# BeagleBone_Blue.net
KiCad netlist of a schematic drawn in EAGLE
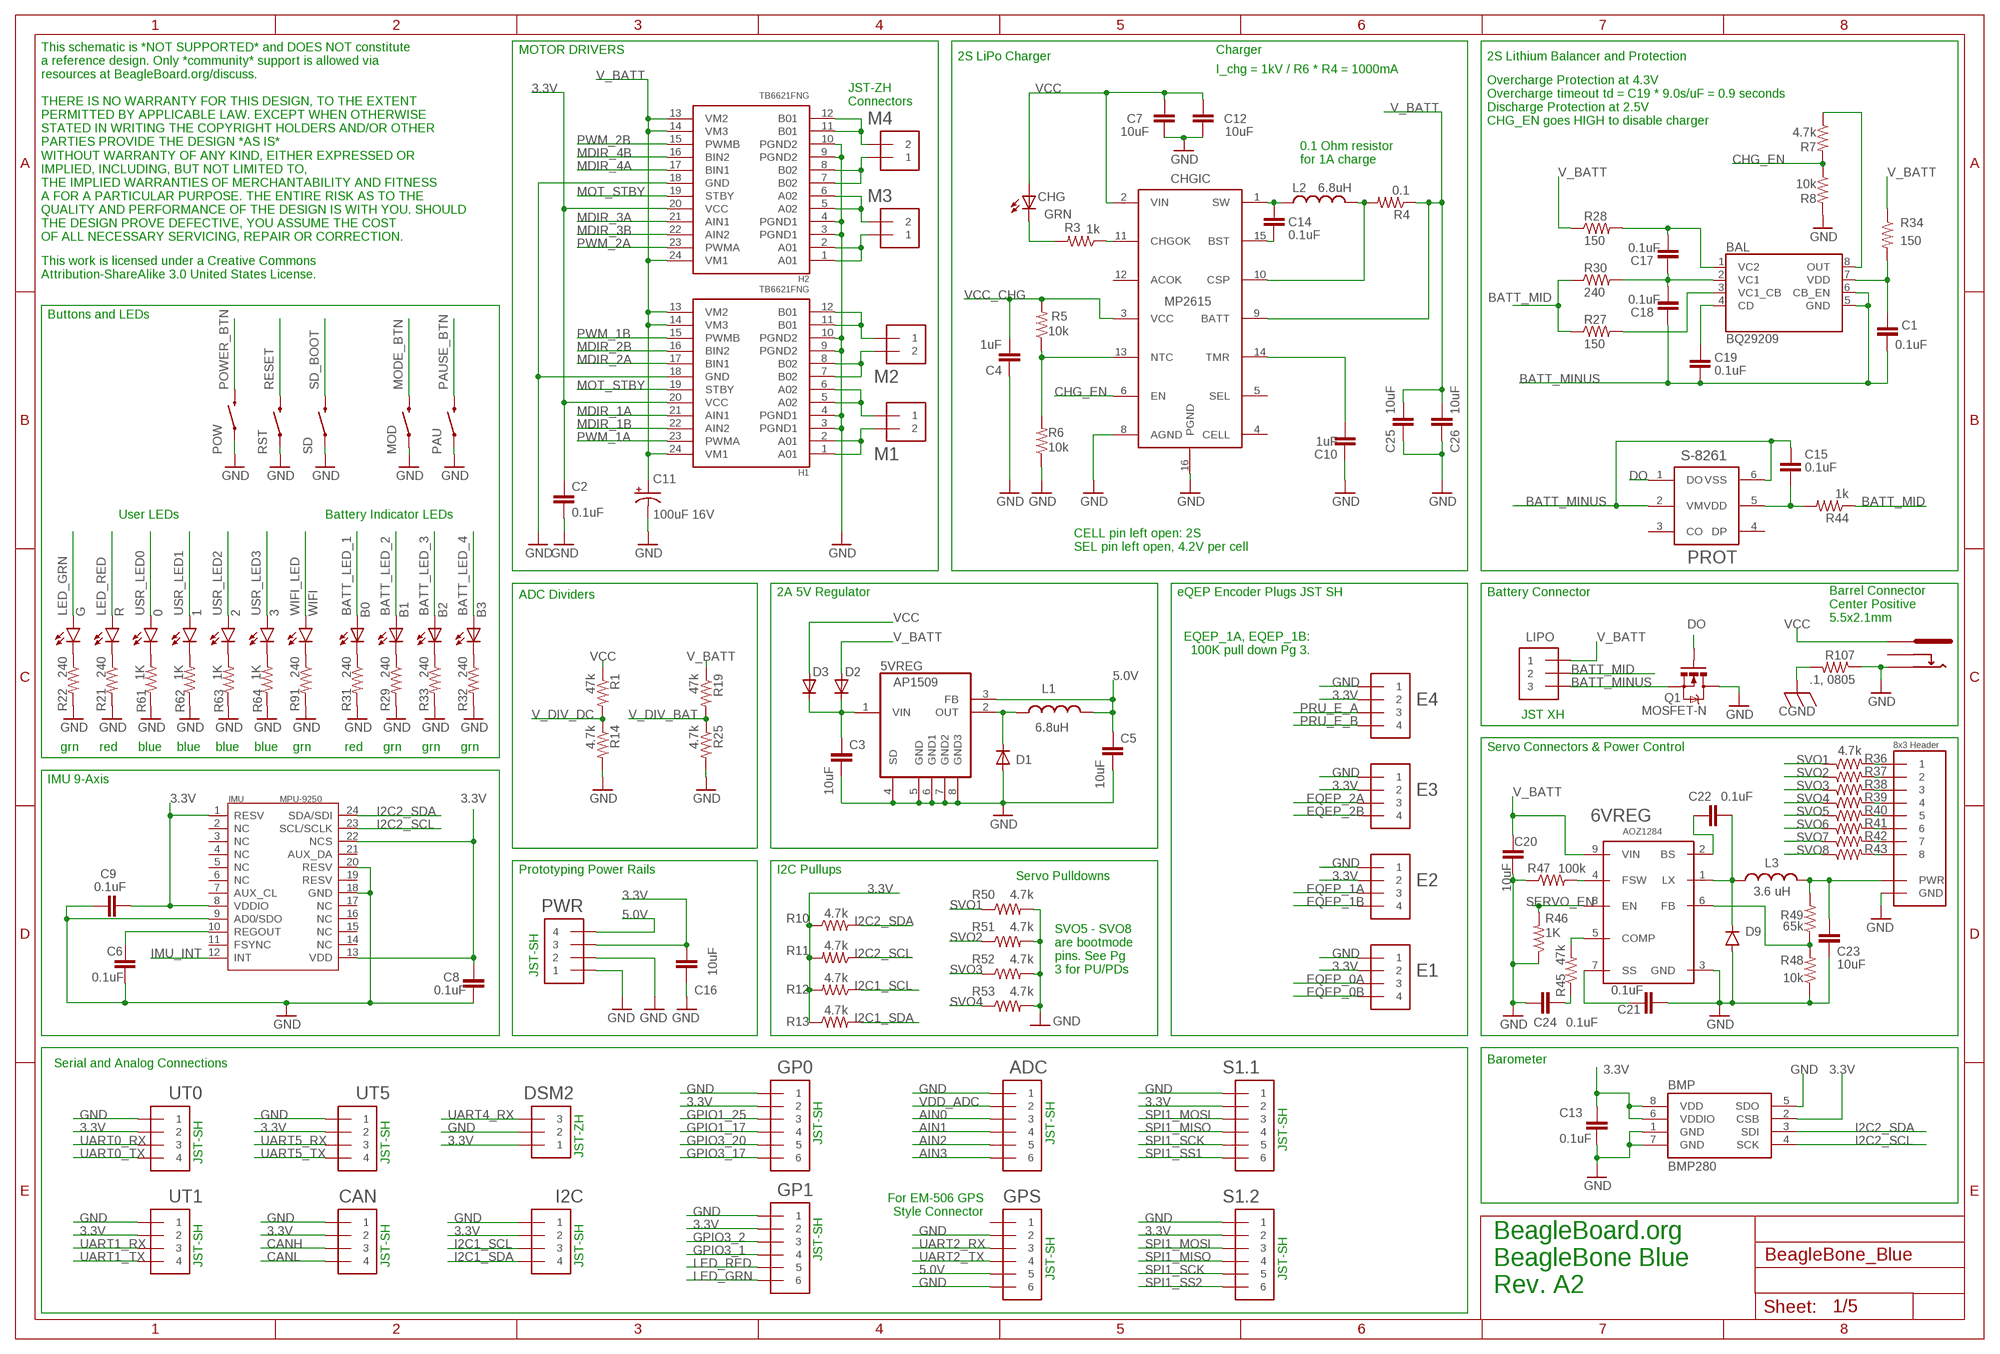
[diagram p0: schematic, sheet 1]
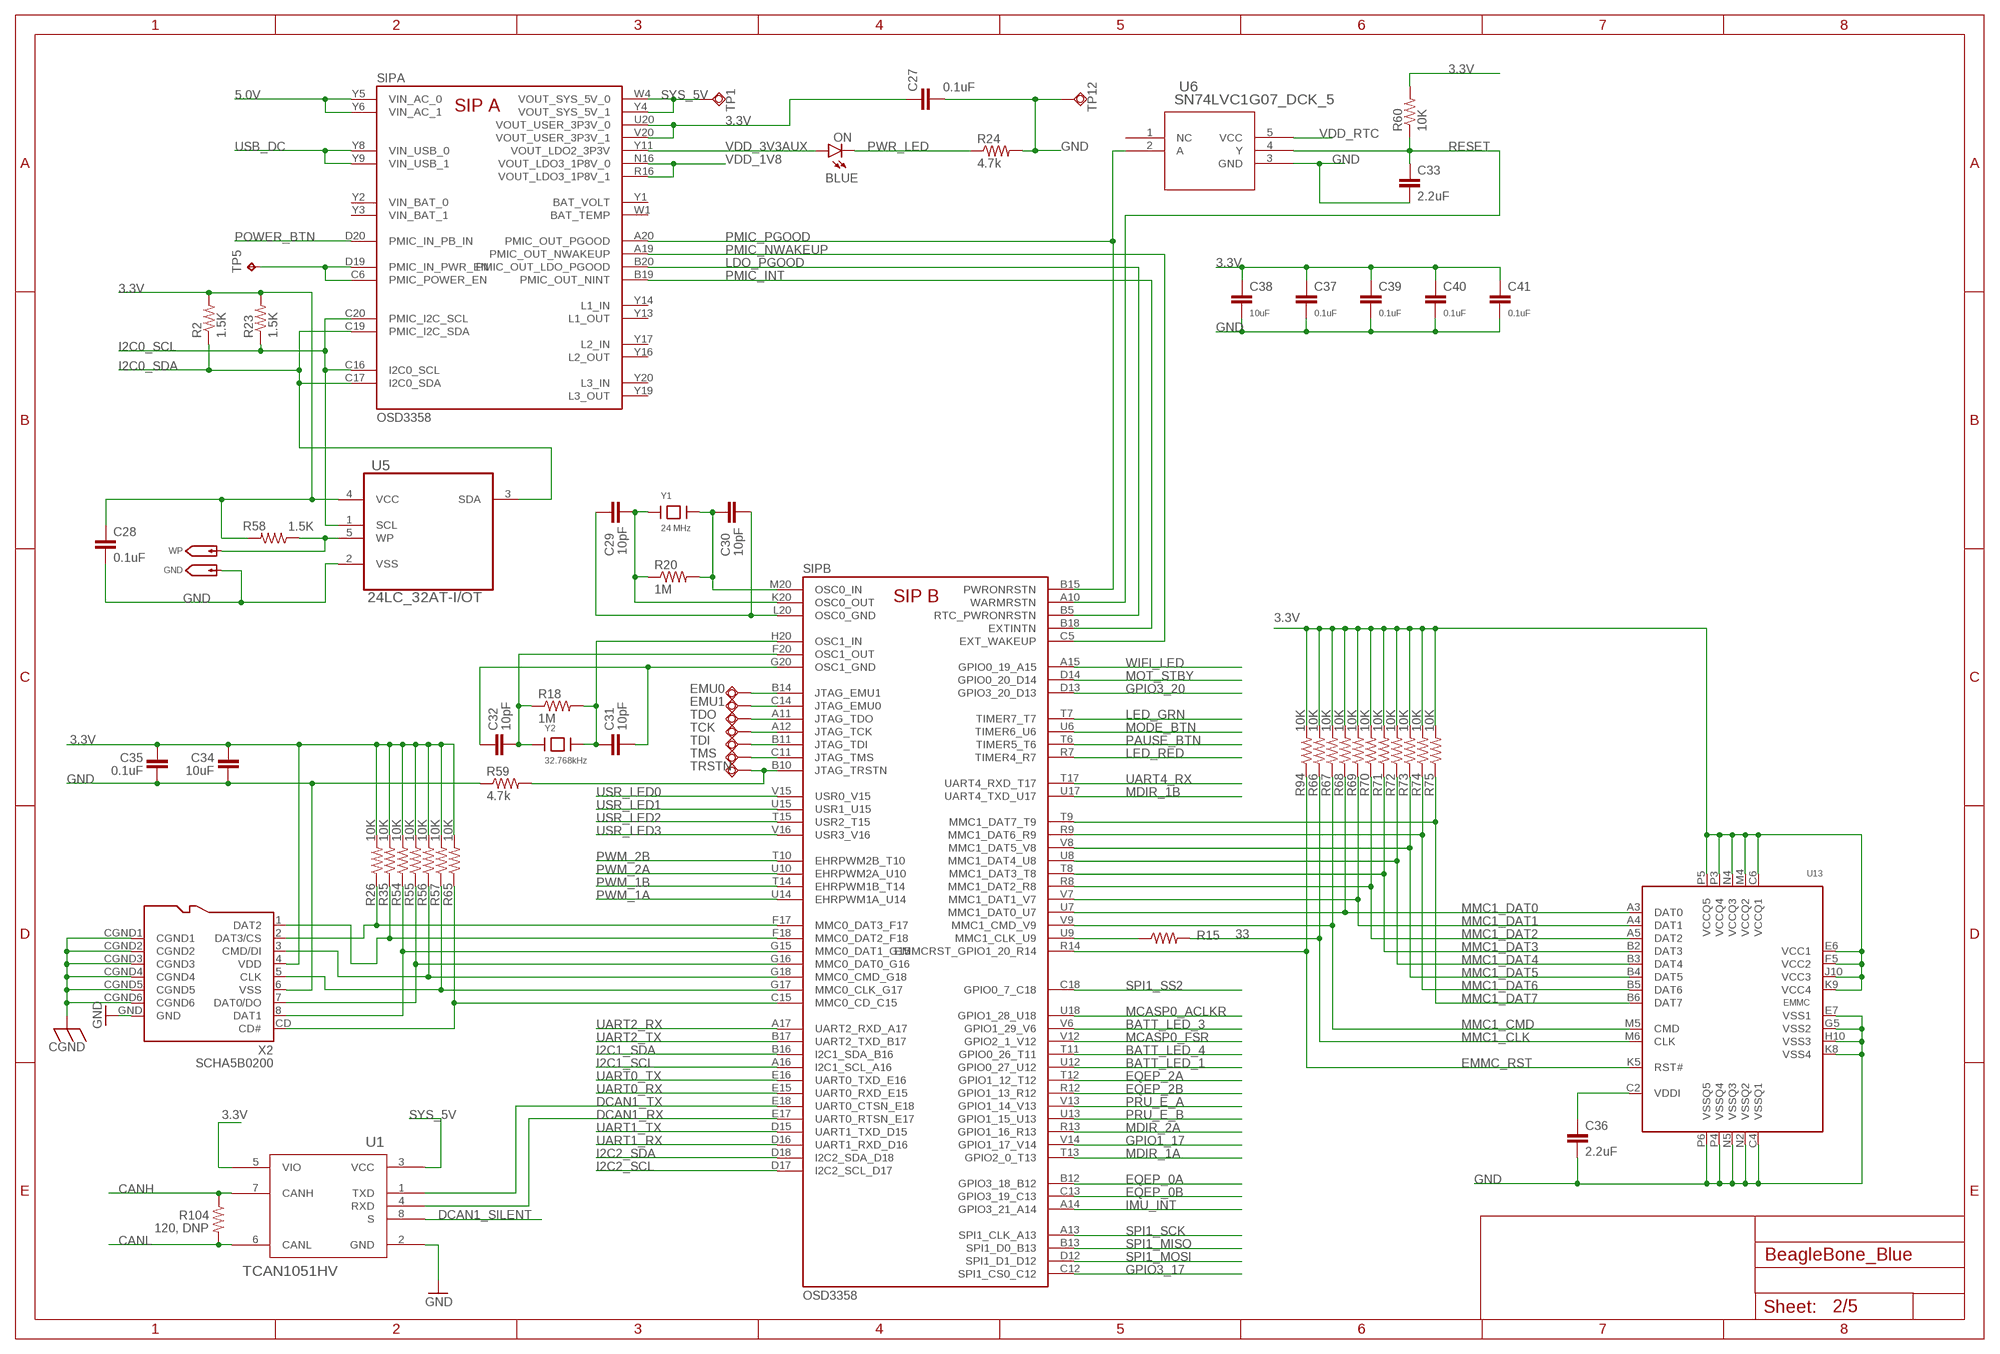
[diagram p1: schematic, sheet 2]
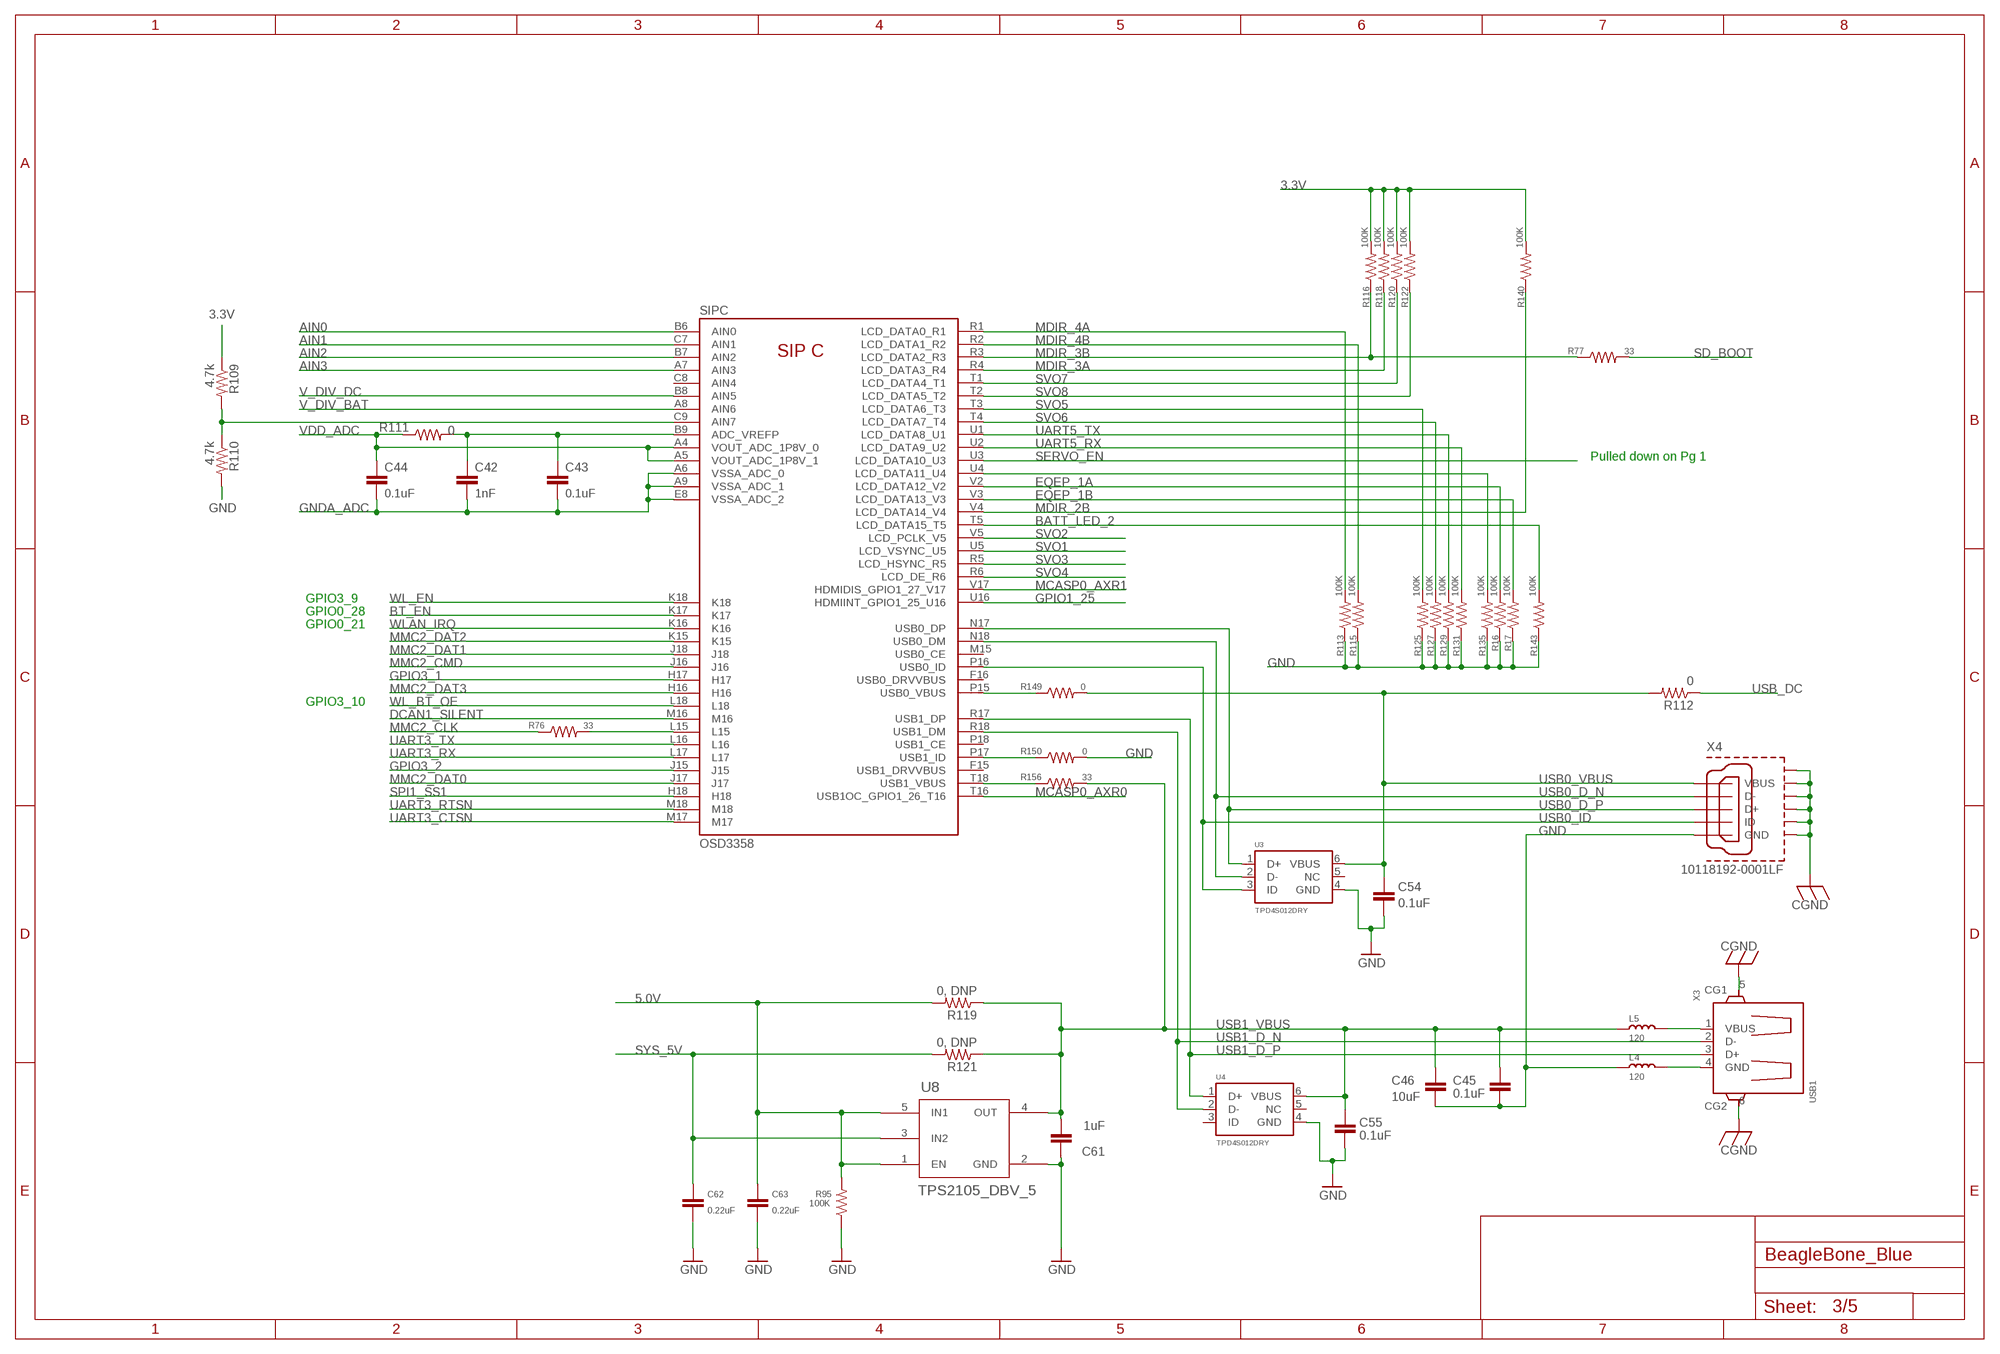
[diagram p2: schematic, sheet 3]
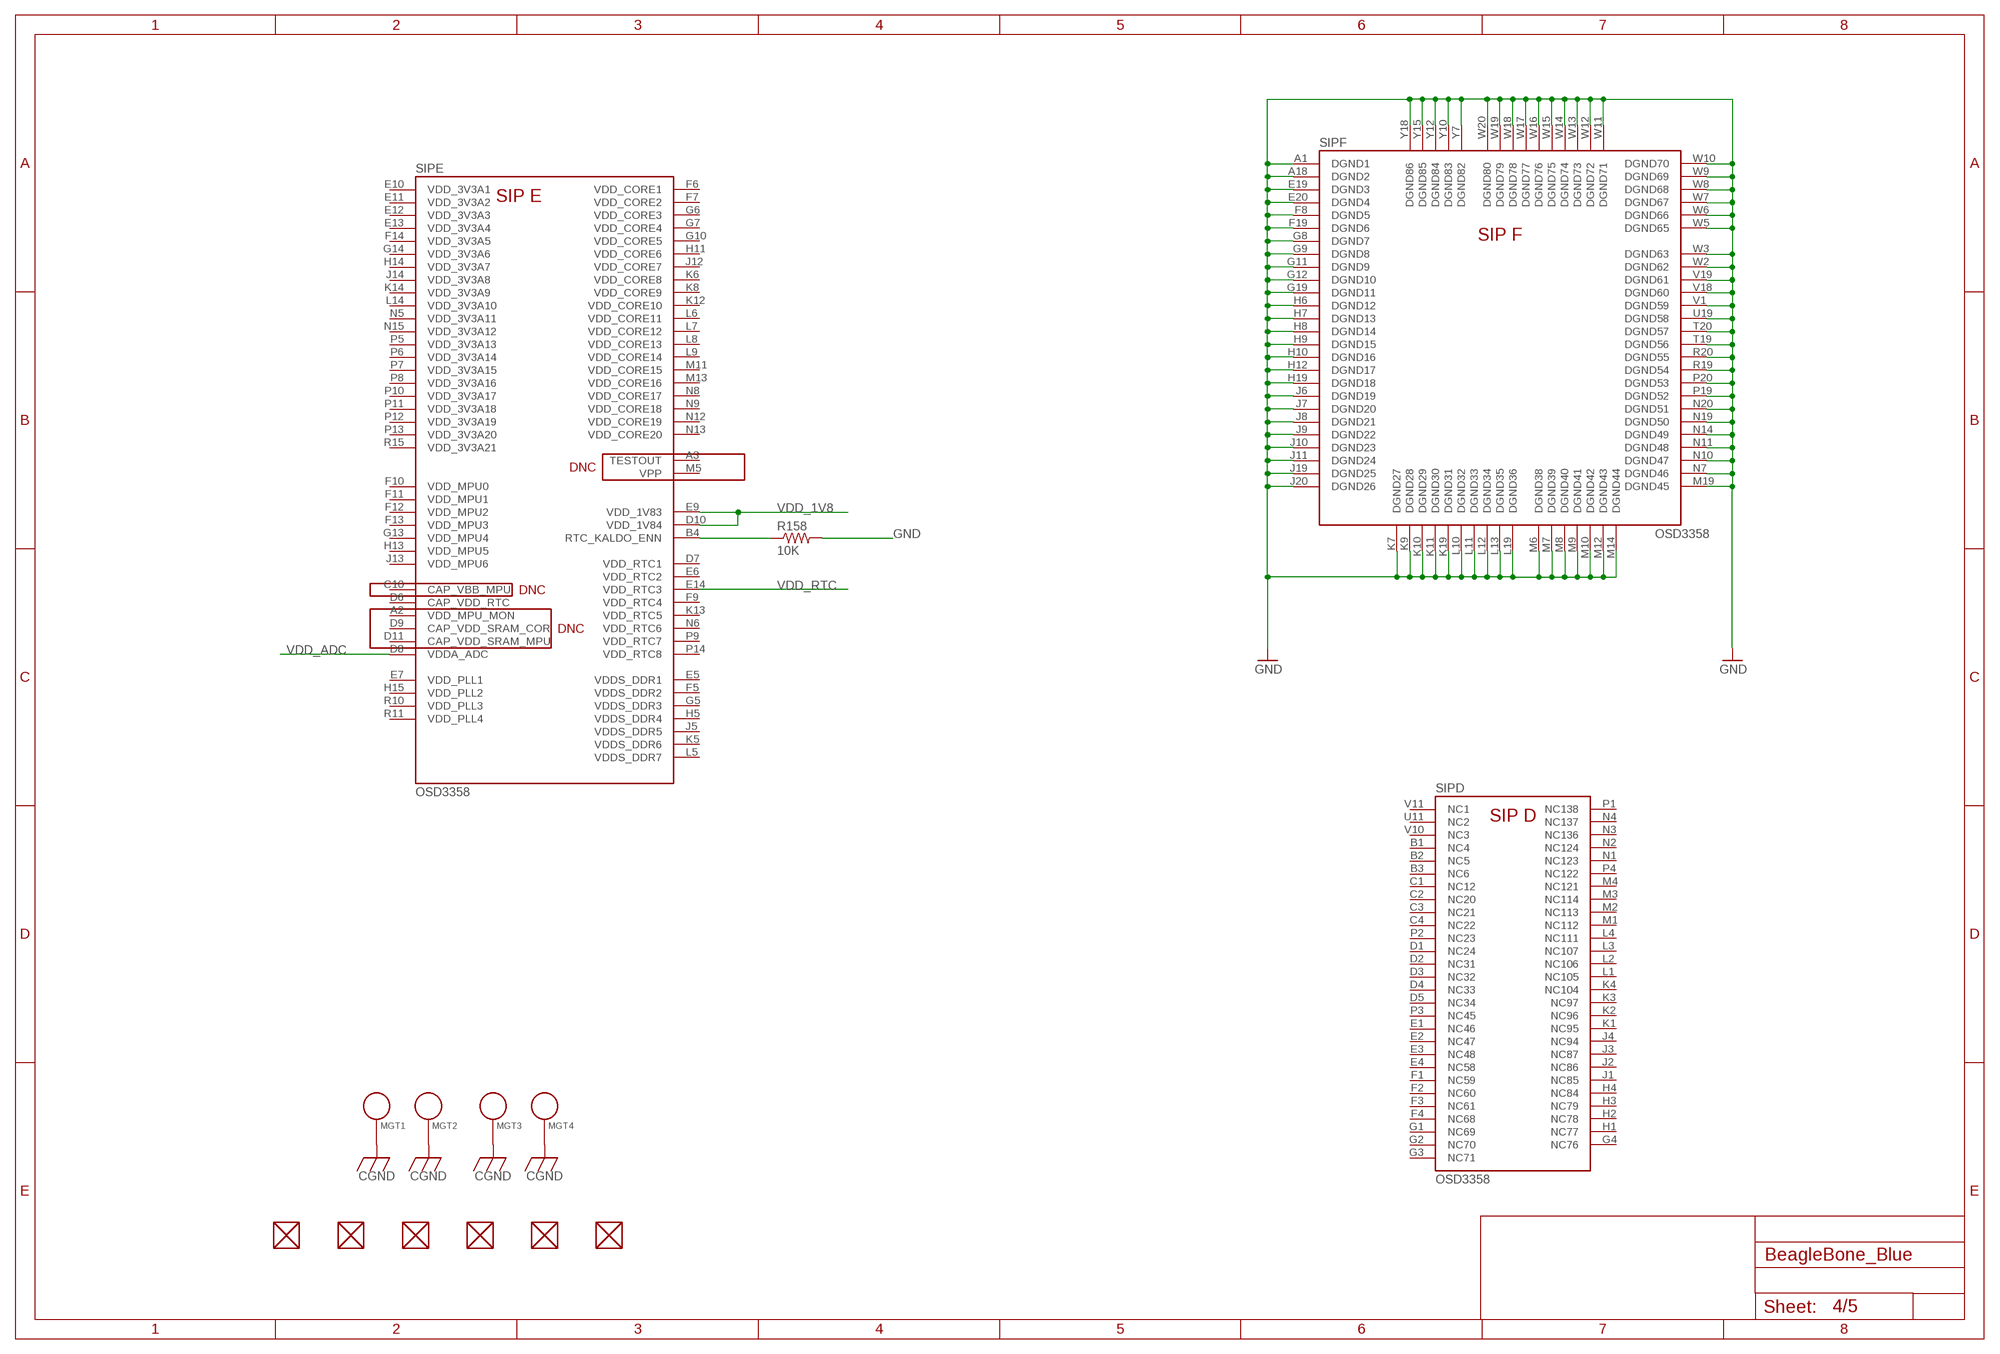
[diagram p3: schematic, sheet 4]
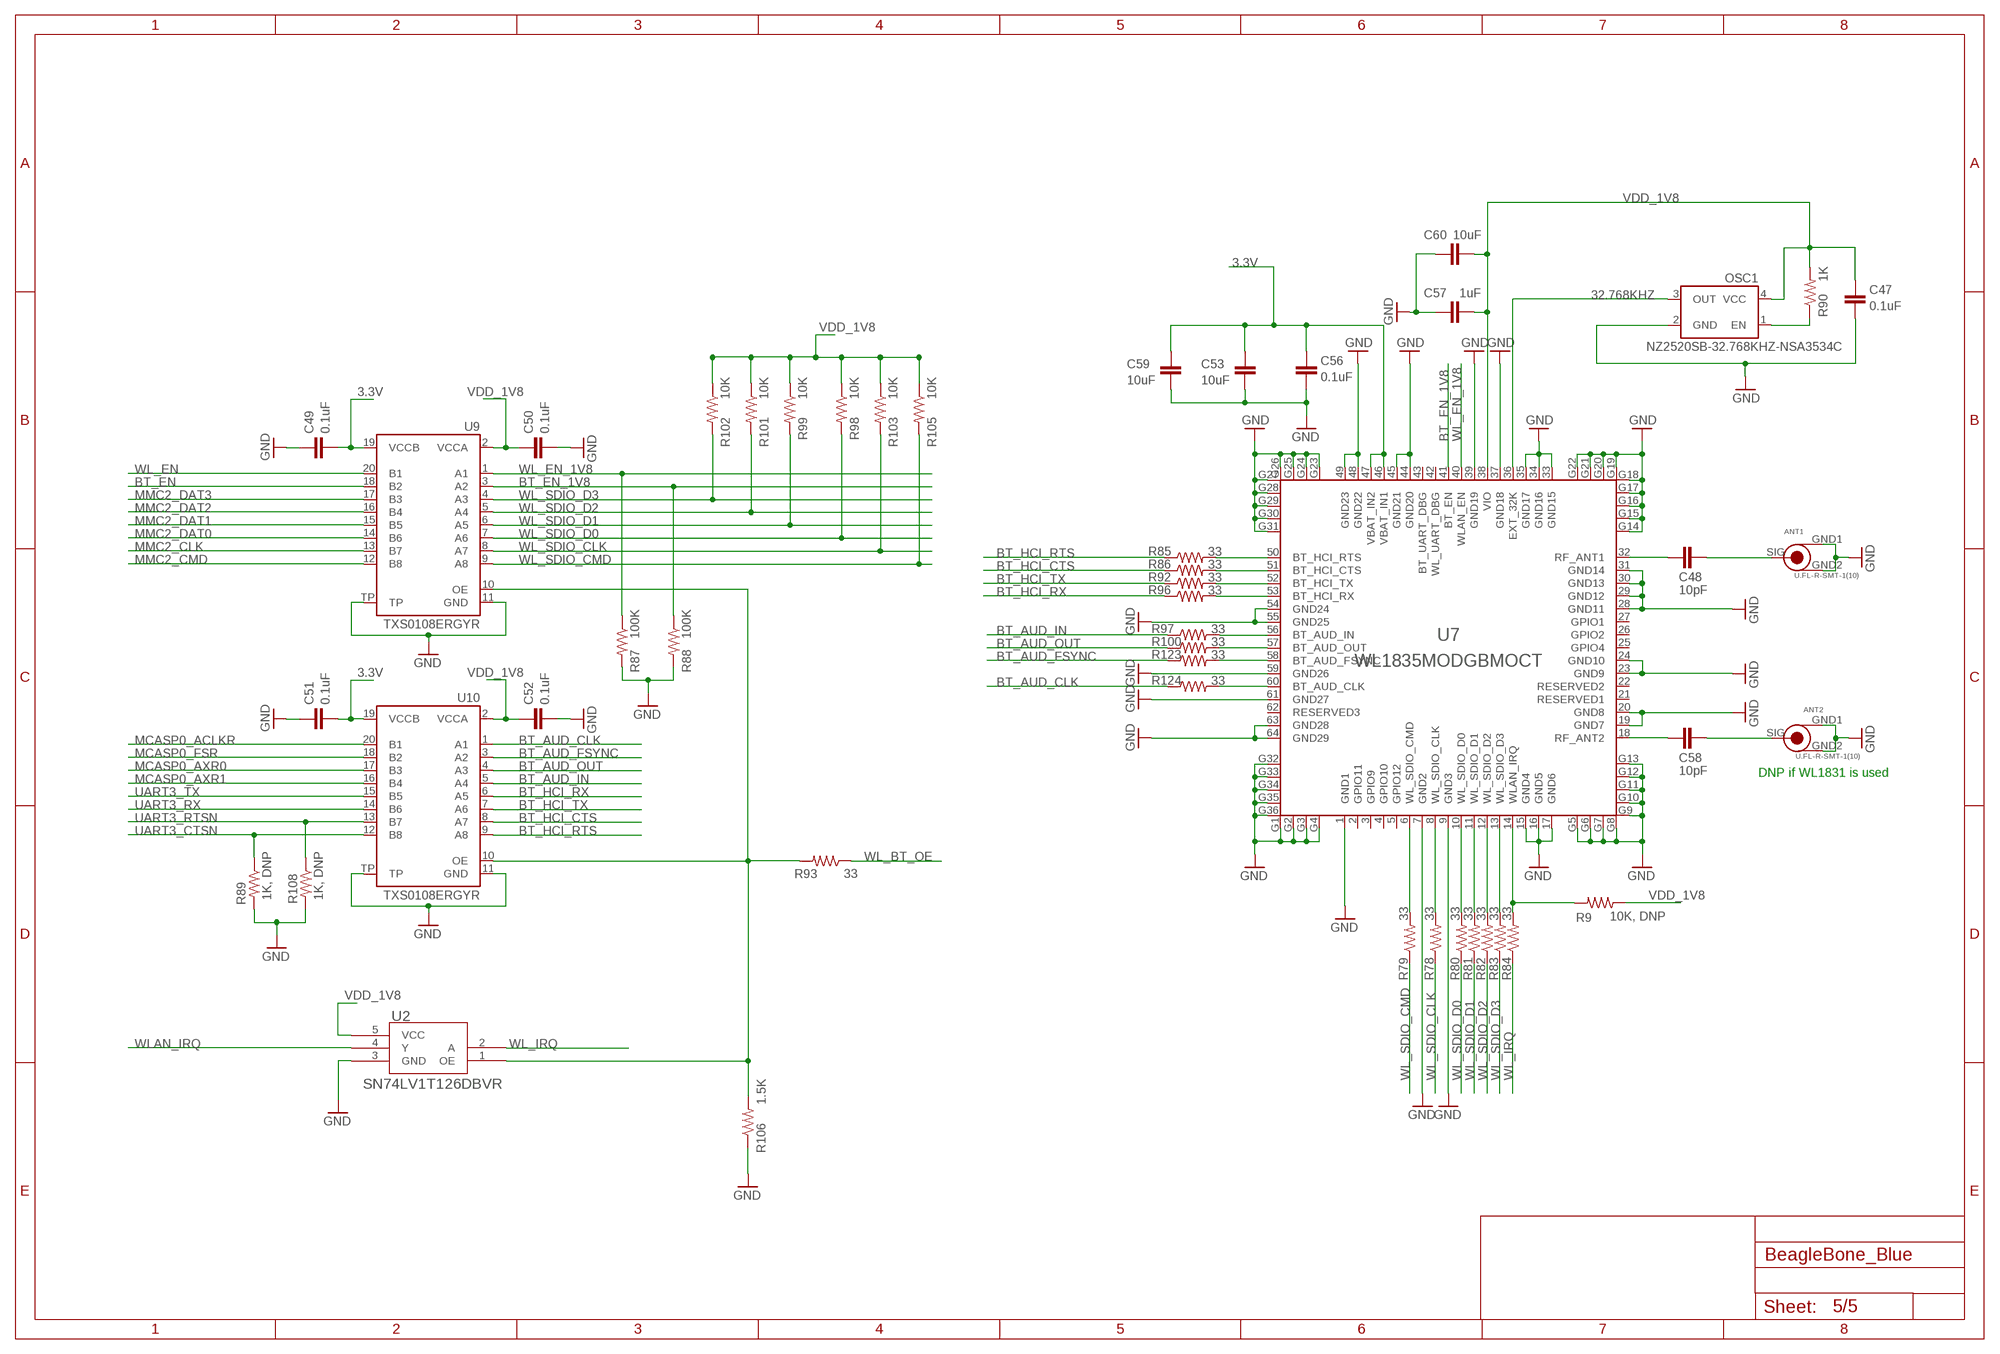
[diagram p4: schematic, sheet 5]

(export (version "E")
  (design (tool "Eeschema 10.0.6"))
  (components
    (comp (ref "0")
      (value "BLUE")
      (footprint "eagle-import:BEAGLEBONE_BLUE_LED-0603")
      (libsource (lib "eagle-import") (part "LED0603"))
    )
    (comp (ref "1")
      (value "BLUE")
      (footprint "eagle-import:BEAGLEBONE_BLUE_LED-0603")
      (libsource (lib "eagle-import") (part "LED0603"))
    )
    (comp (ref "2")
      (value "BLUE")
      (footprint "eagle-import:BEAGLEBONE_BLUE_LED-0603")
      (libsource (lib "eagle-import") (part "LED0603"))
    )
    (comp (ref "3")
      (value "BLUE")
      (footprint "eagle-import:BEAGLEBONE_BLUE_LED-0603")
      (libsource (lib "eagle-import") (part "LED0603"))
    )
    (comp (ref "5VREG")
      (value "AP1509SOIC-8-TIGHT")
      (footprint "eagle-import:BEAGLEBONE_BLUE_SO08-TIGHT")
      (libsource (lib "eagle-import") (part "AP1509SOIC-8-TIGHT"))
    )
    (comp (ref "6VREG")
      (value "AOZ1284")
      (footprint "eagle-import:SO08-EXPOSED")
      (libsource (lib "eagle-import") (part "AOZ1284"))
    )
    (comp (ref "12V")
      (value "PJ-102B_POWER_CON")
      (footprint "eagle-import:PJ-102B_POWER_CON")
      (libsource (lib "eagle-import") (part "PJ-102B_POWER_CON"))
    )
    (comp (ref "ADC")
      (value "JST_SH_6")
      (footprint "eagle-import:JST_SH_6")
      (libsource (lib "eagle-import") (part "JST_SH_6"))
    )
    (comp (ref "B0")
      (value "RED")
      (footprint "eagle-import:LED-0603")
      (libsource (lib "eagle-import") (part "SparkFun-LED_LED0603"))
    )
    (comp (ref "B1")
      (value "GREEN")
      (footprint "eagle-import:LED-0603")
      (libsource (lib "eagle-import") (part "SparkFun-LED_LED0603"))
    )
    (comp (ref "B2")
      (value "GREEN")
      (footprint "eagle-import:LED-0603")
      (libsource (lib "eagle-import") (part "SparkFun-LED_LED0603"))
    )
    (comp (ref "B3")
      (value "GREEN")
      (footprint "eagle-import:LED-0603")
      (libsource (lib "eagle-import") (part "SparkFun-LED_LED0603"))
    )
    (comp (ref "BAL")
      (value "BQ29209")
      (footprint "eagle-import:8-SON_3X3MM")
      (libsource (lib "eagle-import") (part "BQ29209"))
    )
    (comp (ref "BMP")
      (value "BMP280")
      (footprint "eagle-import:BMP280")
      (libsource (lib "eagle-import") (part "BMP280"))
    )
    (comp (ref "C1")
      (value "0.1uF")
      (footprint "eagle-import:0402-CAP")
      (libsource (lib "eagle-import") (part "Strawson_Eagle_Lib_CAP0402-CAP"))
    )
    (comp (ref "C2")
      (value "0.1uF")
      (footprint "eagle-import:0402-CAP")
      (libsource (lib "eagle-import") (part "Strawson_Eagle_Lib_CAP0402-CAP"))
    )
    (comp (ref "C3")
      (value "10uF")
      (footprint "eagle-import:0805")
      (libsource (lib "eagle-import") (part "CAP0805"))
    )
    (comp (ref "C4")
      (value "1uF")
      (footprint "eagle-import:0402-CAP")
      (libsource (lib "eagle-import") (part "Strawson_Eagle_Lib_CAP0402-CAP"))
    )
    (comp (ref "C5")
      (value "10uF")
      (footprint "eagle-import:0805")
      (libsource (lib "eagle-import") (part "CAP0805"))
    )
    (comp (ref "C6")
      (value "0.1uF")
      (footprint "eagle-import:0402-CAP")
      (libsource (lib "eagle-import") (part "Strawson_Eagle_Lib_CAP0402-CAP"))
    )
    (comp (ref "C7")
      (value "10uF")
      (footprint "eagle-import:0805")
      (libsource (lib "eagle-import") (part "CAP0805"))
    )
    (comp (ref "C8")
      (value "0.1uF")
      (footprint "eagle-import:0402-CAP")
      (libsource (lib "eagle-import") (part "Strawson_Eagle_Lib_CAP0402-CAP"))
    )
    (comp (ref "C9")
      (value "0.1uF")
      (footprint "eagle-import:0402-CAP")
      (libsource (lib "eagle-import") (part "Strawson_Eagle_Lib_CAP0402-CAP"))
    )
    (comp (ref "C10")
      (value "1uF")
      (footprint "eagle-import:0402-CAP")
      (libsource (lib "eagle-import") (part "Strawson_Eagle_Lib_CAP0402-CAP"))
    )
    (comp (ref "C11")
      (value "100uF 16V")
      (footprint "eagle-import:PANASONIC_D")
      (libsource (lib "eagle-import") (part "CPOL-USD"))
    )
    (comp (ref "C12")
      (value "10uF")
      (footprint "eagle-import:0805")
      (libsource (lib "eagle-import") (part "CAP0805"))
    )
    (comp (ref "C13")
      (value "0.1uF")
      (footprint "eagle-import:0402-CAP")
      (libsource (lib "eagle-import") (part "Strawson_Eagle_Lib_CAP0402-CAP"))
    )
    (comp (ref "C14")
      (value "0.1uF")
      (footprint "eagle-import:0402-CAP")
      (libsource (lib "eagle-import") (part "Strawson_Eagle_Lib_CAP0402-CAP"))
    )
    (comp (ref "C15")
      (value "0.1uF")
      (footprint "eagle-import:0402-CAP")
      (libsource (lib "eagle-import") (part "Strawson_Eagle_Lib_CAP0402-CAP"))
    )
    (comp (ref "C16")
      (value "10uF")
      (footprint "eagle-import:0805")
      (libsource (lib "eagle-import") (part "CAP0805"))
    )
    (comp (ref "C17")
      (value "0.1uF")
      (footprint "eagle-import:0402-CAP")
      (libsource (lib "eagle-import") (part "Strawson_Eagle_Lib_CAP0402-CAP"))
    )
    (comp (ref "C18")
      (value "0.1uF")
      (footprint "eagle-import:0402-CAP")
      (libsource (lib "eagle-import") (part "Strawson_Eagle_Lib_CAP0402-CAP"))
    )
    (comp (ref "C19")
      (value "0.1uF")
      (footprint "eagle-import:0402-CAP")
      (libsource (lib "eagle-import") (part "Strawson_Eagle_Lib_CAP0402-CAP"))
    )
    (comp (ref "C20")
      (value "10uF")
      (footprint "eagle-import:0805")
      (libsource (lib "eagle-import") (part "CAP0805"))
    )
    (comp (ref "C21")
      (value "0.1uF")
      (footprint "eagle-import:0402-CAP")
      (libsource (lib "eagle-import") (part "Strawson_Eagle_Lib_CAP0402-CAP"))
    )
    (comp (ref "C22")
      (value "0.1uF")
      (footprint "eagle-import:0402-CAP")
      (libsource (lib "eagle-import") (part "Strawson_Eagle_Lib_CAP0402-CAP"))
    )
    (comp (ref "C23")
      (value "10uF")
      (footprint "eagle-import:0805")
      (libsource (lib "eagle-import") (part "CAP0805"))
    )
    (comp (ref "C24")
      (value "0.1uF")
      (footprint "eagle-import:0402-CAP")
      (libsource (lib "eagle-import") (part "Strawson_Eagle_Lib_CAP0402-CAP"))
    )
    (comp (ref "C25")
      (value "10uF")
      (footprint "eagle-import:0805")
      (libsource (lib "eagle-import") (part "CAP0805"))
    )
    (comp (ref "C26")
      (value "10uF")
      (footprint "eagle-import:0805")
      (libsource (lib "eagle-import") (part "CAP0805"))
    )
    (comp (ref "CAN")
      (value "JST_SH_4")
      (footprint "eagle-import:JST_SH_4_SMD")
      (libsource (lib "eagle-import") (part "JST_SH_4"))
    )
    (comp (ref "CHG")
      (value "GRN")
      (footprint "eagle-import:LED-0603")
      (libsource (lib "eagle-import") (part "SparkFun-LED_LED0603"))
    )
    (comp (ref "CHGIC")
      (value "MP2615")
      (footprint "eagle-import:MP2615")
      (libsource (lib "eagle-import") (part "MP2615"))
    )
    (comp (ref "D1")
      (value "DIODE_SOD-123FL")
      (footprint "eagle-import:ADAFRUIT_SOD-123FL")
      (libsource (lib "eagle-import") (part "DIODE_SOD-123FL"))
    )
    (comp (ref "D2")
      (value "DIODE_SOD-123FL")
      (footprint "eagle-import:ADAFRUIT_SOD-123FL")
      (libsource (lib "eagle-import") (part "DIODE_SOD-123FL"))
    )
    (comp (ref "D3")
      (value "DIODE_SOD-123FL")
      (footprint "eagle-import:ADAFRUIT_SOD-123FL")
      (libsource (lib "eagle-import") (part "DIODE_SOD-123FL"))
    )
    (comp (ref "D9")
      (value "DIODEDO214AA")
      (footprint "eagle-import:DO-214AA")
      (libsource (lib "eagle-import") (part "DIODEDO214AA"))
    )
    (comp (ref "DSM2")
      (value "JST_ZH_3")
      (footprint "eagle-import:JST_ZH_3")
      (libsource (lib "eagle-import") (part "JST_ZH_3"))
    )
    (comp (ref "E1")
      (value "JST_SH_4")
      (footprint "eagle-import:JST_SH_4_SMD")
      (libsource (lib "eagle-import") (part "JST_SH_4"))
    )
    (comp (ref "E2")
      (value "JST_SH_4")
      (footprint "eagle-import:JST_SH_4_SMD")
      (libsource (lib "eagle-import") (part "JST_SH_4"))
    )
    (comp (ref "E3")
      (value "JST_SH_4")
      (footprint "eagle-import:JST_SH_4_SMD")
      (libsource (lib "eagle-import") (part "JST_SH_4"))
    )
    (comp (ref "E4")
      (value "JST_SH_4")
      (footprint "eagle-import:JST_SH_4_SMD")
      (libsource (lib "eagle-import") (part "JST_SH_4"))
    )
    (comp (ref "G")
      (value "GREEN")
      (footprint "eagle-import:BEAGLEBONE_BLUE_LED-0603")
      (libsource (lib "eagle-import") (part "LED0603"))
    )
    (comp (ref "GP0")
      (value "JST_SH_6")
      (footprint "eagle-import:JST_SH_6")
      (libsource (lib "eagle-import") (part "JST_SH_6"))
    )
    (comp (ref "GP1")
      (value "JST_SH_6")
      (footprint "eagle-import:JST_SH_6")
      (libsource (lib "eagle-import") (part "JST_SH_6"))
    )
    (comp (ref "GPS")
      (value "JST_SH_6")
      (footprint "eagle-import:JST_SH_6")
      (libsource (lib "eagle-import") (part "JST_SH_6"))
    )
    (comp (ref "H1")
      (value "TB6621FNG")
      (footprint "eagle-import:SSOP24")
      (libsource (lib "eagle-import") (part "TB6621FNG"))
    )
    (comp (ref "H2")
      (value "TB6621FNG")
      (footprint "eagle-import:SSOP24")
      (libsource (lib "eagle-import") (part "TB6621FNG"))
    )
    (comp (ref "I2C")
      (value "JST_SH_4")
      (footprint "eagle-import:JST_SH_4_SMD")
      (libsource (lib "eagle-import") (part "JST_SH_4"))
    )
    (comp (ref "IMU")
      (value "MPU-9250")
      (footprint "eagle-import:QFN24G-0.4-3X3MM")
      (libsource (lib "eagle-import") (part "MPU-9250"))
    )
    (comp (ref "J2")
      (value "STRAWSON_EAGLE_LIB_SERVO_HEADERS_8X")
      (footprint "eagle-import:STRAWSON_EAGLE_LIB_3X8_0.1__HEADER")
      (libsource (lib "eagle-import") (part "STRAWSON_EAGLE_LIB_SERVO_HEADERS_8X"))
    )
    (comp (ref "L1")
      (value "6.8uH")
      (footprint "eagle-import:SRN6045")
      (libsource (lib "eagle-import") (part "INDUCTORBOURNS_SRN6045"))
    )
    (comp (ref "L2")
      (value "6.8uH")
      (footprint "eagle-import:SRN6045")
      (libsource (lib "eagle-import") (part "INDUCTORBOURNS_SRN6045"))
    )
    (comp (ref "L3")
      (value "3.6 uH")
      (footprint "eagle-import:8X8MM_INDUCTOR")
      (libsource (lib "eagle-import") (part "INDUCTOR"))
    )
    (comp (ref "LIPO")
      (value "BATTERY")
      (footprint "eagle-import:JST_XH_3-PIN")
      (libsource (lib "eagle-import") (part "JST_XH_3-PIN"))
    )
    (comp (ref "M1")
      (value "JST_ZH_2")
      (footprint "eagle-import:JST_ZH_2")
      (libsource (lib "eagle-import") (part "JST_ZH_2"))
    )
    (comp (ref "M2")
      (value "JST_ZH_2")
      (footprint "eagle-import:JST_ZH_2")
      (libsource (lib "eagle-import") (part "JST_ZH_2"))
    )
    (comp (ref "M3")
      (value "JST_ZH_2")
      (footprint "eagle-import:JST_ZH_2")
      (libsource (lib "eagle-import") (part "JST_ZH_2"))
    )
    (comp (ref "M4")
      (value "JST_ZH_2")
      (footprint "eagle-import:JST_ZH_2")
      (libsource (lib "eagle-import") (part "JST_ZH_2"))
    )
    (comp (ref "MOD")
      (value "SWITCH-MOMENTARY-2SMD-1101NE")
      (footprint "eagle-import:TACTILE-SWITCH-1101NE")
      (libsource (lib "eagle-import") (part "SWITCH-MOMENTARY-2SMD-1101NE"))
    )
    (comp (ref "PAU")
      (value "SWITCH-MOMENTARY-2SMD-1101NE")
      (footprint "eagle-import:TACTILE-SWITCH-1101NE")
      (libsource (lib "eagle-import") (part "SWITCH-MOMENTARY-2SMD-1101NE"))
    )
    (comp (ref "POW")
      (value "SWITCH-MOMENTARY-2SMD-1101NE")
      (footprint "eagle-import:TACTILE-SWITCH-1101NE")
      (libsource (lib "eagle-import") (part "SWITCH-MOMENTARY-2SMD-1101NE"))
    )
    (comp (ref "PROT")
      (value "S-8261")
      (footprint "eagle-import:SOT-236")
      (libsource (lib "eagle-import") (part "S-8261"))
    )
    (comp (ref "PWR")
      (value "JST_SH_4")
      (footprint "eagle-import:JST_SH_4_SMD")
      (libsource (lib "eagle-import") (part "JST_SH_4"))
    )
    (comp (ref "Q1")
      (value "MOSFET-N")
      (footprint "eagle-import:SO08-TIGHT")
      (libsource (lib "eagle-import") (part "MOSFET-NCHANNEL"))
    )
    (comp (ref "R")
      (value "RED")
      (footprint "eagle-import:BEAGLEBONE_BLUE_LED-0603")
      (libsource (lib "eagle-import") (part "LED0603"))
    )
    (comp (ref "R1")
      (value "47k")
      (footprint "eagle-import:0402-RES")
      (libsource (lib "eagle-import") (part "RESISTOR0402-RES"))
    )
    (comp (ref "R3")
      (value "1k")
      (footprint "eagle-import:0402-RES")
      (libsource (lib "eagle-import") (part "RESISTOR0402-RES"))
    )
    (comp (ref "R4")
      (value "0.1")
      (footprint "eagle-import:0603-RES")
      (libsource (lib "eagle-import") (part "RESISTOR0603"))
    )
    (comp (ref "R5")
      (value "10k")
      (footprint "eagle-import:0402-RES")
      (libsource (lib "eagle-import") (part "RESISTOR0402-RES"))
    )
    (comp (ref "R6")
      (value "10k")
      (footprint "eagle-import:0402-RES")
      (libsource (lib "eagle-import") (part "RESISTOR0402-RES"))
    )
    (comp (ref "R7")
      (value "4.7k")
      (footprint "eagle-import:0402-RES")
      (libsource (lib "eagle-import") (part "RESISTOR0402-RES"))
    )
    (comp (ref "R8")
      (value "10k")
      (footprint "eagle-import:0402-RES")
      (libsource (lib "eagle-import") (part "RESISTOR0402-RES"))
    )
    (comp (ref "R10")
      (value "4.7k")
      (footprint "eagle-import:0402-RES")
      (libsource (lib "eagle-import") (part "RESISTOR0402-RES"))
    )
    (comp (ref "R11")
      (value "4.7k")
      (footprint "eagle-import:0402-RES")
      (libsource (lib "eagle-import") (part "RESISTOR0402-RES"))
    )
    (comp (ref "R12")
      (value "4.7k")
      (footprint "eagle-import:0402-RES")
      (libsource (lib "eagle-import") (part "RESISTOR0402-RES"))
    )
    (comp (ref "R13")
      (value "4.7k")
      (footprint "eagle-import:0402-RES")
      (libsource (lib "eagle-import") (part "RESISTOR0402-RES"))
    )
    (comp (ref "R14")
      (value "4.7k")
      (footprint "eagle-import:0402-RES")
      (libsource (lib "eagle-import") (part "RESISTOR0402-RES"))
    )
    (comp (ref "R19")
      (value "47k")
      (footprint "eagle-import:0402-RES")
      (libsource (lib "eagle-import") (part "RESISTOR0402-RES"))
    )
    (comp (ref "R21")
      (value "240")
      (footprint "eagle-import:0402-RES")
      (libsource (lib "eagle-import") (part "RESISTOR0402-RES"))
    )
    (comp (ref "R22")
      (value "240")
      (footprint "eagle-import:0402-RES")
      (libsource (lib "eagle-import") (part "RESISTOR0402-RES"))
    )
    (comp (ref "R25")
      (value "4.7k")
      (footprint "eagle-import:0402-RES")
      (libsource (lib "eagle-import") (part "RESISTOR0402-RES"))
    )
    (comp (ref "R27")
      (value "150")
      (footprint "eagle-import:0402-RES")
      (libsource (lib "eagle-import") (part "RESISTOR0402-RES"))
    )
    (comp (ref "R28")
      (value "150")
      (footprint "eagle-import:0402-RES")
      (libsource (lib "eagle-import") (part "RESISTOR0402-RES"))
    )
    (comp (ref "R29")
      (value "240")
      (footprint "eagle-import:0402-RES")
      (libsource (lib "eagle-import") (part "RESISTOR0402-RES"))
    )
    (comp (ref "R30")
      (value "240")
      (footprint "eagle-import:0402-RES")
      (libsource (lib "eagle-import") (part "RESISTOR0402-RES"))
    )
    (comp (ref "R31")
      (value "240")
      (footprint "eagle-import:0402-RES")
      (libsource (lib "eagle-import") (part "RESISTOR0402-RES"))
    )
    (comp (ref "R32")
      (value "240")
      (footprint "eagle-import:0402-RES")
      (libsource (lib "eagle-import") (part "RESISTOR0402-RES"))
    )
    (comp (ref "R33")
      (value "240")
      (footprint "eagle-import:0402-RES")
      (libsource (lib "eagle-import") (part "RESISTOR0402-RES"))
    )
    (comp (ref "R34")
      (value "150")
      (footprint "eagle-import:0402-RES")
      (libsource (lib "eagle-import") (part "RESISTOR0402-RES"))
    )
    (comp (ref "R36")
      (value "4.7k")
      (footprint "eagle-import:0402-RES")
      (libsource (lib "eagle-import") (part "RESISTOR0402-RES"))
    )
    (comp (ref "R37")
      (value "4.7k")
      (footprint "eagle-import:0402-RES")
      (libsource (lib "eagle-import") (part "RESISTOR0402-RES"))
    )
    (comp (ref "R38")
      (value "4.7k")
      (footprint "eagle-import:0402-RES")
      (libsource (lib "eagle-import") (part "RESISTOR0402-RES"))
    )
    (comp (ref "R39")
      (value "4.7k")
      (footprint "eagle-import:0402-RES")
      (libsource (lib "eagle-import") (part "RESISTOR0402-RES"))
    )
    (comp (ref "R40")
      (value "4.7k")
      (footprint "eagle-import:0402-RES")
      (libsource (lib "eagle-import") (part "RESISTOR0402-RES"))
    )
    (comp (ref "R41")
      (value "4.7k")
      (footprint "eagle-import:0402-RES")
      (libsource (lib "eagle-import") (part "RESISTOR0402-RES"))
    )
    (comp (ref "R42")
      (value "4.7k")
      (footprint "eagle-import:0402-RES")
      (libsource (lib "eagle-import") (part "RESISTOR0402-RES"))
    )
    (comp (ref "R43")
      (value "4.7k")
      (footprint "eagle-import:0402-RES")
      (libsource (lib "eagle-import") (part "RESISTOR0402-RES"))
    )
    (comp (ref "R44")
      (value "1k")
      (footprint "eagle-import:0402-RES")
      (libsource (lib "eagle-import") (part "RESISTOR0402-RES"))
    )
    (comp (ref "R45")
      (value "47k")
      (footprint "eagle-import:0402-RES")
      (libsource (lib "eagle-import") (part "RESISTOR0402-RES"))
    )
    (comp (ref "R46")
      (value "1K")
      (footprint "eagle-import:0402-RES")
      (libsource (lib "eagle-import") (part "RESISTOR0402-RES"))
    )
    (comp (ref "R47")
      (value "100k")
      (footprint "eagle-import:0402-RES")
      (libsource (lib "eagle-import") (part "RESISTOR0402-RES"))
    )
    (comp (ref "R48")
      (value "10k")
      (footprint "eagle-import:0402-RES")
      (libsource (lib "eagle-import") (part "RESISTOR0402-RES"))
    )
    (comp (ref "R49")
      (value "65k")
      (footprint "eagle-import:0402-RES")
      (libsource (lib "eagle-import") (part "RESISTOR0402-RES"))
    )
    (comp (ref "R50")
      (value "4.7k")
      (footprint "eagle-import:0402-RES")
      (libsource (lib "eagle-import") (part "RESISTOR0402-RES"))
    )
    (comp (ref "R51")
      (value "4.7k")
      (footprint "eagle-import:0402-RES")
      (libsource (lib "eagle-import") (part "RESISTOR0402-RES"))
    )
    (comp (ref "R52")
      (value "4.7k")
      (footprint "eagle-import:0402-RES")
      (libsource (lib "eagle-import") (part "RESISTOR0402-RES"))
    )
    (comp (ref "R53")
      (value "4.7k")
      (footprint "eagle-import:0402-RES")
      (libsource (lib "eagle-import") (part "RESISTOR0402-RES"))
    )
    (comp (ref "R61")
      (value "1K")
      (footprint "eagle-import:0402-RES")
      (libsource (lib "eagle-import") (part "RESISTOR0402-RES"))
    )
    (comp (ref "R62")
      (value "1K")
      (footprint "eagle-import:0402-RES")
      (libsource (lib "eagle-import") (part "RESISTOR0402-RES"))
    )
    (comp (ref "R63")
      (value "1K")
      (footprint "eagle-import:0402-RES")
      (libsource (lib "eagle-import") (part "RESISTOR0402-RES"))
    )
    (comp (ref "R64")
      (value "1K")
      (footprint "eagle-import:0402-RES")
      (libsource (lib "eagle-import") (part "RESISTOR0402-RES"))
    )
    (comp (ref "R91")
      (value "240")
      (footprint "eagle-import:0402-RES")
      (libsource (lib "eagle-import") (part "RESISTOR0402-RES"))
    )
    (comp (ref "R107")
      (value ".1, 0805")
      (footprint "eagle-import:R0805")
      (libsource (lib "eagle-import") (part "R-US_R0805"))
    )
    (comp (ref "RST")
      (value "SWITCH-MOMENTARY-2SMD-1101NE")
      (footprint "eagle-import:TACTILE-SWITCH-1101NE")
      (libsource (lib "eagle-import") (part "SWITCH-MOMENTARY-2SMD-1101NE"))
    )
    (comp (ref "S1.1")
      (value "JST_SH_6")
      (footprint "eagle-import:JST_SH_6")
      (libsource (lib "eagle-import") (part "JST_SH_6"))
    )
    (comp (ref "S1.2")
      (value "JST_SH_6")
      (footprint "eagle-import:JST_SH_6")
      (libsource (lib "eagle-import") (part "JST_SH_6"))
    )
    (comp (ref "SD")
      (value "SWITCH-MOMENTARY-2SMD-1101NE")
      (footprint "eagle-import:TACTILE-SWITCH-1101NE")
      (libsource (lib "eagle-import") (part "SWITCH-MOMENTARY-2SMD-1101NE"))
    )
    (comp (ref "UT0")
      (value "JST_SH_4")
      (footprint "eagle-import:JST_SH_4_SMD")
      (libsource (lib "eagle-import") (part "JST_SH_4"))
    )
    (comp (ref "UT1")
      (value "JST_SH_4")
      (footprint "eagle-import:JST_SH_4_SMD")
      (libsource (lib "eagle-import") (part "JST_SH_4"))
    )
    (comp (ref "UT5")
      (value "JST_SH_4")
      (footprint "eagle-import:JST_SH_4_SMD")
      (libsource (lib "eagle-import") (part "JST_SH_4"))
    )
    (comp (ref "WIFI")
      (value "GREEN")
      (footprint "eagle-import:BEAGLEBONE_BLUE_LED-0603")
      (libsource (lib "eagle-import") (part "LED0603"))
    )
    (comp (ref "C27")
      (value "0.1uF")
      (footprint "eagle-import:0402-CAP")
      (libsource (lib "eagle-import") (part "Strawson_Eagle_Lib_CAP0402-CAP"))
    )
    (comp (ref "C28")
      (value "0.1uF")
      (footprint "eagle-import:0402-CAP")
      (libsource (lib "eagle-import") (part "Strawson_Eagle_Lib_CAP0402-CAP"))
    )
    (comp (ref "C29")
      (value "10pF")
      (footprint "eagle-import:0402-CAP")
      (libsource (lib "eagle-import") (part "Strawson_Eagle_Lib_CAP0402-CAP"))
    )
    (comp (ref "C30")
      (value "10pF")
      (footprint "eagle-import:0402-CAP")
      (libsource (lib "eagle-import") (part "Strawson_Eagle_Lib_CAP0402-CAP"))
    )
    (comp (ref "C31")
      (value "10pF")
      (footprint "eagle-import:0402-CAP")
      (libsource (lib "eagle-import") (part "Strawson_Eagle_Lib_CAP0402-CAP"))
    )
    (comp (ref "C32")
      (value "10pF")
      (footprint "eagle-import:0402-CAP")
      (libsource (lib "eagle-import") (part "Strawson_Eagle_Lib_CAP0402-CAP"))
    )
    (comp (ref "C33")
      (value "2.2uF")
      (footprint "eagle-import:0402-CAP")
      (libsource (lib "eagle-import") (part "Strawson_Eagle_Lib_CAP0402-CAP"))
    )
    (comp (ref "C34")
      (value "10uF")
      (footprint "eagle-import:0805")
      (libsource (lib "eagle-import") (part "Strawson_Eagle_Lib_CAP0805"))
    )
    (comp (ref "C35")
      (value "0.1uF")
      (footprint "eagle-import:0402-CAP")
      (libsource (lib "eagle-import") (part "Strawson_Eagle_Lib_CAP0402-CAP"))
    )
    (comp (ref "C36")
      (value "2.2uF")
      (footprint "eagle-import:0402-CAP")
      (libsource (lib "eagle-import") (part "Strawson_Eagle_Lib_CAP0402-CAP"))
    )
    (comp (ref "C37")
      (value "0.1uF")
      (footprint "eagle-import:0402-CAP")
      (libsource (lib "eagle-import") (part "Strawson_Eagle_Lib_CAP0402-CAP"))
    )
    (comp (ref "C38")
      (value "10uF")
      (footprint "eagle-import:0805")
      (libsource (lib "eagle-import") (part "Strawson_Eagle_Lib_CAP0805"))
    )
    (comp (ref "C39")
      (value "0.1uF")
      (footprint "eagle-import:0402-CAP")
      (libsource (lib "eagle-import") (part "Strawson_Eagle_Lib_CAP0402-CAP"))
    )
    (comp (ref "C40")
      (value "0.1uF")
      (footprint "eagle-import:0402-CAP")
      (libsource (lib "eagle-import") (part "Strawson_Eagle_Lib_CAP0402-CAP"))
    )
    (comp (ref "C41")
      (value "0.1uF")
      (footprint "eagle-import:0402-CAP")
      (libsource (lib "eagle-import") (part "Strawson_Eagle_Lib_CAP0402-CAP"))
    )
    (comp (ref "EMU0")
      (value "TPSQB1,27")
      (footprint "eagle-import:B1,27")
      (libsource (lib "eagle-import") (part "TPSQB1,27"))
    )
    (comp (ref "EMU1")
      (value "TPSQB1,27")
      (footprint "eagle-import:B1,27")
      (libsource (lib "eagle-import") (part "TPSQB1,27"))
    )
    (comp (ref "GND")
      (value "GHI2_TESTPAD/W_HOLE_1X1")
      (footprint "eagle-import:GHI2_TESTPAD_W_HOLE_1X1")
      (libsource (lib "eagle-import") (part "GHI2_TESTPAD/W_HOLE_1X1"))
    )
    (comp (ref "ON")
      (value "BLUE")
      (footprint "eagle-import:BEAGLEBONE_BLUE_LED-0603")
      (libsource (lib "eagle-import") (part "LED0603"))
    )
    (comp (ref "R2")
      (value "1.5K")
      (footprint "eagle-import:0402-RES")
      (libsource (lib "eagle-import") (part "RESISTOR0402-RES"))
    )
    (comp (ref "R15")
      (value "33")
      (footprint "eagle-import:0402-RES")
      (libsource (lib "eagle-import") (part "RESISTOR0402-RES"))
    )
    (comp (ref "R18")
      (value "1M")
      (footprint "eagle-import:0402-RES")
      (libsource (lib "eagle-import") (part "RESISTOR0402-RES"))
    )
    (comp (ref "R20")
      (value "1M")
      (footprint "eagle-import:0402-RES")
      (libsource (lib "eagle-import") (part "RESISTOR0402-RES"))
    )
    (comp (ref "R23")
      (value "1.5K")
      (footprint "eagle-import:0402-RES")
      (libsource (lib "eagle-import") (part "RESISTOR0402-RES"))
    )
    (comp (ref "R24")
      (value "4.7k")
      (footprint "eagle-import:0402-RES")
      (libsource (lib "eagle-import") (part "RESISTOR0402-RES"))
    )
    (comp (ref "R26")
      (value "10K")
      (footprint "eagle-import:0402-RES")
      (libsource (lib "eagle-import") (part "RESISTOR0402-RES"))
    )
    (comp (ref "R35")
      (value "10K")
      (footprint "eagle-import:0402-RES")
      (libsource (lib "eagle-import") (part "RESISTOR0402-RES"))
    )
    (comp (ref "R54")
      (value "10K")
      (footprint "eagle-import:0402-RES")
      (libsource (lib "eagle-import") (part "RESISTOR0402-RES"))
    )
    (comp (ref "R55")
      (value "10K")
      (footprint "eagle-import:0402-RES")
      (libsource (lib "eagle-import") (part "RESISTOR0402-RES"))
    )
    (comp (ref "R56")
      (value "10K")
      (footprint "eagle-import:0402-RES")
      (libsource (lib "eagle-import") (part "RESISTOR0402-RES"))
    )
    (comp (ref "R57")
      (value "10K")
      (footprint "eagle-import:0402-RES")
      (libsource (lib "eagle-import") (part "RESISTOR0402-RES"))
    )
    (comp (ref "R58")
      (value "1.5K")
      (footprint "eagle-import:0402-RES")
      (libsource (lib "eagle-import") (part "RESISTOR0402-RES"))
    )
    (comp (ref "R59")
      (value "4.7k")
      (footprint "eagle-import:0402-RES")
      (libsource (lib "eagle-import") (part "RESISTOR0402-RES"))
    )
    (comp (ref "R60")
      (value "10K")
      (footprint "eagle-import:0402-RES")
      (libsource (lib "eagle-import") (part "RESISTOR0402-RES"))
    )
    (comp (ref "R65")
      (value "10K")
      (footprint "eagle-import:0402-RES")
      (libsource (lib "eagle-import") (part "RESISTOR0402-RES"))
    )
    (comp (ref "R66")
      (value "10K")
      (footprint "eagle-import:0402-RES")
      (libsource (lib "eagle-import") (part "RESISTOR0402-RES"))
    )
    (comp (ref "R67")
      (value "10K")
      (footprint "eagle-import:0402-RES")
      (libsource (lib "eagle-import") (part "RESISTOR0402-RES"))
    )
    (comp (ref "R68")
      (value "10K")
      (footprint "eagle-import:0402-RES")
      (libsource (lib "eagle-import") (part "RESISTOR0402-RES"))
    )
    (comp (ref "R69")
      (value "10K")
      (footprint "eagle-import:0402-RES")
      (libsource (lib "eagle-import") (part "RESISTOR0402-RES"))
    )
    (comp (ref "R70")
      (value "10K")
      (footprint "eagle-import:0402-RES")
      (libsource (lib "eagle-import") (part "RESISTOR0402-RES"))
    )
    (comp (ref "R71")
      (value "10K")
      (footprint "eagle-import:0402-RES")
      (libsource (lib "eagle-import") (part "RESISTOR0402-RES"))
    )
    (comp (ref "R72")
      (value "10K")
      (footprint "eagle-import:0402-RES")
      (libsource (lib "eagle-import") (part "RESISTOR0402-RES"))
    )
    (comp (ref "R73")
      (value "10K")
      (footprint "eagle-import:0402-RES")
      (libsource (lib "eagle-import") (part "RESISTOR0402-RES"))
    )
    (comp (ref "R74")
      (value "10K")
      (footprint "eagle-import:0402-RES")
      (libsource (lib "eagle-import") (part "RESISTOR0402-RES"))
    )
    (comp (ref "R75")
      (value "10K")
      (footprint "eagle-import:0402-RES")
      (libsource (lib "eagle-import") (part "RESISTOR0402-RES"))
    )
    (comp (ref "R94")
      (value "10K")
      (footprint "eagle-import:0402-RES")
      (libsource (lib "eagle-import") (part "RESISTOR0402-RES"))
    )
    (comp (ref "R104")
      (value "120, DNP")
      (footprint "eagle-import:0603-RES")
      (libsource (lib "eagle-import") (part "RESISTOR0603"))
    )
    (comp (ref "SIP")
      (value "OSD3358")
      (footprint "eagle-import:BEAGLEBONE_BLUE_OSD3358")
      (libsource (lib "eagle-import") (part "OSD3358"))
    )
    (comp (ref "TCK")
      (value "TPSQB1,27")
      (footprint "eagle-import:B1,27")
      (libsource (lib "eagle-import") (part "TPSQB1,27"))
    )
    (comp (ref "TDI")
      (value "TPSQB1,27")
      (footprint "eagle-import:B1,27")
      (libsource (lib "eagle-import") (part "TPSQB1,27"))
    )
    (comp (ref "TDO")
      (value "TPSQB1,27")
      (footprint "eagle-import:B1,27")
      (libsource (lib "eagle-import") (part "TPSQB1,27"))
    )
    (comp (ref "TMS")
      (value "TPSQB1,27")
      (footprint "eagle-import:B1,27")
      (libsource (lib "eagle-import") (part "TPSQB1,27"))
    )
    (comp (ref "TP1")
      (value "TPSQB1,27")
      (footprint "eagle-import:B1,27")
      (libsource (lib "eagle-import") (part "TPSQB1,27"))
    )
    (comp (ref "TP5")
      (value "TPB0,65")
      (footprint "eagle-import:BEAGLEBONE_BLUE_B0,65")
      (libsource (lib "eagle-import") (part "TPB0,65"))
    )
    (comp (ref "TP12")
      (value "TPSQB1,27")
      (footprint "eagle-import:B1,27")
      (libsource (lib "eagle-import") (part "TPSQB1,27"))
    )
    (comp (ref "TRSTN")
      (value "TPSQB1,27")
      (footprint "eagle-import:B1,27")
      (libsource (lib "eagle-import") (part "TPSQB1,27"))
    )
    (comp (ref "U1")
      (value "TCAN1051HV")
      (footprint "eagle-import:BEAGLEBONE_BLUE_D8")
      (fields
        (field (name "MANUFACTURER") "Texas Instruments")
        (field (name "MANUFACTURER_PART_NUMBER") "TCAN1051HVD")
      )
      (libsource (lib "eagle-import") (part "TCAN1051HV"))
    )
    (comp (ref "U5")
      (value "24LC_32AT-I/OT")
      (footprint "eagle-import:SOT95P290X145-5N")
      (fields (field (name "MPN") "24LC32AT-I/OT"))
      (libsource (lib "eagle-import") (part "24LC_32AT-I/OT"))
    )
    (comp (ref "U6")
      (value "SN74LVC1G07_DCK_5")
      (footprint "eagle-import:BEAGLEBONE_BLUE_DCK5")
      (fields
        (field (name "GENERIC_PART_NUMBER") "SN74LVC1G07")
        (field (name "MANUFACTURER") "Texas Instruments")
        (field (name "MANUFACTURER_PART_NUMBER") "sn74lvc1g07_dck_5")
      )
      (libsource (lib "eagle-import") (part "SN74LVC1G07_DCK_5"))
    )
    (comp (ref "U13")
      (value "EMMC")
      (footprint "eagle-import:MICRON_EMMC_153")
      (libsource (lib "eagle-import") (part "EMMC04G-S100-B08U"))
    )
    (comp (ref "WP")
      (value "GHI2_TESTPAD/W_HOLE_1X1")
      (footprint "eagle-import:GHI2_TESTPAD_W_HOLE_1X1")
      (libsource (lib "eagle-import") (part "GHI2_TESTPAD/W_HOLE_1X1"))
    )
    (comp (ref "X2")
      (value "SCHA5B0200")
      (footprint "eagle-import:SCHA5B0200")
      (libsource (lib "eagle-import") (part "SCHA5B0200(ALPS_USD)"))
    )
    (comp (ref "Y1")
      (value "24 MHz")
      (footprint "eagle-import:CRYSTAL_5X3.2MM")
      (libsource (lib "eagle-import") (part "CRYSTAL_5X3.2MM"))
    )
    (comp (ref "Y2")
      (value "32.768kHz")
      (footprint "eagle-import:CRYSTAL_3.2X1.5")
      (libsource (lib "eagle-import") (part "CRYSTAL_3.2X1.5"))
    )
    (comp (ref "FUD1")
      (value "FIDUCIAL")
      (footprint "eagle-import:FIDUCIAL_40MIL")
      (libsource (lib "eagle-import") (part "FIDUCIAL"))
    )
    (comp (ref "FUD2")
      (value "FIDUCIAL")
      (footprint "eagle-import:FIDUCIAL_40MIL")
      (libsource (lib "eagle-import") (part "FIDUCIAL"))
    )
    (comp (ref "FUD3")
      (value "FIDUCIAL")
      (footprint "eagle-import:FIDUCIAL_40MIL")
      (libsource (lib "eagle-import") (part "FIDUCIAL"))
    )
    (comp (ref "FUD4")
      (value "FIDUCIAL")
      (footprint "eagle-import:FIDUCIAL_40MIL")
      (libsource (lib "eagle-import") (part "FIDUCIAL"))
    )
    (comp (ref "FUD5")
      (value "FIDUCIAL")
      (footprint "eagle-import:FIDUCIAL_40MIL")
      (libsource (lib "eagle-import") (part "FIDUCIAL"))
    )
    (comp (ref "FUD6")
      (value "FIDUCIAL")
      (footprint "eagle-import:FIDUCIAL_40MIL")
      (libsource (lib "eagle-import") (part "FIDUCIAL"))
    )
    (comp (ref "MGT1")
      (value "MOUNTING_HOLE")
      (footprint "eagle-import:MOUNTING_HOLE")
      (libsource (lib "eagle-import") (part "MOUNTING_HOLE"))
    )
    (comp (ref "MGT2")
      (value "MOUNTING_HOLE")
      (footprint "eagle-import:MOUNTING_HOLE")
      (libsource (lib "eagle-import") (part "MOUNTING_HOLE"))
    )
    (comp (ref "MGT3")
      (value "MOUNTING_HOLE")
      (footprint "eagle-import:MOUNTING_HOLE")
      (libsource (lib "eagle-import") (part "MOUNTING_HOLE"))
    )
    (comp (ref "MGT4")
      (value "MOUNTING_HOLE")
      (footprint "eagle-import:MOUNTING_HOLE")
      (libsource (lib "eagle-import") (part "MOUNTING_HOLE"))
    )
    (comp (ref "R158")
      (value "10K")
      (footprint "eagle-import:0402-RES")
      (libsource (lib "eagle-import") (part "RESISTOR0402-RES"))
    )
    (comp (ref "C42")
      (value "1nF")
      (footprint "eagle-import:0402-CAP")
      (libsource (lib "eagle-import") (part "Strawson_Eagle_Lib_CAP0402-CAP"))
    )
    (comp (ref "C43")
      (value "0.1uF")
      (footprint "eagle-import:0402-CAP")
      (libsource (lib "eagle-import") (part "Strawson_Eagle_Lib_CAP0402-CAP"))
    )
    (comp (ref "C44")
      (value "0.1uF")
      (footprint "eagle-import:0402-CAP")
      (libsource (lib "eagle-import") (part "Strawson_Eagle_Lib_CAP0402-CAP"))
    )
    (comp (ref "C45")
      (value "0.1uF")
      (footprint "eagle-import:0402-CAP")
      (libsource (lib "eagle-import") (part "Strawson_Eagle_Lib_CAP0402-CAP"))
    )
    (comp (ref "C46")
      (value "10uF")
      (footprint "eagle-import:0805")
      (libsource (lib "eagle-import") (part "Strawson_Eagle_Lib_CAP0805"))
    )
    (comp (ref "C54")
      (value "0.1uF")
      (footprint "eagle-import:0402-CAP")
      (libsource (lib "eagle-import") (part "Strawson_Eagle_Lib_CAP0402-CAP"))
    )
    (comp (ref "C55")
      (value "0.1uF")
      (footprint "eagle-import:0402-CAP")
      (libsource (lib "eagle-import") (part "Strawson_Eagle_Lib_CAP0402-CAP"))
    )
    (comp (ref "C61")
      (value "1uF")
      (footprint "eagle-import:0402-CAP")
      (libsource (lib "eagle-import") (part "Strawson_Eagle_Lib_CAP0402-CAP"))
    )
    (comp (ref "C62")
      (value "0.22uF")
      (footprint "eagle-import:0402-CAP")
      (libsource (lib "eagle-import") (part "Strawson_Eagle_Lib_CAP0402-CAP"))
    )
    (comp (ref "C63")
      (value "0.22uF")
      (footprint "eagle-import:0402-CAP")
      (libsource (lib "eagle-import") (part "Strawson_Eagle_Lib_CAP0402-CAP"))
    )
    (comp (ref "L4")
      (value "120")
      (footprint "eagle-import:L0603")
      (libsource (lib "eagle-import") (part "INDUCTOR/FERRITE-BEAD'0603'"))
    )
    (comp (ref "L5")
      (value "120")
      (footprint "eagle-import:L0603")
      (libsource (lib "eagle-import") (part "INDUCTOR/FERRITE-BEAD'0603'"))
    )
    (comp (ref "R16")
      (value "100K")
      (footprint "eagle-import:0402-RES")
      (libsource (lib "eagle-import") (part "RESISTOR0402-RES"))
    )
    (comp (ref "R17")
      (value "100K")
      (footprint "eagle-import:0402-RES")
      (libsource (lib "eagle-import") (part "RESISTOR0402-RES"))
    )
    (comp (ref "R76")
      (value "33")
      (footprint "eagle-import:0402-RES")
      (libsource (lib "eagle-import") (part "RESISTOR0402-RES"))
    )
    (comp (ref "R77")
      (value "33")
      (footprint "eagle-import:0402-RES")
      (libsource (lib "eagle-import") (part "RESISTOR0402-RES"))
    )
    (comp (ref "R95")
      (value "100K")
      (footprint "eagle-import:0402-RES")
      (libsource (lib "eagle-import") (part "RESISTOR0402-RES"))
    )
    (comp (ref "R109")
      (value "4.7k")
      (footprint "eagle-import:0402-RES")
      (libsource (lib "eagle-import") (part "RESISTOR0402-RES"))
    )
    (comp (ref "R110")
      (value "4.7k")
      (footprint "eagle-import:0402-RES")
      (libsource (lib "eagle-import") (part "RESISTOR0402-RES"))
    )
    (comp (ref "R111")
      (value "0")
      (footprint "eagle-import:0402-RES")
      (libsource (lib "eagle-import") (part "RESISTOR0402-RES"))
    )
    (comp (ref "R112")
      (value "0")
      (footprint "eagle-import:0603-RES")
      (libsource (lib "eagle-import") (part "RESISTOR0603"))
    )
    (comp (ref "R113")
      (value "100K")
      (footprint "eagle-import:0402-RES")
      (libsource (lib "eagle-import") (part "RESISTOR0402-RES"))
    )
    (comp (ref "R115")
      (value "100K")
      (footprint "eagle-import:0402-RES")
      (libsource (lib "eagle-import") (part "RESISTOR0402-RES"))
    )
    (comp (ref "R116")
      (value "100K")
      (footprint "eagle-import:0402-RES")
      (libsource (lib "eagle-import") (part "RESISTOR0402-RES"))
    )
    (comp (ref "R118")
      (value "100K")
      (footprint "eagle-import:0402-RES")
      (libsource (lib "eagle-import") (part "RESISTOR0402-RES"))
    )
    (comp (ref "R119")
      (value "0, DNP")
      (footprint "eagle-import:0603-RES")
      (libsource (lib "eagle-import") (part "RESISTOR0603"))
    )
    (comp (ref "R120")
      (value "100K")
      (footprint "eagle-import:0402-RES")
      (libsource (lib "eagle-import") (part "RESISTOR0402-RES"))
    )
    (comp (ref "R121")
      (value "0, DNP")
      (footprint "eagle-import:0603-RES")
      (libsource (lib "eagle-import") (part "RESISTOR0603"))
    )
    (comp (ref "R122")
      (value "100K")
      (footprint "eagle-import:0402-RES")
      (libsource (lib "eagle-import") (part "RESISTOR0402-RES"))
    )
    (comp (ref "R125")
      (value "100K")
      (footprint "eagle-import:0402-RES")
      (libsource (lib "eagle-import") (part "RESISTOR0402-RES"))
    )
    (comp (ref "R127")
      (value "100K")
      (footprint "eagle-import:0402-RES")
      (libsource (lib "eagle-import") (part "RESISTOR0402-RES"))
    )
    (comp (ref "R129")
      (value "100K")
      (footprint "eagle-import:0402-RES")
      (libsource (lib "eagle-import") (part "RESISTOR0402-RES"))
    )
    (comp (ref "R131")
      (value "100K")
      (footprint "eagle-import:0402-RES")
      (libsource (lib "eagle-import") (part "RESISTOR0402-RES"))
    )
    (comp (ref "R135")
      (value "100K")
      (footprint "eagle-import:0402-RES")
      (libsource (lib "eagle-import") (part "RESISTOR0402-RES"))
    )
    (comp (ref "R140")
      (value "100K")
      (footprint "eagle-import:0402-RES")
      (libsource (lib "eagle-import") (part "RESISTOR0402-RES"))
    )
    (comp (ref "R143")
      (value "100K")
      (footprint "eagle-import:0402-RES")
      (libsource (lib "eagle-import") (part "RESISTOR0402-RES"))
    )
    (comp (ref "R149")
      (value "0")
      (footprint "eagle-import:0402-RES")
      (libsource (lib "eagle-import") (part "RESISTOR0402-RES"))
    )
    (comp (ref "R150")
      (value "0")
      (footprint "eagle-import:0402-RES")
      (libsource (lib "eagle-import") (part "RESISTOR0402-RES"))
    )
    (comp (ref "R156")
      (value "33")
      (footprint "eagle-import:0402-RES")
      (libsource (lib "eagle-import") (part "RESISTOR0402-RES"))
    )
    (comp (ref "U3")
      (value "TPD4S012DRY")
      (footprint "eagle-import:SON-6(TI)-DRY")
      (libsource (lib "eagle-import") (part "TPD4S012DRYR"))
    )
    (comp (ref "U4")
      (value "TPD4S012DRY")
      (footprint "eagle-import:SON-6(TI)-DRY")
      (libsource (lib "eagle-import") (part "TPD4S012DRYR"))
    )
    (comp (ref "U8")
      (value "TPS2105_DBV_5")
      (footprint "eagle-import:DBV5")
      (fields
        (field (name "GENERIC_PART_NUMBER") "TPS2105")
        (field (name "MANUFACTURER") "Texas Instruments")
        (field (name "MANUFACTURER_PART_NUMBER") "tps2105_dbv_5")
      )
      (libsource (lib "eagle-import") (part "TPS2105_DBV_5"))
    )
    (comp (ref "X3")
      (value "USB1")
      (footprint "eagle-import:USB_HOST_HORIZONTAL_W_CHASSIS_GND")
      (libsource (lib "eagle-import") (part "USB_HOST_W/CHASSIS_GND"))
    )
    (comp (ref "X4")
      (value "10118192-0001LF")
      (footprint "eagle-import:10118192-0001LF(MICRO-USB-B-AMPHENOL-FCI)")
      (libsource (lib "eagle-import") (part "10118192-0001LF"))
    )
    (comp (ref "ANT1")
      (value "U.FL-R-SMT-1(10)")
      (footprint "eagle-import:U.FL-R-SMT-1")
      (libsource (lib "eagle-import") (part "U.FL-R-SMT-1"))
    )
    (comp (ref "ANT2")
      (value "U.FL-R-SMT-1(10)")
      (footprint "eagle-import:U.FL-R-SMT-1")
      (libsource (lib "eagle-import") (part "U.FL-R-SMT-1"))
    )
    (comp (ref "C47")
      (value "0.1uF")
      (footprint "eagle-import:0402-CAP")
      (libsource (lib "eagle-import") (part "Strawson_Eagle_Lib_CAP0402-CAP"))
    )
    (comp (ref "C48")
      (value "10pF")
      (footprint "eagle-import:0402-CAP")
      (libsource (lib "eagle-import") (part "Strawson_Eagle_Lib_CAP0402-CAP"))
    )
    (comp (ref "C49")
      (value "0.1uF")
      (footprint "eagle-import:0402-CAP")
      (libsource (lib "eagle-import") (part "Strawson_Eagle_Lib_CAP0402-CAP"))
    )
    (comp (ref "C50")
      (value "0.1uF")
      (footprint "eagle-import:0402-CAP")
      (libsource (lib "eagle-import") (part "Strawson_Eagle_Lib_CAP0402-CAP"))
    )
    (comp (ref "C51")
      (value "0.1uF")
      (footprint "eagle-import:0402-CAP")
      (libsource (lib "eagle-import") (part "Strawson_Eagle_Lib_CAP0402-CAP"))
    )
    (comp (ref "C52")
      (value "0.1uF")
      (footprint "eagle-import:0402-CAP")
      (libsource (lib "eagle-import") (part "Strawson_Eagle_Lib_CAP0402-CAP"))
    )
    (comp (ref "C53")
      (value "10uF")
      (footprint "eagle-import:0805")
      (libsource (lib "eagle-import") (part "CAP0805"))
    )
    (comp (ref "C56")
      (value "0.1uF")
      (footprint "eagle-import:0402-CAP")
      (libsource (lib "eagle-import") (part "Strawson_Eagle_Lib_CAP0402-CAP"))
    )
    (comp (ref "C57")
      (value "1uF")
      (footprint "eagle-import:0402-CAP")
      (libsource (lib "eagle-import") (part "Strawson_Eagle_Lib_CAP0402-CAP"))
    )
    (comp (ref "C58")
      (value "10pF")
      (footprint "eagle-import:0402-CAP")
      (libsource (lib "eagle-import") (part "Strawson_Eagle_Lib_CAP0402-CAP"))
    )
    (comp (ref "C59")
      (value "10uF")
      (footprint "eagle-import:0805")
      (libsource (lib "eagle-import") (part "CAP0805"))
    )
    (comp (ref "C60")
      (value "10uF")
      (footprint "eagle-import:0805")
      (libsource (lib "eagle-import") (part "CAP0805"))
    )
    (comp (ref "OSC1")
      (value "NZ2520SB-32.768KHZ-NSA3534C")
      (footprint "eagle-import:NZ2520S")
      (libsource (lib "eagle-import") (part "OSCILLATOR"))
    )
    (comp (ref "R9")
      (value "10K, DNP")
      (footprint "eagle-import:0402-RES")
      (libsource (lib "eagle-import") (part "RESISTOR0402-RES"))
    )
    (comp (ref "R78")
      (value "33")
      (footprint "eagle-import:0402-RES")
      (libsource (lib "eagle-import") (part "RESISTOR0402-RES"))
    )
    (comp (ref "R79")
      (value "33")
      (footprint "eagle-import:0402-RES")
      (libsource (lib "eagle-import") (part "RESISTOR0402-RES"))
    )
    (comp (ref "R80")
      (value "33")
      (footprint "eagle-import:0402-RES")
      (libsource (lib "eagle-import") (part "RESISTOR0402-RES"))
    )
    (comp (ref "R81")
      (value "33")
      (footprint "eagle-import:0402-RES")
      (libsource (lib "eagle-import") (part "RESISTOR0402-RES"))
    )
    (comp (ref "R82")
      (value "33")
      (footprint "eagle-import:0402-RES")
      (libsource (lib "eagle-import") (part "RESISTOR0402-RES"))
    )
    (comp (ref "R83")
      (value "33")
      (footprint "eagle-import:0402-RES")
      (libsource (lib "eagle-import") (part "RESISTOR0402-RES"))
    )
    (comp (ref "R84")
      (value "33")
      (footprint "eagle-import:0402-RES")
      (libsource (lib "eagle-import") (part "RESISTOR0402-RES"))
    )
    (comp (ref "R85")
      (value "33")
      (footprint "eagle-import:0402-RES")
      (libsource (lib "eagle-import") (part "RESISTOR0402-RES"))
    )
    (comp (ref "R86")
      (value "33")
      (footprint "eagle-import:0402-RES")
      (libsource (lib "eagle-import") (part "RESISTOR0402-RES"))
    )
    (comp (ref "R87")
      (value "100K")
      (footprint "eagle-import:0402-RES")
      (libsource (lib "eagle-import") (part "RESISTOR0402-RES"))
    )
    (comp (ref "R88")
      (value "100K")
      (footprint "eagle-import:0402-RES")
      (libsource (lib "eagle-import") (part "RESISTOR0402-RES"))
    )
    (comp (ref "R89")
      (value "1K, DNP")
      (footprint "eagle-import:0402-RES")
      (libsource (lib "eagle-import") (part "RESISTOR0402-RES"))
    )
    (comp (ref "R90")
      (value "1K")
      (footprint "eagle-import:0402-RES")
      (libsource (lib "eagle-import") (part "RESISTOR0402-RES"))
    )
    (comp (ref "R92")
      (value "33")
      (footprint "eagle-import:0402-RES")
      (libsource (lib "eagle-import") (part "RESISTOR0402-RES"))
    )
    (comp (ref "R93")
      (value "33")
      (footprint "eagle-import:0402-RES")
      (libsource (lib "eagle-import") (part "RESISTOR0402-RES"))
    )
    (comp (ref "R96")
      (value "33")
      (footprint "eagle-import:0402-RES")
      (libsource (lib "eagle-import") (part "RESISTOR0402-RES"))
    )
    (comp (ref "R97")
      (value "33")
      (footprint "eagle-import:0402-RES")
      (libsource (lib "eagle-import") (part "RESISTOR0402-RES"))
    )
    (comp (ref "R98")
      (value "10K")
      (footprint "eagle-import:0402-RES")
      (libsource (lib "eagle-import") (part "RESISTOR0402-RES"))
    )
    (comp (ref "R99")
      (value "10K")
      (footprint "eagle-import:0402-RES")
      (libsource (lib "eagle-import") (part "RESISTOR0402-RES"))
    )
    (comp (ref "R100")
      (value "33")
      (footprint "eagle-import:0402-RES")
      (libsource (lib "eagle-import") (part "RESISTOR0402-RES"))
    )
    (comp (ref "R101")
      (value "10K")
      (footprint "eagle-import:0402-RES")
      (libsource (lib "eagle-import") (part "RESISTOR0402-RES"))
    )
    (comp (ref "R102")
      (value "10K")
      (footprint "eagle-import:0402-RES")
      (libsource (lib "eagle-import") (part "RESISTOR0402-RES"))
    )
    (comp (ref "R103")
      (value "10K")
      (footprint "eagle-import:0402-RES")
      (libsource (lib "eagle-import") (part "RESISTOR0402-RES"))
    )
    (comp (ref "R105")
      (value "10K")
      (footprint "eagle-import:0402-RES")
      (libsource (lib "eagle-import") (part "RESISTOR0402-RES"))
    )
    (comp (ref "R106")
      (value "1.5K")
      (footprint "eagle-import:0402-RES")
      (libsource (lib "eagle-import") (part "RESISTOR0402-RES"))
    )
    (comp (ref "R108")
      (value "1K, DNP")
      (footprint "eagle-import:0402-RES")
      (libsource (lib "eagle-import") (part "RESISTOR0402-RES"))
    )
    (comp (ref "R123")
      (value "33")
      (footprint "eagle-import:0402-RES")
      (libsource (lib "eagle-import") (part "RESISTOR0402-RES"))
    )
    (comp (ref "R124")
      (value "33")
      (footprint "eagle-import:0402-RES")
      (libsource (lib "eagle-import") (part "RESISTOR0402-RES"))
    )
    (comp (ref "U2")
      (value "SN74LV1T126DBVR")
      (footprint "eagle-import:BEAGLEBONE_BLUE_SOT23-5")
      (libsource (lib "eagle-import") (part "SN74LV1T126DBVR"))
    )
    (comp (ref "U7")
      (value "WL1835MODGBMOCT")
      (footprint "eagle-import:MOC-100(TI)")
      (libsource (lib "eagle-import") (part "WL1835MOD"))
    )
    (comp (ref "U9")
      (value "TXS0108ERGYR")
      (footprint "eagle-import:R-PVQFN-N20(TI)")
      (libsource (lib "eagle-import") (part "TXS0108ERGYR"))
    )
    (comp (ref "U10")
      (value "TXS0108ERGYR")
      (footprint "eagle-import:R-PVQFN-N20(TI)")
      (libsource (lib "eagle-import") (part "TXS0108ERGYR"))
    )
  )
  (nets
    (net (code "1") (name "3.3V") (class "Default")
      (node (ref "BMP") (pin "2") (pinfunction "CSB_2") (pintype "input"))
      (node (ref "BMP") (pin "6") (pinfunction "VDDIO_6") (pintype "input"))
      (node (ref "BMP") (pin "8") (pinfunction "VDD_8") (pintype "power_in"))
      (node (ref "C13") (pin "1") (pinfunction "1_1") (pintype "passive"))
      (node (ref "C16") (pin "1") (pinfunction "1_1") (pintype "passive"))
      (node (ref "C2") (pin "2") (pinfunction "2_2") (pintype "passive"))
      (node (ref "C27") (pin "1") (pinfunction "1_1") (pintype "passive"))
      (node (ref "C28") (pin "1") (pinfunction "1_1") (pintype "passive"))
      (node (ref "C34") (pin "2") (pinfunction "2_2") (pintype "passive"))
      (node (ref "C35") (pin "2") (pinfunction "2_2") (pintype "passive"))
      (node (ref "C37") (pin "1") (pinfunction "1_1") (pintype "passive"))
      (node (ref "C38") (pin "1") (pinfunction "1_1") (pintype "passive"))
      (node (ref "C39") (pin "1") (pinfunction "1_1") (pintype "passive"))
      (node (ref "C40") (pin "1") (pinfunction "1_1") (pintype "passive"))
      (node (ref "C41") (pin "1") (pinfunction "1_1") (pintype "passive"))
      (node (ref "C49") (pin "2") (pinfunction "2_2") (pintype "passive"))
      (node (ref "C51") (pin "2") (pinfunction "2_2") (pintype "passive"))
      (node (ref "C53") (pin "1") (pinfunction "1_1") (pintype "passive"))
      (node (ref "C56") (pin "1") (pinfunction "1_1") (pintype "passive"))
      (node (ref "C59") (pin "1") (pinfunction "1_1") (pintype "passive"))
      (node (ref "C8") (pin "1") (pinfunction "1_1") (pintype "passive"))
      (node (ref "C9") (pin "2") (pinfunction "2_2") (pintype "passive"))
      (node (ref "CAN") (pin "2") (pinfunction "2_2") (pintype "bidirectional"))
      (node (ref "DSM2") (pin "P$1") (pinfunction "1_P$1") (pintype "bidirectional"))
      (node (ref "E1") (pin "2") (pinfunction "2_2") (pintype "bidirectional"))
      (node (ref "E2") (pin "2") (pinfunction "2_2") (pintype "bidirectional"))
      (node (ref "E3") (pin "2") (pinfunction "2_2") (pintype "bidirectional"))
      (node (ref "E4") (pin "2") (pinfunction "2_2") (pintype "bidirectional"))
      (node (ref "GP0") (pin "2") (pinfunction "2_2") (pintype "bidirectional"))
      (node (ref "GP1") (pin "2") (pinfunction "2_2") (pintype "bidirectional"))
      (node (ref "H1") (pin "20") (pinfunction "VCC_20") (pintype "bidirectional"))
      (node (ref "H2") (pin "20") (pinfunction "VCC_20") (pintype "bidirectional"))
      (node (ref "I2C") (pin "2") (pinfunction "2_2") (pintype "bidirectional"))
      (node (ref "IMU") (pin "1") (pinfunction "RESV_1") (pintype "bidirectional"))
      (node (ref "IMU") (pin "13") (pinfunction "VDD_13") (pintype "bidirectional"))
      (node (ref "IMU") (pin "22") (pinfunction "NCS_22") (pintype "bidirectional"))
      (node (ref "IMU") (pin "8") (pinfunction "VDDIO_8") (pintype "bidirectional"))
      (node (ref "PWR") (pin "3") (pinfunction "3_3") (pintype "bidirectional"))
      (node (ref "R10") (pin "1") (pinfunction "1_1") (pintype "passive"))
      (node (ref "R109") (pin "1") (pinfunction "1_1") (pintype "passive"))
      (node (ref "R11") (pin "2") (pinfunction "2_2") (pintype "passive"))
      (node (ref "R116") (pin "2") (pinfunction "2_2") (pintype "passive"))
      (node (ref "R118") (pin "2") (pinfunction "2_2") (pintype "passive"))
      (node (ref "R12") (pin "2") (pinfunction "2_2") (pintype "passive"))
      (node (ref "R120") (pin "2") (pinfunction "2_2") (pintype "passive"))
      (node (ref "R122") (pin "2") (pinfunction "2_2") (pintype "passive"))
      (node (ref "R13") (pin "1") (pinfunction "1_1") (pintype "passive"))
      (node (ref "R140") (pin "2") (pinfunction "2_2") (pintype "passive"))
      (node (ref "R2") (pin "2") (pinfunction "2_2") (pintype "passive"))
      (node (ref "R23") (pin "2") (pinfunction "2_2") (pintype "passive"))
      (node (ref "R26") (pin "2") (pinfunction "2_2") (pintype "passive"))
      (node (ref "R35") (pin "2") (pinfunction "2_2") (pintype "passive"))
      (node (ref "R54") (pin "2") (pinfunction "2_2") (pintype "passive"))
      (node (ref "R55") (pin "2") (pinfunction "2_2") (pintype "passive"))
      (node (ref "R56") (pin "2") (pinfunction "2_2") (pintype "passive"))
      (node (ref "R57") (pin "2") (pinfunction "2_2") (pintype "passive"))
      (node (ref "R58") (pin "2") (pinfunction "2_2") (pintype "passive"))
      (node (ref "R60") (pin "2") (pinfunction "2_2") (pintype "passive"))
      (node (ref "R65") (pin "2") (pinfunction "2_2") (pintype "passive"))
      (node (ref "R66") (pin "2") (pinfunction "2_2") (pintype "passive"))
      (node (ref "R67") (pin "2") (pinfunction "2_2") (pintype "passive"))
      (node (ref "R68") (pin "2") (pinfunction "2_2") (pintype "passive"))
      (node (ref "R69") (pin "2") (pinfunction "2_2") (pintype "passive"))
      (node (ref "R70") (pin "2") (pinfunction "2_2") (pintype "passive"))
      (node (ref "R71") (pin "2") (pinfunction "2_2") (pintype "passive"))
      (node (ref "R72") (pin "2") (pinfunction "2_2") (pintype "passive"))
      (node (ref "R73") (pin "2") (pinfunction "2_2") (pintype "passive"))
      (node (ref "R74") (pin "2") (pinfunction "2_2") (pintype "passive"))
      (node (ref "R75") (pin "2") (pinfunction "2_2") (pintype "passive"))
      (node (ref "R94") (pin "2") (pinfunction "2_2") (pintype "passive"))
      (node (ref "S1.1") (pin "2") (pinfunction "2_2") (pintype "bidirectional"))
      (node (ref "S1.2") (pin "2") (pinfunction "2_2") (pintype "bidirectional"))
      (node (ref "SIP") (pin "U20") (pinfunction "VOUT_USER_3P3V_0_U20") (pintype "power_in"))
      (node (ref "SIP") (pin "V20") (pinfunction "VOUT_USER_3P3V_1_V20") (pintype "power_in"))
      (node (ref "U1") (pin "5") (pinfunction "VIO_5") (pintype "power_in"))
      (node (ref "U10") (pin "19") (pinfunction "VCCB_19") (pintype "bidirectional"))
      (node (ref "U13") (pin "C6") (pinfunction "VCCQ1_C6") (pintype "bidirectional"))
      (node (ref "U13") (pin "E6") (pinfunction "VCC1_E6") (pintype "bidirectional"))
      (node (ref "U13") (pin "F5") (pinfunction "VCC2_F5") (pintype "bidirectional"))
      (node (ref "U13") (pin "J10") (pinfunction "VCC3_J10") (pintype "bidirectional"))
      (node (ref "U13") (pin "K9") (pinfunction "VCC4_K9") (pintype "bidirectional"))
      (node (ref "U13") (pin "M4") (pinfunction "VCCQ2_M4") (pintype "bidirectional"))
      (node (ref "U13") (pin "N4") (pinfunction "VCCQ3_N4") (pintype "bidirectional"))
      (node (ref "U13") (pin "P3") (pinfunction "VCCQ4_P3") (pintype "bidirectional"))
      (node (ref "U13") (pin "P5") (pinfunction "VCCQ5_P5") (pintype "bidirectional"))
      (node (ref "U5") (pin "4") (pinfunction "VCC_4") (pintype "power_in"))
      (node (ref "U7") (pin "46") (pinfunction "VBAT_IN1_46") (pintype "bidirectional"))
      (node (ref "U7") (pin "47") (pinfunction "VBAT_IN2_47") (pintype "bidirectional"))
      (node (ref "U9") (pin "19") (pinfunction "VCCB_19") (pintype "bidirectional"))
      (node (ref "UT0") (pin "2") (pinfunction "2_2") (pintype "bidirectional"))
      (node (ref "UT1") (pin "2") (pinfunction "2_2") (pintype "bidirectional"))
      (node (ref "UT5") (pin "2") (pinfunction "2_2") (pintype "bidirectional"))
      (node (ref "X2") (pin "4") (pinfunction "VDD_4") (pintype "bidirectional"))
    )
    (net (code "2") (name "5.0V") (class "Default")
      (node (ref "5VREG") (pin "3") (pinfunction "FB_3") (pintype "power_in"))
      (node (ref "C5") (pin "1") (pinfunction "1_1") (pintype "passive"))
      (node (ref "C63") (pin "1") (pinfunction "1_1") (pintype "passive"))
      (node (ref "GPS") (pin "5") (pinfunction "5_5") (pintype "bidirectional"))
      (node (ref "L1") (pin "2") (pinfunction "2_2") (pintype "passive"))
      (node (ref "PWR") (pin "4") (pinfunction "4_4") (pintype "bidirectional"))
      (node (ref "R119") (pin "2") (pinfunction "2_2") (pintype "passive"))
      (node (ref "R95") (pin "2") (pinfunction "2_2") (pintype "passive"))
      (node (ref "SIP") (pin "Y5") (pinfunction "VIN_AC_0_Y5") (pintype "power_in"))
      (node (ref "SIP") (pin "Y6") (pinfunction "VIN_AC_1_Y6") (pintype "power_in"))
      (node (ref "U8") (pin "1") (pinfunction "EN_1") (pintype "input"))
      (node (ref "U8") (pin "5") (pinfunction "IN1_5") (pintype "input"))
    )
    (net (code "3") (name "32.768KHZ") (class "Default")
      (node (ref "OSC1") (pin "3") (pinfunction "OUT_3") (pintype "bidirectional"))
      (node (ref "U7") (pin "36") (pinfunction "EXT_32K_36") (pintype "bidirectional"))
    )
    (net (code "4") (name "AIN0") (class "Default")
      (node (ref "ADC") (pin "3") (pinfunction "3_3") (pintype "bidirectional"))
      (node (ref "SIP") (pin "B6") (pinfunction "AIN0_B6") (pintype "bidirectional"))
    )
    (net (code "5") (name "AIN1") (class "Default")
      (node (ref "ADC") (pin "4") (pinfunction "4_4") (pintype "bidirectional"))
      (node (ref "SIP") (pin "C7") (pinfunction "AIN1_C7") (pintype "bidirectional"))
    )
    (net (code "6") (name "AIN2") (class "Default")
      (node (ref "ADC") (pin "5") (pinfunction "5_5") (pintype "bidirectional"))
      (node (ref "SIP") (pin "B7") (pinfunction "AIN2_B7") (pintype "bidirectional"))
    )
    (net (code "7") (name "AIN3") (class "Default")
      (node (ref "ADC") (pin "6") (pinfunction "6_6") (pintype "bidirectional"))
      (node (ref "SIP") (pin "A7") (pinfunction "AIN3_A7") (pintype "bidirectional"))
    )
    (net (code "8") (name "BATT_LED_1") (class "Default")
      (node (ref "B0") (pin "A") (pinfunction "A_A") (pintype "passive"))
      (node (ref "SIP") (pin "U12") (pinfunction "GPIO0_27_U12_U12") (pintype "bidirectional"))
    )
    (net (code "9") (name "BATT_LED_2") (class "Default")
      (node (ref "B1") (pin "A") (pinfunction "A_A") (pintype "passive"))
      (node (ref "R143") (pin "2") (pinfunction "2_2") (pintype "passive"))
      (node (ref "SIP") (pin "T5") (pinfunction "LCD_DATA15_T5_T5") (pintype "bidirectional"))
    )
    (net (code "10") (name "BATT_LED_3") (class "Default")
      (node (ref "B2") (pin "A") (pinfunction "A_A") (pintype "passive"))
      (node (ref "SIP") (pin "V6") (pinfunction "GPIO1_29_V6_V6") (pintype "bidirectional"))
    )
    (net (code "11") (name "BATT_LED_4") (class "Default")
      (node (ref "B3") (pin "A") (pinfunction "A_A") (pintype "passive"))
      (node (ref "SIP") (pin "T11") (pinfunction "GPIO0_26_T11_T11") (pintype "bidirectional"))
    )
    (net (code "12") (name "BATT_MID") (class "Default")
      (node (ref "LIPO") (pin "P$2") (pinfunction "2_P$2") (pintype "passive"))
      (node (ref "R27") (pin "1") (pinfunction "1_1") (pintype "passive"))
      (node (ref "R30") (pin "1") (pinfunction "1_1") (pintype "passive"))
      (node (ref "R44") (pin "1") (pinfunction "1_1") (pintype "passive"))
    )
    (net (code "13") (name "BATT_MINUS") (class "Default")
      (node (ref "BAL") (pin "5") (pinfunction "GND_5") (pintype "bidirectional"))
      (node (ref "BAL") (pin "6") (pinfunction "CB_EN_6") (pintype "bidirectional"))
      (node (ref "C1") (pin "2") (pinfunction "2_2") (pintype "passive"))
      (node (ref "C15") (pin "1") (pinfunction "1_1") (pintype "passive"))
      (node (ref "C18") (pin "1") (pinfunction "1_1") (pintype "passive"))
      (node (ref "C19") (pin "2") (pinfunction "2_2") (pintype "passive"))
      (node (ref "LIPO") (pin "P$3") (pinfunction "3_P$3") (pintype "passive"))
      (node (ref "PROT") (pin "2") (pinfunction "VM_2") (pintype "bidirectional"))
      (node (ref "PROT") (pin "6") (pinfunction "VSS_6") (pintype "bidirectional"))
      (node (ref "Q1") (pin "1") (pinfunction "S_1") (pintype "passive"))
      (node (ref "Q1") (pin "2") (pinfunction "S_2") (pintype "passive"))
      (node (ref "Q1") (pin "3") (pinfunction "S_3") (pintype "passive"))
    )
    (net (code "14") (name "BT_AUD_CLK") (class "Default")
      (node (ref "R124") (pin "1") (pinfunction "1_1") (pintype "passive"))
      (node (ref "U10") (pin "1") (pinfunction "A1_1") (pintype "bidirectional"))
    )
    (net (code "15") (name "BT_AUD_FSYNC") (class "Default")
      (node (ref "R123") (pin "1") (pinfunction "1_1") (pintype "passive"))
      (node (ref "U10") (pin "3") (pinfunction "A2_3") (pintype "bidirectional"))
    )
    (net (code "16") (name "BT_AUD_IN") (class "Default")
      (node (ref "R97") (pin "1") (pinfunction "1_1") (pintype "passive"))
      (node (ref "U10") (pin "5") (pinfunction "A4_5") (pintype "bidirectional"))
    )
    (net (code "17") (name "BT_AUD_OUT") (class "Default")
      (node (ref "R100") (pin "1") (pinfunction "1_1") (pintype "passive"))
      (node (ref "U10") (pin "4") (pinfunction "A3_4") (pintype "bidirectional"))
    )
    (net (code "18") (name "BT_EN") (class "Default")
      (node (ref "SIP") (pin "K17") (pinfunction "K17_K17") (pintype "bidirectional"))
      (node (ref "U9") (pin "18") (pinfunction "B2_18") (pintype "bidirectional"))
    )
    (net (code "19") (name "BT_EN_1V8") (class "Default")
      (node (ref "R88") (pin "1") (pinfunction "1_1") (pintype "passive"))
      (node (ref "U7") (pin "41") (pinfunction "BT_EN_41") (pintype "bidirectional"))
      (node (ref "U9") (pin "3") (pinfunction "A2_3") (pintype "bidirectional"))
    )
    (net (code "20") (name "BT_HCI_CTS") (class "Default")
      (node (ref "R86") (pin "1") (pinfunction "1_1") (pintype "passive"))
      (node (ref "U10") (pin "8") (pinfunction "A7_8") (pintype "bidirectional"))
    )
    (net (code "21") (name "BT_HCI_RTS") (class "Default")
      (node (ref "R85") (pin "1") (pinfunction "1_1") (pintype "passive"))
      (node (ref "U10") (pin "9") (pinfunction "A8_9") (pintype "bidirectional"))
    )
    (net (code "22") (name "BT_HCI_RX") (class "Default")
      (node (ref "R96") (pin "1") (pinfunction "1_1") (pintype "passive"))
      (node (ref "U10") (pin "6") (pinfunction "A5_6") (pintype "bidirectional"))
    )
    (net (code "23") (name "BT_HCI_TX") (class "Default")
      (node (ref "R92") (pin "1") (pinfunction "1_1") (pintype "passive"))
      (node (ref "U10") (pin "7") (pinfunction "A6_7") (pintype "bidirectional"))
    )
    (net (code "24") (name "CANH") (class "Default")
      (node (ref "CAN") (pin "3") (pinfunction "3_3") (pintype "bidirectional"))
      (node (ref "R104") (pin "1") (pinfunction "1_1") (pintype "passive"))
      (node (ref "U1") (pin "7") (pinfunction "CANH_7") (pintype "bidirectional"))
    )
    (net (code "25") (name "CANL") (class "Default")
      (node (ref "CAN") (pin "4") (pinfunction "4_4") (pintype "bidirectional"))
      (node (ref "R104") (pin "2") (pinfunction "2_2") (pintype "passive"))
      (node (ref "U1") (pin "6") (pinfunction "CANL_6") (pintype "bidirectional"))
    )
    (net (code "26") (name "CGND") (class "Default")
      (node (ref "MGT1") (pin "P$1") (pinfunction "P$1_P$1") (pintype "bidirectional"))
      (node (ref "MGT2") (pin "P$1") (pinfunction "P$1_P$1") (pintype "bidirectional"))
      (node (ref "MGT3") (pin "P$1") (pinfunction "P$1_P$1") (pintype "bidirectional"))
      (node (ref "MGT4") (pin "P$1") (pinfunction "P$1_P$1") (pintype "bidirectional"))
      (node (ref "R107") (pin "2") (pinfunction "2_2") (pintype "passive"))
      (node (ref "X2") (pin "CGND1") (pinfunction "CGND1_CGND1") (pintype "bidirectional"))
      (node (ref "X2") (pin "CGND2") (pinfunction "CGND2_CGND2") (pintype "bidirectional"))
      (node (ref "X2") (pin "CGND3") (pinfunction "CGND3_CGND3") (pintype "bidirectional"))
      (node (ref "X2") (pin "CGND4") (pinfunction "CGND4_CGND4") (pintype "bidirectional"))
      (node (ref "X2") (pin "CGND5") (pinfunction "CGND5_CGND5") (pintype "bidirectional"))
      (node (ref "X2") (pin "CGND6") (pinfunction "CGND6_CGND6") (pintype "bidirectional"))
      (node (ref "X3") (pin "5") (pinfunction "CG1_5") (pintype "bidirectional"))
      (node (ref "X3") (pin "6") (pinfunction "CG2_6") (pintype "bidirectional"))
      (node (ref "X4") (pin "CGND1") (pinfunction "SGND1_CGND1") (pintype "bidirectional"))
      (node (ref "X4") (pin "CGND2") (pinfunction "SGND2_CGND2") (pintype "bidirectional"))
      (node (ref "X4") (pin "CGND3") (pinfunction "SGND3_CGND3") (pintype "bidirectional"))
      (node (ref "X4") (pin "CGND4") (pinfunction "SGND4_CGND4") (pintype "bidirectional"))
      (node (ref "X4") (pin "CGND5") (pinfunction "SGND5_CGND5") (pintype "bidirectional"))
      (node (ref "X4") (pin "CGND6") (pinfunction "SGND6_CGND6") (pintype "bidirectional"))
    )
    (net (code "27") (name "CHG_EN") (class "Default")
      (node (ref "CHGIC") (pin "6") (pinfunction "EN_6") (pintype "bidirectional"))
      (node (ref "R7") (pin "2") (pinfunction "2_2") (pintype "passive"))
      (node (ref "R8") (pin "1") (pinfunction "1_1") (pintype "passive"))
    )
    (net (code "28") (name "DCAN1_RX") (class "Default")
      (node (ref "SIP") (pin "E17") (pinfunction "UART0_RTSN_E17_E17") (pintype "bidirectional"))
      (node (ref "U1") (pin "4") (pinfunction "RXD_4") (pintype "output"))
    )
    (net (code "29") (name "DCAN1_SILENT") (class "Default")
      (node (ref "SIP") (pin "M16") (pinfunction "M16_M16") (pintype "bidirectional"))
      (node (ref "U1") (pin "8") (pinfunction "S_8") (pintype "input"))
    )
    (net (code "30") (name "DCAN1_TX") (class "Default")
      (node (ref "SIP") (pin "E18") (pinfunction "UART0_CTSN_E18_E18") (pintype "bidirectional"))
      (node (ref "U1") (pin "1") (pinfunction "TXD_1") (pintype "input"))
    )
    (net (code "31") (name "DO") (class "Default")
      (node (ref "PROT") (pin "1") (pinfunction "DO_1") (pintype "bidirectional"))
      (node (ref "Q1") (pin "4") (pinfunction "G_4") (pintype "passive"))
    )
    (net (code "32") (name "EMMC_RST") (class "Default")
      (node (ref "R94") (pin "1") (pinfunction "1_1") (pintype "passive"))
      (node (ref "SIP") (pin "R14") (pinfunction "EMMCRST_GPIO1_20_R14_R14") (pintype "bidirectional"))
      (node (ref "U13") (pin "K5") (pinfunction "RST#_K5") (pintype "bidirectional"))
    )
    (net (code "33") (name "EQEP_0A") (class "Default")
      (node (ref "E1") (pin "3") (pinfunction "3_3") (pintype "bidirectional"))
      (node (ref "SIP") (pin "B12") (pinfunction "GPIO3_18_B12_B12") (pintype "bidirectional"))
    )
    (net (code "34") (name "EQEP_0B") (class "Default")
      (node (ref "E1") (pin "4") (pinfunction "4_4") (pintype "bidirectional"))
      (node (ref "SIP") (pin "C13") (pinfunction "GPIO3_19_C13_C13") (pintype "bidirectional"))
    )
    (net (code "35") (name "EQEP_1A") (class "Default")
      (node (ref "E2") (pin "3") (pinfunction "3_3") (pintype "bidirectional"))
      (node (ref "R16") (pin "2") (pinfunction "2_2") (pintype "passive"))
      (node (ref "SIP") (pin "V2") (pinfunction "LCD_DATA12_V2_V2") (pintype "bidirectional"))
    )
    (net (code "36") (name "EQEP_1B") (class "Default")
      (node (ref "E2") (pin "4") (pinfunction "4_4") (pintype "bidirectional"))
      (node (ref "R17") (pin "2") (pinfunction "2_2") (pintype "passive"))
      (node (ref "SIP") (pin "V3") (pinfunction "LCD_DATA13_V3_V3") (pintype "bidirectional"))
    )
    (net (code "37") (name "EQEP_2A") (class "Default")
      (node (ref "E3") (pin "3") (pinfunction "3_3") (pintype "bidirectional"))
      (node (ref "SIP") (pin "T12") (pinfunction "GPIO1_12_T12_T12") (pintype "bidirectional"))
    )
    (net (code "38") (name "EQEP_2B") (class "Default")
      (node (ref "E3") (pin "4") (pinfunction "4_4") (pintype "bidirectional"))
      (node (ref "SIP") (pin "R12") (pinfunction "GPIO1_13_R12_R12") (pintype "bidirectional"))
    )
    (net (code "39") (name "GND") (class "Default")
      (node (ref "12V") (pin "OUT") (pinfunction "OUT_OUT") (pintype "bidirectional"))
      (node (ref "5VREG") (pin "4") (pinfunction "SD_4") (pintype "input"))
      (node (ref "5VREG") (pin "5") (pinfunction "GND_5") (pintype "power_in"))
      (node (ref "5VREG") (pin "6") (pinfunction "GND1_6") (pintype "input"))
      (node (ref "5VREG") (pin "7") (pinfunction "GND2_7") (pintype "passive"))
      (node (ref "5VREG") (pin "8") (pinfunction "GND3_8") (pintype "power_in"))
      (node (ref "6VREG") (pin "3") (pinfunction "GND_3") (pintype "bidirectional"))
      (node (ref "ADC") (pin "1") (pinfunction "1_1") (pintype "bidirectional"))
      (node (ref "ANT1") (pin "GND1") (pinfunction "GND1_GND1") (pintype "bidirectional"))
      (node (ref "ANT1") (pin "GND2") (pinfunction "GND2_GND2") (pintype "bidirectional"))
      (node (ref "ANT2") (pin "GND1") (pinfunction "GND1_GND1") (pintype "bidirectional"))
      (node (ref "ANT2") (pin "GND2") (pinfunction "GND2_GND2") (pintype "bidirectional"))
      (node (ref "BMP") (pin "1") (pinfunction "GND_1") (pintype "power_in"))
      (node (ref "BMP") (pin "5") (pinfunction "SDO_5") (pintype "bidirectional"))
      (node (ref "BMP") (pin "7") (pinfunction "GND_7") (pintype "power_in"))
      (node (ref "C10") (pin "1") (pinfunction "1_1") (pintype "passive"))
      (node (ref "C11") (pin "-") (pinfunction "-_-") (pintype "passive"))
      (node (ref "C12") (pin "2") (pinfunction "2_2") (pintype "passive"))
      (node (ref "C13") (pin "2") (pinfunction "2_2") (pintype "passive"))
      (node (ref "C16") (pin "2") (pinfunction "2_2") (pintype "passive"))
      (node (ref "C2") (pin "1") (pinfunction "1_1") (pintype "passive"))
      (node (ref "C20") (pin "1") (pinfunction "1_1") (pintype "passive"))
      (node (ref "C21") (pin "1") (pinfunction "1_1") (pintype "passive"))
      (node (ref "C23") (pin "1") (pinfunction "1_1") (pintype "passive"))
      (node (ref "C24") (pin "1") (pinfunction "1_1") (pintype "passive"))
      (node (ref "C25") (pin "2") (pinfunction "2_2") (pintype "passive"))
      (node (ref "C26") (pin "2") (pinfunction "2_2") (pintype "passive"))
      (node (ref "C27") (pin "2") (pinfunction "2_2") (pintype "passive"))
      (node (ref "C28") (pin "2") (pinfunction "2_2") (pintype "passive"))
      (node (ref "C3") (pin "2") (pinfunction "2_2") (pintype "passive"))
      (node (ref "C33") (pin "2") (pinfunction "2_2") (pintype "passive"))
      (node (ref "C34") (pin "1") (pinfunction "1_1") (pintype "passive"))
      (node (ref "C35") (pin "1") (pinfunction "1_1") (pintype "passive"))
      (node (ref "C36") (pin "2") (pinfunction "2_2") (pintype "passive"))
      (node (ref "C37") (pin "2") (pinfunction "2_2") (pintype "passive"))
      (node (ref "C38") (pin "2") (pinfunction "2_2") (pintype "passive"))
      (node (ref "C39") (pin "2") (pinfunction "2_2") (pintype "passive"))
      (node (ref "C4") (pin "1") (pinfunction "1_1") (pintype "passive"))
      (node (ref "C40") (pin "2") (pinfunction "2_2") (pintype "passive"))
      (node (ref "C41") (pin "2") (pinfunction "2_2") (pintype "passive"))
      (node (ref "C45") (pin "2") (pinfunction "2_2") (pintype "passive"))
      (node (ref "C46") (pin "2") (pinfunction "2_2") (pintype "passive"))
      (node (ref "C47") (pin "2") (pinfunction "2_2") (pintype "passive"))
      (node (ref "C49") (pin "1") (pinfunction "1_1") (pintype "passive"))
      (node (ref "C5") (pin "2") (pinfunction "2_2") (pintype "passive"))
      (node (ref "C50") (pin "2") (pinfunction "2_2") (pintype "passive"))
      (node (ref "C51") (pin "1") (pinfunction "1_1") (pintype "passive"))
      (node (ref "C52") (pin "2") (pinfunction "2_2") (pintype "passive"))
      (node (ref "C53") (pin "2") (pinfunction "2_2") (pintype "passive"))
      (node (ref "C54") (pin "2") (pinfunction "2_2") (pintype "passive"))
      (node (ref "C55") (pin "2") (pinfunction "2_2") (pintype "passive"))
      (node (ref "C56") (pin "2") (pinfunction "2_2") (pintype "passive"))
      (node (ref "C57") (pin "1") (pinfunction "1_1") (pintype "passive"))
      (node (ref "C59") (pin "2") (pinfunction "2_2") (pintype "passive"))
      (node (ref "C6") (pin "2") (pinfunction "2_2") (pintype "passive"))
      (node (ref "C60") (pin "1") (pinfunction "1_1") (pintype "passive"))
      (node (ref "C61") (pin "1") (pinfunction "1_1") (pintype "passive"))
      (node (ref "C62") (pin "2") (pinfunction "2_2") (pintype "passive"))
      (node (ref "C63") (pin "2") (pinfunction "2_2") (pintype "passive"))
      (node (ref "C7") (pin "2") (pinfunction "2_2") (pintype "passive"))
      (node (ref "C8") (pin "2") (pinfunction "2_2") (pintype "passive"))
      (node (ref "C9") (pin "1") (pinfunction "1_1") (pintype "passive"))
      (node (ref "CAN") (pin "1") (pinfunction "1_1") (pintype "bidirectional"))
      (node (ref "CHGIC") (pin "16") (pinfunction "PGND_16") (pintype "bidirectional"))
      (node (ref "CHGIC") (pin "8") (pinfunction "AGND_8") (pintype "bidirectional"))
      (node (ref "D1") (pin "A") (pinfunction "A_A") (pintype "passive"))
      (node (ref "D9") (pin "A") (pinfunction "A_A") (pintype "passive"))
      (node (ref "DSM2") (pin "P$2") (pinfunction "2_P$2") (pintype "bidirectional"))
      (node (ref "E1") (pin "1") (pinfunction "1_1") (pintype "bidirectional"))
      (node (ref "E2") (pin "1") (pinfunction "1_1") (pintype "bidirectional"))
      (node (ref "E3") (pin "1") (pinfunction "1_1") (pintype "bidirectional"))
      (node (ref "E4") (pin "1") (pinfunction "1_1") (pintype "bidirectional"))
      (node (ref "GND") (pin "P$1") (pinfunction "TP_P$1") (pintype "bidirectional"))
      (node (ref "GP0") (pin "1") (pinfunction "1_1") (pintype "bidirectional"))
      (node (ref "GP1") (pin "1") (pinfunction "1_1") (pintype "bidirectional"))
      (node (ref "GPS") (pin "2") (pinfunction "2_2") (pintype "bidirectional"))
      (node (ref "GPS") (pin "6") (pinfunction "6_6") (pintype "bidirectional"))
      (node (ref "H1") (pin "10") (pinfunction "PGND2_10") (pintype "bidirectional"))
      (node (ref "H1") (pin "18") (pinfunction "GND_18") (pintype "bidirectional"))
      (node (ref "H1") (pin "3") (pinfunction "PGND1_3") (pintype "bidirectional"))
      (node (ref "H1") (pin "4") (pinfunction "PGND1_4") (pintype "bidirectional"))
      (node (ref "H1") (pin "9") (pinfunction "PGND2_9") (pintype "bidirectional"))
      (node (ref "H2") (pin "10") (pinfunction "PGND2_10") (pintype "bidirectional"))
      (node (ref "H2") (pin "18") (pinfunction "GND_18") (pintype "bidirectional"))
      (node (ref "H2") (pin "3") (pinfunction "PGND1_3") (pintype "bidirectional"))
      (node (ref "H2") (pin "4") (pinfunction "PGND1_4") (pintype "bidirectional"))
      (node (ref "H2") (pin "9") (pinfunction "PGND2_9") (pintype "bidirectional"))
      (node (ref "I2C") (pin "1") (pinfunction "1_1") (pintype "bidirectional"))
      (node (ref "IMU") (pin "18") (pinfunction "GND_18") (pintype "bidirectional"))
      (node (ref "IMU") (pin "20") (pinfunction "RESV_20") (pintype "bidirectional"))
      (node (ref "IMU") (pin "9") (pinfunction "AD0/SDO_9") (pintype "bidirectional"))
      (node (ref "J2") (pin "P$13") (pinfunction "GND_P$13") (pintype "bidirectional"))
      (node (ref "J2") (pin "P$14") (pinfunction "GND_P$14") (pintype "bidirectional"))
      (node (ref "J2") (pin "P$15") (pinfunction "GND_P$15") (pintype "bidirectional"))
      (node (ref "J2") (pin "P$16") (pinfunction "GND_P$16") (pintype "bidirectional"))
      (node (ref "J2") (pin "P$17") (pinfunction "GND_P$17") (pintype "bidirectional"))
      (node (ref "J2") (pin "P$18") (pinfunction "GND_P$18") (pintype "bidirectional"))
      (node (ref "J2") (pin "P$23") (pinfunction "GND_P$23") (pintype "bidirectional"))
      (node (ref "J2") (pin "P$24") (pinfunction "GND_P$24") (pintype "bidirectional"))
      (node (ref "L4") (pin "1") (pinfunction "1_1") (pintype "passive"))
      (node (ref "MOD") (pin "1") (pinfunction "1_1") (pintype "passive"))
      (node (ref "OSC1") (pin "2") (pinfunction "GND_2") (pintype "bidirectional"))
      (node (ref "PAU") (pin "1") (pinfunction "1_1") (pintype "passive"))
      (node (ref "POW") (pin "1") (pinfunction "1_1") (pintype "passive"))
      (node (ref "PWR") (pin "1") (pinfunction "1_1") (pintype "bidirectional"))
      (node (ref "PWR") (pin "2") (pinfunction "2_2") (pintype "bidirectional"))
      (node (ref "Q1") (pin "5") (pinfunction "D_5") (pintype "passive"))
      (node (ref "Q1") (pin "6") (pinfunction "D_6") (pintype "passive"))
      (node (ref "Q1") (pin "7") (pinfunction "D_7") (pintype "passive"))
      (node (ref "Q1") (pin "8") (pinfunction "D_8") (pintype "passive"))
      (node (ref "R106") (pin "1") (pinfunction "1_1") (pintype "passive"))
      (node (ref "R107") (pin "1") (pinfunction "1_1") (pintype "passive"))
      (node (ref "R108") (pin "2") (pinfunction "2_2") (pintype "passive"))
      (node (ref "R110") (pin "2") (pinfunction "2_2") (pintype "passive"))
      (node (ref "R113") (pin "1") (pinfunction "1_1") (pintype "passive"))
      (node (ref "R115") (pin "1") (pinfunction "1_1") (pintype "passive"))
      (node (ref "R125") (pin "1") (pinfunction "1_1") (pintype "passive"))
      (node (ref "R127") (pin "1") (pinfunction "1_1") (pintype "passive"))
      (node (ref "R129") (pin "1") (pinfunction "1_1") (pintype "passive"))
      (node (ref "R131") (pin "1") (pinfunction "1_1") (pintype "passive"))
      (node (ref "R135") (pin "1") (pinfunction "1_1") (pintype "passive"))
      (node (ref "R14") (pin "2") (pinfunction "2_2") (pintype "passive"))
      (node (ref "R143") (pin "1") (pinfunction "1_1") (pintype "passive"))
      (node (ref "R150") (pin "2") (pinfunction "2_2") (pintype "passive"))
      (node (ref "R158") (pin "2") (pinfunction "2_2") (pintype "passive"))
      (node (ref "R16") (pin "1") (pinfunction "1_1") (pintype "passive"))
      (node (ref "R17") (pin "1") (pinfunction "1_1") (pintype "passive"))
      (node (ref "R21") (pin "2") (pinfunction "2_2") (pintype "passive"))
      (node (ref "R22") (pin "2") (pinfunction "2_2") (pintype "passive"))
      (node (ref "R24") (pin "2") (pinfunction "2_2") (pintype "passive"))
      (node (ref "R25") (pin "2") (pinfunction "2_2") (pintype "passive"))
      (node (ref "R29") (pin "2") (pinfunction "2_2") (pintype "passive"))
      (node (ref "R31") (pin "2") (pinfunction "2_2") (pintype "passive"))
      (node (ref "R32") (pin "2") (pinfunction "2_2") (pintype "passive"))
      (node (ref "R33") (pin "2") (pinfunction "2_2") (pintype "passive"))
      (node (ref "R46") (pin "1") (pinfunction "1_1") (pintype "passive"))
      (node (ref "R47") (pin "1") (pinfunction "1_1") (pintype "passive"))
      (node (ref "R48") (pin "1") (pinfunction "1_1") (pintype "passive"))
      (node (ref "R50") (pin "2") (pinfunction "2_2") (pintype "passive"))
      (node (ref "R51") (pin "2") (pinfunction "2_2") (pintype "passive"))
      (node (ref "R52") (pin "2") (pinfunction "2_2") (pintype "passive"))
      (node (ref "R53") (pin "2") (pinfunction "2_2") (pintype "passive"))
      (node (ref "R59") (pin "1") (pinfunction "1_1") (pintype "passive"))
      (node (ref "R6") (pin "1") (pinfunction "1_1") (pintype "passive"))
      (node (ref "R61") (pin "1") (pinfunction "1_1") (pintype "passive"))
      (node (ref "R62") (pin "1") (pinfunction "1_1") (pintype "passive"))
      (node (ref "R63") (pin "1") (pinfunction "1_1") (pintype "passive"))
      (node (ref "R64") (pin "1") (pinfunction "1_1") (pintype "passive"))
      (node (ref "R8") (pin "2") (pinfunction "2_2") (pintype "passive"))
      (node (ref "R87") (pin "2") (pinfunction "2_2") (pintype "passive"))
      (node (ref "R88") (pin "2") (pinfunction "2_2") (pintype "passive"))
      (node (ref "R89") (pin "2") (pinfunction "2_2") (pintype "passive"))
      (node (ref "R91") (pin "2") (pinfunction "2_2") (pintype "passive"))
      (node (ref "R95") (pin "1") (pinfunction "1_1") (pintype "passive"))
      (node (ref "RST") (pin "1") (pinfunction "1_1") (pintype "passive"))
      (node (ref "S1.1") (pin "1") (pinfunction "1_1") (pintype "bidirectional"))
      (node (ref "S1.2") (pin "1") (pinfunction "1_1") (pintype "bidirectional"))
      (node (ref "SD") (pin "1") (pinfunction "1_1") (pintype "passive"))
      (node (ref "SIP") (pin "A1") (pinfunction "DGND1_A1") (pintype "bidirectional"))
      (node (ref "SIP") (pin "A18") (pinfunction "DGND2_A18") (pintype "bidirectional"))
      (node (ref "SIP") (pin "E19") (pinfunction "DGND3_E19") (pintype "bidirectional"))
      (node (ref "SIP") (pin "E20") (pinfunction "DGND4_E20") (pintype "bidirectional"))
      (node (ref "SIP") (pin "F19") (pinfunction "DGND6_F19") (pintype "bidirectional"))
      (node (ref "SIP") (pin "F8") (pinfunction "DGND5_F8") (pintype "bidirectional"))
      (node (ref "SIP") (pin "G11") (pinfunction "DGND9_G11") (pintype "bidirectional"))
      (node (ref "SIP") (pin "G12") (pinfunction "DGND10_G12") (pintype "bidirectional"))
      (node (ref "SIP") (pin "G19") (pinfunction "DGND11_G19") (pintype "bidirectional"))
      (node (ref "SIP") (pin "G8") (pinfunction "DGND7_G8") (pintype "bidirectional"))
      (node (ref "SIP") (pin "G9") (pinfunction "DGND8_G9") (pintype "bidirectional"))
      (node (ref "SIP") (pin "H10") (pinfunction "DGND16_H10") (pintype "bidirectional"))
      (node (ref "SIP") (pin "H12") (pinfunction "DGND17_H12") (pintype "bidirectional"))
      (node (ref "SIP") (pin "H19") (pinfunction "DGND18_H19") (pintype "bidirectional"))
      (node (ref "SIP") (pin "H6") (pinfunction "DGND12_H6") (pintype "bidirectional"))
      (node (ref "SIP") (pin "H7") (pinfunction "DGND13_H7") (pintype "bidirectional"))
      (node (ref "SIP") (pin "H8") (pinfunction "DGND14_H8") (pintype "bidirectional"))
      (node (ref "SIP") (pin "H9") (pinfunction "DGND15_H9") (pintype "bidirectional"))
      (node (ref "SIP") (pin "J10") (pinfunction "DGND23_J10") (pintype "bidirectional"))
      (node (ref "SIP") (pin "J11") (pinfunction "DGND24_J11") (pintype "bidirectional"))
      (node (ref "SIP") (pin "J19") (pinfunction "DGND25_J19") (pintype "bidirectional"))
      (node (ref "SIP") (pin "J20") (pinfunction "DGND26_J20") (pintype "bidirectional"))
      (node (ref "SIP") (pin "J6") (pinfunction "DGND19_J6") (pintype "bidirectional"))
      (node (ref "SIP") (pin "J7") (pinfunction "DGND20_J7") (pintype "bidirectional"))
      (node (ref "SIP") (pin "J8") (pinfunction "DGND21_J8") (pintype "bidirectional"))
      (node (ref "SIP") (pin "J9") (pinfunction "DGND22_J9") (pintype "bidirectional"))
      (node (ref "SIP") (pin "K10") (pinfunction "DGND29_K10") (pintype "bidirectional"))
      (node (ref "SIP") (pin "K11") (pinfunction "DGND30_K11") (pintype "bidirectional"))
      (node (ref "SIP") (pin "K19") (pinfunction "DGND31_K19") (pintype "bidirectional"))
      (node (ref "SIP") (pin "K7") (pinfunction "DGND27_K7") (pintype "bidirectional"))
      (node (ref "SIP") (pin "K9") (pinfunction "DGND28_K9") (pintype "bidirectional"))
      (node (ref "SIP") (pin "L10") (pinfunction "DGND32_L10") (pintype "bidirectional"))
      (node (ref "SIP") (pin "L11") (pinfunction "DGND33_L11") (pintype "bidirectional"))
      (node (ref "SIP") (pin "L12") (pinfunction "DGND34_L12") (pintype "bidirectional"))
      (node (ref "SIP") (pin "L13") (pinfunction "DGND35_L13") (pintype "bidirectional"))
      (node (ref "SIP") (pin "L19") (pinfunction "DGND36_L19") (pintype "bidirectional"))
      (node (ref "SIP") (pin "M10") (pinfunction "DGND42_M10") (pintype "bidirectional"))
      (node (ref "SIP") (pin "M12") (pinfunction "DGND43_M12") (pintype "bidirectional"))
      (node (ref "SIP") (pin "M14") (pinfunction "DGND44_M14") (pintype "bidirectional"))
      (node (ref "SIP") (pin "M19") (pinfunction "DGND45_M19") (pintype "bidirectional"))
      (node (ref "SIP") (pin "M6") (pinfunction "DGND38_M6") (pintype "bidirectional"))
      (node (ref "SIP") (pin "M7") (pinfunction "DGND39_M7") (pintype "bidirectional"))
      (node (ref "SIP") (pin "M8") (pinfunction "DGND40_M8") (pintype "bidirectional"))
      (node (ref "SIP") (pin "M9") (pinfunction "DGND41_M9") (pintype "bidirectional"))
      (node (ref "SIP") (pin "N10") (pinfunction "DGND47_N10") (pintype "bidirectional"))
      (node (ref "SIP") (pin "N11") (pinfunction "DGND48_N11") (pintype "bidirectional"))
      (node (ref "SIP") (pin "N14") (pinfunction "DGND49_N14") (pintype "bidirectional"))
      (node (ref "SIP") (pin "N19") (pinfunction "DGND50_N19") (pintype "bidirectional"))
      (node (ref "SIP") (pin "N20") (pinfunction "DGND51_N20") (pintype "bidirectional"))
      (node (ref "SIP") (pin "N7") (pinfunction "DGND46_N7") (pintype "bidirectional"))
      (node (ref "SIP") (pin "P19") (pinfunction "DGND52_P19") (pintype "bidirectional"))
      (node (ref "SIP") (pin "P20") (pinfunction "DGND53_P20") (pintype "bidirectional"))
      (node (ref "SIP") (pin "R19") (pinfunction "DGND54_R19") (pintype "bidirectional"))
      (node (ref "SIP") (pin "R20") (pinfunction "DGND55_R20") (pintype "bidirectional"))
      (node (ref "SIP") (pin "T19") (pinfunction "DGND56_T19") (pintype "bidirectional"))
      (node (ref "SIP") (pin "T20") (pinfunction "DGND57_T20") (pintype "bidirectional"))
      (node (ref "SIP") (pin "U19") (pinfunction "DGND58_U19") (pintype "bidirectional"))
      (node (ref "SIP") (pin "V1") (pinfunction "DGND59_V1") (pintype "bidirectional"))
      (node (ref "SIP") (pin "V18") (pinfunction "DGND60_V18") (pintype "bidirectional"))
      (node (ref "SIP") (pin "V19") (pinfunction "DGND61_V19") (pintype "bidirectional"))
      (node (ref "SIP") (pin "W10") (pinfunction "DGND70_W10") (pintype "bidirectional"))
      (node (ref "SIP") (pin "W11") (pinfunction "DGND71_W11") (pintype "bidirectional"))
      (node (ref "SIP") (pin "W12") (pinfunction "DGND72_W12") (pintype "bidirectional"))
      (node (ref "SIP") (pin "W13") (pinfunction "DGND73_W13") (pintype "bidirectional"))
      (node (ref "SIP") (pin "W14") (pinfunction "DGND74_W14") (pintype "bidirectional"))
      (node (ref "SIP") (pin "W15") (pinfunction "DGND75_W15") (pintype "bidirectional"))
      (node (ref "SIP") (pin "W16") (pinfunction "DGND76_W16") (pintype "bidirectional"))
      (node (ref "SIP") (pin "W17") (pinfunction "DGND77_W17") (pintype "bidirectional"))
      (node (ref "SIP") (pin "W18") (pinfunction "DGND78_W18") (pintype "bidirectional"))
      (node (ref "SIP") (pin "W19") (pinfunction "DGND79_W19") (pintype "bidirectional"))
      (node (ref "SIP") (pin "W2") (pinfunction "DGND62_W2") (pintype "bidirectional"))
      (node (ref "SIP") (pin "W20") (pinfunction "DGND80_W20") (pintype "bidirectional"))
      (node (ref "SIP") (pin "W3") (pinfunction "DGND63_W3") (pintype "bidirectional"))
      (node (ref "SIP") (pin "W5") (pinfunction "DGND65_W5") (pintype "bidirectional"))
      (node (ref "SIP") (pin "W6") (pinfunction "DGND66_W6") (pintype "bidirectional"))
      (node (ref "SIP") (pin "W7") (pinfunction "DGND67_W7") (pintype "bidirectional"))
      (node (ref "SIP") (pin "W8") (pinfunction "DGND68_W8") (pintype "bidirectional"))
      (node (ref "SIP") (pin "W9") (pinfunction "DGND69_W9") (pintype "bidirectional"))
      (node (ref "SIP") (pin "Y10") (pinfunction "DGND83_Y10") (pintype "bidirectional"))
      (node (ref "SIP") (pin "Y12") (pinfunction "DGND84_Y12") (pintype "bidirectional"))
      (node (ref "SIP") (pin "Y15") (pinfunction "DGND85_Y15") (pintype "bidirectional"))
      (node (ref "SIP") (pin "Y18") (pinfunction "DGND86_Y18") (pintype "bidirectional"))
      (node (ref "SIP") (pin "Y7") (pinfunction "DGND82_Y7") (pintype "bidirectional"))
      (node (ref "TP12") (pin "TP") (pinfunction "TP_TP") (pintype "input"))
      (node (ref "U1") (pin "2") (pinfunction "GND_2") (pintype "power_in"))
      (node (ref "U10") (pin "11") (pinfunction "GND_11") (pintype "bidirectional"))
      (node (ref "U10") (pin "TP") (pinfunction "TP_TP") (pintype "bidirectional"))
      (node (ref "U13") (pin "C4") (pinfunction "VSSQ1_C4") (pintype "bidirectional"))
      (node (ref "U13") (pin "E7") (pinfunction "VSS1_E7") (pintype "bidirectional"))
      (node (ref "U13") (pin "G5") (pinfunction "VSS2_G5") (pintype "bidirectional"))
      (node (ref "U13") (pin "H10") (pinfunction "VSS3_H10") (pintype "bidirectional"))
      (node (ref "U13") (pin "K8") (pinfunction "VSS4_K8") (pintype "bidirectional"))
      (node (ref "U13") (pin "N2") (pinfunction "VSSQ2_N2") (pintype "bidirectional"))
      (node (ref "U13") (pin "N5") (pinfunction "VSSQ3_N5") (pintype "bidirectional"))
      (node (ref "U13") (pin "P4") (pinfunction "VSSQ4_P4") (pintype "bidirectional"))
      (node (ref "U13") (pin "P6") (pinfunction "VSSQ5_P6") (pintype "bidirectional"))
      (node (ref "U2") (pin "3") (pinfunction "GND_3") (pintype "power_in"))
      (node (ref "U3") (pin "4") (pinfunction "GND_4") (pintype "bidirectional"))
      (node (ref "U4") (pin "4") (pinfunction "GND_4") (pintype "bidirectional"))
      (node (ref "U5") (pin "2") (pinfunction "VSS_2") (pintype "passive"))
      (node (ref "U6") (pin "3") (pinfunction "GND_3") (pintype "power_in"))
      (node (ref "U7") (pin "1") (pinfunction "GND1_1") (pintype "bidirectional"))
      (node (ref "U7") (pin "15") (pinfunction "GND4_15") (pintype "bidirectional"))
      (node (ref "U7") (pin "16") (pinfunction "GND5_16") (pintype "bidirectional"))
      (node (ref "U7") (pin "17") (pinfunction "GND6_17") (pintype "bidirectional"))
      (node (ref "U7") (pin "19") (pinfunction "GND7_19") (pintype "bidirectional"))
      (node (ref "U7") (pin "20") (pinfunction "GND8_20") (pintype "bidirectional"))
      (node (ref "U7") (pin "23") (pinfunction "GND9_23") (pintype "bidirectional"))
      (node (ref "U7") (pin "24") (pinfunction "GND10_24") (pintype "bidirectional"))
      (node (ref "U7") (pin "28") (pinfunction "GND11_28") (pintype "bidirectional"))
      (node (ref "U7") (pin "29") (pinfunction "GND12_29") (pintype "bidirectional"))
      (node (ref "U7") (pin "30") (pinfunction "GND13_30") (pintype "bidirectional"))
      (node (ref "U7") (pin "31") (pinfunction "GND14_31") (pintype "bidirectional"))
      (node (ref "U7") (pin "33") (pinfunction "GND15_33") (pintype "bidirectional"))
      (node (ref "U7") (pin "34") (pinfunction "GND16_34") (pintype "bidirectional"))
      (node (ref "U7") (pin "35") (pinfunction "GND17_35") (pintype "bidirectional"))
      (node (ref "U7") (pin "37") (pinfunction "GND18_37") (pintype "bidirectional"))
      (node (ref "U7") (pin "39") (pinfunction "GND19_39") (pintype "bidirectional"))
      (node (ref "U7") (pin "44") (pinfunction "GND20_44") (pintype "bidirectional"))
      (node (ref "U7") (pin "45") (pinfunction "GND21_45") (pintype "bidirectional"))
      (node (ref "U7") (pin "48") (pinfunction "GND22_48") (pintype "bidirectional"))
      (node (ref "U7") (pin "49") (pinfunction "GND23_49") (pintype "bidirectional"))
      (node (ref "U7") (pin "54") (pinfunction "GND24_54") (pintype "bidirectional"))
      (node (ref "U7") (pin "55") (pinfunction "GND25_55") (pintype "bidirectional"))
      (node (ref "U7") (pin "59") (pinfunction "GND26_59") (pintype "bidirectional"))
      (node (ref "U7") (pin "61") (pinfunction "GND27_61") (pintype "bidirectional"))
      (node (ref "U7") (pin "63") (pinfunction "GND28_63") (pintype "bidirectional"))
      (node (ref "U7") (pin "64") (pinfunction "GND29_64") (pintype "bidirectional"))
      (node (ref "U7") (pin "7") (pinfunction "GND2_7") (pintype "bidirectional"))
      (node (ref "U7") (pin "9") (pinfunction "GND3_9") (pintype "bidirectional"))
      (node (ref "U7") (pin "G1") (pinfunction "G1_G1") (pintype "bidirectional"))
      (node (ref "U7") (pin "G10") (pinfunction "G10_G10") (pintype "bidirectional"))
      (node (ref "U7") (pin "G11") (pinfunction "G11_G11") (pintype "bidirectional"))
      (node (ref "U7") (pin "G12") (pinfunction "G12_G12") (pintype "bidirectional"))
      (node (ref "U7") (pin "G13") (pinfunction "G13_G13") (pintype "bidirectional"))
      (node (ref "U7") (pin "G14") (pinfunction "G14_G14") (pintype "bidirectional"))
      (node (ref "U7") (pin "G15") (pinfunction "G15_G15") (pintype "bidirectional"))
      (node (ref "U7") (pin "G16") (pinfunction "G16_G16") (pintype "bidirectional"))
      (node (ref "U7") (pin "G17") (pinfunction "G17_G17") (pintype "bidirectional"))
      (node (ref "U7") (pin "G18") (pinfunction "G18_G18") (pintype "bidirectional"))
      (node (ref "U7") (pin "G19") (pinfunction "G19_G19") (pintype "bidirectional"))
      (node (ref "U7") (pin "G2") (pinfunction "G2_G2") (pintype "bidirectional"))
      (node (ref "U7") (pin "G20") (pinfunction "G20_G20") (pintype "bidirectional"))
      (node (ref "U7") (pin "G21") (pinfunction "G21_G21") (pintype "bidirectional"))
      (node (ref "U7") (pin "G22") (pinfunction "G22_G22") (pintype "bidirectional"))
      (node (ref "U7") (pin "G23") (pinfunction "G23_G23") (pintype "bidirectional"))
      (node (ref "U7") (pin "G24") (pinfunction "G24_G24") (pintype "bidirectional"))
      (node (ref "U7") (pin "G25") (pinfunction "G25_G25") (pintype "bidirectional"))
      (node (ref "U7") (pin "G26") (pinfunction "G26_G26") (pintype "bidirectional"))
      (node (ref "U7") (pin "G27") (pinfunction "G27_G27") (pintype "bidirectional"))
      (node (ref "U7") (pin "G28") (pinfunction "G28_G28") (pintype "bidirectional"))
      (node (ref "U7") (pin "G29") (pinfunction "G29_G29") (pintype "bidirectional"))
      (node (ref "U7") (pin "G3") (pinfunction "G3_G3") (pintype "bidirectional"))
      (node (ref "U7") (pin "G30") (pinfunction "G30_G30") (pintype "bidirectional"))
      (node (ref "U7") (pin "G31") (pinfunction "G31_G31") (pintype "bidirectional"))
      (node (ref "U7") (pin "G32") (pinfunction "G32_G32") (pintype "bidirectional"))
      (node (ref "U7") (pin "G33") (pinfunction "G33_G33") (pintype "bidirectional"))
      (node (ref "U7") (pin "G34") (pinfunction "G34_G34") (pintype "bidirectional"))
      (node (ref "U7") (pin "G35") (pinfunction "G35_G35") (pintype "bidirectional"))
      (node (ref "U7") (pin "G36") (pinfunction "G36_G36") (pintype "bidirectional"))
      (node (ref "U7") (pin "G4") (pinfunction "G4_G4") (pintype "bidirectional"))
      (node (ref "U7") (pin "G5") (pinfunction "G5_G5") (pintype "bidirectional"))
      (node (ref "U7") (pin "G6") (pinfunction "G6_G6") (pintype "bidirectional"))
      (node (ref "U7") (pin "G7") (pinfunction "G7_G7") (pintype "bidirectional"))
      (node (ref "U7") (pin "G8") (pinfunction "G8_G8") (pintype "bidirectional"))
      (node (ref "U7") (pin "G9") (pinfunction "G9_G9") (pintype "bidirectional"))
      (node (ref "U8") (pin "2") (pinfunction "GND_2") (pintype "power_in"))
      (node (ref "U9") (pin "11") (pinfunction "GND_11") (pintype "bidirectional"))
      (node (ref "U9") (pin "TP") (pinfunction "TP_TP") (pintype "bidirectional"))
      (node (ref "UT0") (pin "1") (pinfunction "1_1") (pintype "bidirectional"))
      (node (ref "UT1") (pin "1") (pinfunction "1_1") (pintype "bidirectional"))
      (node (ref "UT5") (pin "1") (pinfunction "1_1") (pintype "bidirectional"))
      (node (ref "X2") (pin "6") (pinfunction "VSS_6") (pintype "bidirectional"))
      (node (ref "X2") (pin "GND") (pinfunction "GND_GND") (pintype "bidirectional"))
      (node (ref "X4") (pin "GND") (pinfunction "GND_GND") (pintype "input"))
    )
    (net (code "40") (name "GNDA_ADC") (class "Default")
      (node (ref "C42") (pin "2") (pinfunction "2_2") (pintype "passive"))
      (node (ref "C43") (pin "2") (pinfunction "2_2") (pintype "passive"))
      (node (ref "C44") (pin "2") (pinfunction "2_2") (pintype "passive"))
      (node (ref "SIP") (pin "A6") (pinfunction "VSSA_ADC_0_A6") (pintype "bidirectional"))
      (node (ref "SIP") (pin "A9") (pinfunction "VSSA_ADC_1_A9") (pintype "bidirectional"))
      (node (ref "SIP") (pin "E8") (pinfunction "VSSA_ADC_2_E8") (pintype "bidirectional"))
    )
    (net (code "41") (name "GPIO1_17") (class "Default")
      (node (ref "GP0") (pin "4") (pinfunction "4_4") (pintype "bidirectional"))
      (node (ref "SIP") (pin "V14") (pinfunction "GPIO1_17_V14_V14") (pintype "bidirectional"))
    )
    (net (code "42") (name "GPIO1_25") (class "Default")
      (node (ref "GP0") (pin "3") (pinfunction "3_3") (pintype "bidirectional"))
      (node (ref "SIP") (pin "U16") (pinfunction "HDMIINT_GPIO1_25_U16_U16") (pintype "bidirectional"))
    )
    (net (code "43") (name "GPIO3_1") (class "Default")
      (node (ref "GP1") (pin "4") (pinfunction "4_4") (pintype "bidirectional"))
      (node (ref "SIP") (pin "H17") (pinfunction "H17_H17") (pintype "bidirectional"))
    )
    (net (code "44") (name "GPIO3_2") (class "Default")
      (node (ref "GP1") (pin "3") (pinfunction "3_3") (pintype "bidirectional"))
      (node (ref "SIP") (pin "J15") (pinfunction "J15_J15") (pintype "bidirectional"))
    )
    (net (code "45") (name "GPIO3_17") (class "Default")
      (node (ref "GP0") (pin "6") (pinfunction "6_6") (pintype "bidirectional"))
      (node (ref "SIP") (pin "C12") (pinfunction "SPI1_CS0_C12_C12") (pintype "bidirectional"))
    )
    (net (code "46") (name "GPIO3_20") (class "Default")
      (node (ref "GP0") (pin "5") (pinfunction "5_5") (pintype "bidirectional"))
      (node (ref "SIP") (pin "D13") (pinfunction "GPIO3_20_D13_D13") (pintype "bidirectional"))
    )
    (net (code "47") (name "I2C0_SCL") (class "Default")
      (node (ref "R23") (pin "1") (pinfunction "1_1") (pintype "passive"))
      (node (ref "SIP") (pin "C16") (pinfunction "I2C0_SCL_C16") (pintype "bidirectional"))
      (node (ref "SIP") (pin "C20") (pinfunction "PMIC_I2C_SCL_C20") (pintype "bidirectional"))
      (node (ref "U5") (pin "1") (pinfunction "SCL_1") (pintype "input"))
    )
    (net (code "48") (name "I2C0_SDA") (class "Default")
      (node (ref "R2") (pin "1") (pinfunction "1_1") (pintype "passive"))
      (node (ref "SIP") (pin "C17") (pinfunction "I2C0_SDA_C17") (pintype "bidirectional"))
      (node (ref "SIP") (pin "C19") (pinfunction "PMIC_I2C_SDA_C19") (pintype "bidirectional"))
      (node (ref "U5") (pin "3") (pinfunction "SDA_3") (pintype "bidirectional"))
    )
    (net (code "49") (name "I2C1_SCL") (class "Default")
      (node (ref "I2C") (pin "3") (pinfunction "3_3") (pintype "bidirectional"))
      (node (ref "R12") (pin "1") (pinfunction "1_1") (pintype "passive"))
      (node (ref "SIP") (pin "A16") (pinfunction "I2C1_SCL_A16_A16") (pintype "bidirectional"))
    )
    (net (code "50") (name "I2C1_SDA") (class "Default")
      (node (ref "I2C") (pin "4") (pinfunction "4_4") (pintype "bidirectional"))
      (node (ref "R13") (pin "2") (pinfunction "2_2") (pintype "passive"))
      (node (ref "SIP") (pin "B16") (pinfunction "I2C1_SDA_B16_B16") (pintype "bidirectional"))
    )
    (net (code "51") (name "I2C2_SCL") (class "Default")
      (node (ref "BMP") (pin "4") (pinfunction "SCK_4") (pintype "input"))
      (node (ref "IMU") (pin "23") (pinfunction "SCL/SCLK_23") (pintype "bidirectional"))
      (node (ref "R11") (pin "1") (pinfunction "1_1") (pintype "passive"))
      (node (ref "SIP") (pin "D17") (pinfunction "I2C2_SCL_D17_D17") (pintype "bidirectional"))
    )
    (net (code "52") (name "I2C2_SDA") (class "Default")
      (node (ref "BMP") (pin "3") (pinfunction "SDI_3") (pintype "bidirectional"))
      (node (ref "IMU") (pin "24") (pinfunction "SDA/SDI_24") (pintype "bidirectional"))
      (node (ref "R10") (pin "2") (pinfunction "2_2") (pintype "passive"))
      (node (ref "SIP") (pin "D18") (pinfunction "I2C2_SDA_D18_D18") (pintype "bidirectional"))
    )
    (net (code "53") (name "IMU_INT") (class "Default")
      (node (ref "IMU") (pin "12") (pinfunction "INT_12") (pintype "bidirectional"))
      (node (ref "SIP") (pin "A14") (pinfunction "GPIO3_21_A14_A14") (pintype "bidirectional"))
    )
    (net (code "54") (name "LDO_PGOOD") (class "Default")
      (node (ref "SIP") (pin "B20") (pinfunction "PMIC_OUT_LDO_PGOOD_B20") (pintype "output"))
      (node (ref "SIP") (pin "B5") (pinfunction "RTC_PWRONRSTN_B5") (pintype "bidirectional"))
    )
    (net (code "55") (name "LED_GRN") (class "Default")
      (node (ref "G") (pin "A") (pinfunction "A_A") (pintype "passive"))
      (node (ref "GP1") (pin "6") (pinfunction "6_6") (pintype "bidirectional"))
      (node (ref "SIP") (pin "T7") (pinfunction "TIMER7_T7_T7") (pintype "bidirectional"))
    )
    (net (code "56") (name "LED_RED") (class "Default")
      (node (ref "GP1") (pin "5") (pinfunction "5_5") (pintype "bidirectional"))
      (node (ref "R") (pin "A") (pinfunction "A_A") (pintype "passive"))
      (node (ref "SIP") (pin "R7") (pinfunction "TIMER4_R7_R7") (pintype "bidirectional"))
    )
    (net (code "57") (name "MCASP0_ACLKR") (class "Default")
      (node (ref "SIP") (pin "U18") (pinfunction "GPIO1_28_U18_U18") (pintype "bidirectional"))
      (node (ref "U10") (pin "20") (pinfunction "B1_20") (pintype "bidirectional"))
    )
    (net (code "58") (name "MCASP0_AXR0") (class "Default")
      (node (ref "SIP") (pin "T16") (pinfunction "USB1OC_GPIO1_26_T16_T16") (pintype "bidirectional"))
      (node (ref "U10") (pin "17") (pinfunction "B3_17") (pintype "bidirectional"))
    )
    (net (code "59") (name "MCASP0_AXR1") (class "Default")
      (node (ref "SIP") (pin "V17") (pinfunction "HDMIDIS_GPIO1_27_V17_V17") (pintype "bidirectional"))
      (node (ref "U10") (pin "16") (pinfunction "B4_16") (pintype "bidirectional"))
    )
    (net (code "60") (name "MCASP0_FSR") (class "Default")
      (node (ref "SIP") (pin "V12") (pinfunction "GPIO2_1_V12_V12") (pintype "bidirectional"))
      (node (ref "U10") (pin "18") (pinfunction "B2_18") (pintype "bidirectional"))
    )
    (net (code "61") (name "MDIR_1A") (class "Default")
      (node (ref "H1") (pin "21") (pinfunction "AIN1_21") (pintype "bidirectional"))
      (node (ref "SIP") (pin "T13") (pinfunction "GPIO2_0_T13_T13") (pintype "bidirectional"))
    )
    (net (code "62") (name "MDIR_1B") (class "Default")
      (node (ref "H1") (pin "22") (pinfunction "AIN2_22") (pintype "bidirectional"))
      (node (ref "SIP") (pin "U17") (pinfunction "UART4_TXD_U17_U17") (pintype "bidirectional"))
    )
    (net (code "63") (name "MDIR_2A") (class "Default")
      (node (ref "H1") (pin "17") (pinfunction "BIN1_17") (pintype "bidirectional"))
      (node (ref "SIP") (pin "R13") (pinfunction "GPIO1_16_R13_R13") (pintype "bidirectional"))
    )
    (net (code "64") (name "MDIR_2B") (class "Default")
      (node (ref "H1") (pin "16") (pinfunction "BIN2_16") (pintype "bidirectional"))
      (node (ref "R140") (pin "1") (pinfunction "1_1") (pintype "passive"))
      (node (ref "SIP") (pin "V4") (pinfunction "LCD_DATA14_V4_V4") (pintype "bidirectional"))
    )
    (net (code "65") (name "MDIR_3A") (class "Default")
      (node (ref "H2") (pin "21") (pinfunction "AIN1_21") (pintype "bidirectional"))
      (node (ref "R118") (pin "1") (pinfunction "1_1") (pintype "passive"))
      (node (ref "SIP") (pin "R4") (pinfunction "LCD_DATA3_R4_R4") (pintype "bidirectional"))
    )
    (net (code "66") (name "MDIR_3B") (class "Default")
      (node (ref "H2") (pin "22") (pinfunction "AIN2_22") (pintype "bidirectional"))
      (node (ref "R116") (pin "1") (pinfunction "1_1") (pintype "passive"))
      (node (ref "R77") (pin "1") (pinfunction "1_1") (pintype "passive"))
      (node (ref "SIP") (pin "R3") (pinfunction "LCD_DATA2_R3_R3") (pintype "bidirectional"))
    )
    (net (code "67") (name "MDIR_4A") (class "Default")
      (node (ref "H2") (pin "17") (pinfunction "BIN1_17") (pintype "bidirectional"))
      (node (ref "R113") (pin "2") (pinfunction "2_2") (pintype "passive"))
      (node (ref "SIP") (pin "R1") (pinfunction "LCD_DATA0_R1_R1") (pintype "bidirectional"))
    )
    (net (code "68") (name "MDIR_4B") (class "Default")
      (node (ref "H2") (pin "16") (pinfunction "BIN2_16") (pintype "bidirectional"))
      (node (ref "R115") (pin "2") (pinfunction "2_2") (pintype "passive"))
      (node (ref "SIP") (pin "R2") (pinfunction "LCD_DATA1_R2_R2") (pintype "bidirectional"))
    )
    (net (code "69") (name "MMC1_CLK") (class "Default")
      (node (ref "R15") (pin "2") (pinfunction "2_2") (pintype "passive"))
      (node (ref "R66") (pin "1") (pinfunction "1_1") (pintype "passive"))
      (node (ref "U13") (pin "M6") (pinfunction "CLK_M6") (pintype "bidirectional"))
    )
    (net (code "70") (name "MMC1_CMD") (class "Default")
      (node (ref "R67") (pin "1") (pinfunction "1_1") (pintype "passive"))
      (node (ref "SIP") (pin "V9") (pinfunction "MMC1_CMD_V9_V9") (pintype "bidirectional"))
      (node (ref "U13") (pin "M5") (pinfunction "CMD_M5") (pintype "bidirectional"))
    )
    (net (code "71") (name "MMC1_DAT0") (class "Default")
      (node (ref "R68") (pin "1") (pinfunction "1_1") (pintype "passive"))
      (node (ref "SIP") (pin "U7") (pinfunction "MMC1_DAT0_U7_U7") (pintype "bidirectional"))
      (node (ref "U13") (pin "A3") (pinfunction "DAT0_A3") (pintype "bidirectional"))
    )
    (net (code "72") (name "MMC1_DAT1") (class "Default")
      (node (ref "R69") (pin "1") (pinfunction "1_1") (pintype "passive"))
      (node (ref "SIP") (pin "V7") (pinfunction "MMC1_DAT1_V7_V7") (pintype "bidirectional"))
      (node (ref "U13") (pin "A4") (pinfunction "DAT1_A4") (pintype "bidirectional"))
    )
    (net (code "73") (name "MMC1_DAT2") (class "Default")
      (node (ref "R70") (pin "1") (pinfunction "1_1") (pintype "passive"))
      (node (ref "SIP") (pin "R8") (pinfunction "MMC1_DAT2_R8_R8") (pintype "bidirectional"))
      (node (ref "U13") (pin "A5") (pinfunction "DAT2_A5") (pintype "bidirectional"))
    )
    (net (code "74") (name "MMC1_DAT3") (class "Default")
      (node (ref "R71") (pin "1") (pinfunction "1_1") (pintype "passive"))
      (node (ref "SIP") (pin "T8") (pinfunction "MMC1_DAT3_T8_T8") (pintype "bidirectional"))
      (node (ref "U13") (pin "B2") (pinfunction "DAT3_B2") (pintype "bidirectional"))
    )
    (net (code "75") (name "MMC1_DAT4") (class "Default")
      (node (ref "R72") (pin "1") (pinfunction "1_1") (pintype "passive"))
      (node (ref "SIP") (pin "U8") (pinfunction "MMC1_DAT4_U8_U8") (pintype "bidirectional"))
      (node (ref "U13") (pin "B3") (pinfunction "DAT4_B3") (pintype "bidirectional"))
    )
    (net (code "76") (name "MMC1_DAT5") (class "Default")
      (node (ref "R73") (pin "1") (pinfunction "1_1") (pintype "passive"))
      (node (ref "SIP") (pin "V8") (pinfunction "MMC1_DAT5_V8_V8") (pintype "bidirectional"))
      (node (ref "U13") (pin "B4") (pinfunction "DAT5_B4") (pintype "bidirectional"))
    )
    (net (code "77") (name "MMC1_DAT6") (class "Default")
      (node (ref "R74") (pin "1") (pinfunction "1_1") (pintype "passive"))
      (node (ref "SIP") (pin "R9") (pinfunction "MMC1_DAT6_R9_R9") (pintype "bidirectional"))
      (node (ref "U13") (pin "B5") (pinfunction "DAT6_B5") (pintype "bidirectional"))
    )
    (net (code "78") (name "MMC1_DAT7") (class "Default")
      (node (ref "R75") (pin "1") (pinfunction "1_1") (pintype "passive"))
      (node (ref "SIP") (pin "T9") (pinfunction "MMC1_DAT7_T9_T9") (pintype "bidirectional"))
      (node (ref "U13") (pin "B6") (pinfunction "DAT7_B6") (pintype "bidirectional"))
    )
    (net (code "79") (name "MMC2_CLK") (class "Default")
      (node (ref "R76") (pin "1") (pinfunction "1_1") (pintype "passive"))
      (node (ref "U9") (pin "13") (pinfunction "B7_13") (pintype "bidirectional"))
    )
    (net (code "80") (name "MMC2_CMD") (class "Default")
      (node (ref "SIP") (pin "J16") (pinfunction "J16_J16") (pintype "bidirectional"))
      (node (ref "U9") (pin "12") (pinfunction "B8_12") (pintype "bidirectional"))
    )
    (net (code "81") (name "MMC2_DAT0") (class "Default")
      (node (ref "SIP") (pin "J17") (pinfunction "J17_J17") (pintype "bidirectional"))
      (node (ref "U9") (pin "14") (pinfunction "B6_14") (pintype "bidirectional"))
    )
    (net (code "82") (name "MMC2_DAT1") (class "Default")
      (node (ref "SIP") (pin "J18") (pinfunction "J18_J18") (pintype "bidirectional"))
      (node (ref "U9") (pin "15") (pinfunction "B5_15") (pintype "bidirectional"))
    )
    (net (code "83") (name "MMC2_DAT2") (class "Default")
      (node (ref "SIP") (pin "K15") (pinfunction "K15_K15") (pintype "bidirectional"))
      (node (ref "U9") (pin "16") (pinfunction "B4_16") (pintype "bidirectional"))
    )
    (net (code "84") (name "MMC2_DAT3") (class "Default")
      (node (ref "SIP") (pin "H16") (pinfunction "H16_H16") (pintype "bidirectional"))
      (node (ref "U9") (pin "17") (pinfunction "B3_17") (pintype "bidirectional"))
    )
    (net (code "85") (name "MODE_BTN") (class "Default")
      (node (ref "MOD") (pin "2") (pinfunction "2_2") (pintype "passive"))
      (node (ref "SIP") (pin "U6") (pinfunction "TIMER6_U6_U6") (pintype "bidirectional"))
    )
    (net (code "86") (name "MOT_STBY") (class "Default")
      (node (ref "H1") (pin "19") (pinfunction "STBY_19") (pintype "bidirectional"))
      (node (ref "H2") (pin "19") (pinfunction "STBY_19") (pintype "bidirectional"))
      (node (ref "SIP") (pin "D14") (pinfunction "GPIO0_20_D14_D14") (pintype "bidirectional"))
    )
    (net (code "87") (name "Net-(0-PadC)") (class "Default")
      (node (ref "0") (pin "C") (pinfunction "C_C") (pintype "passive"))
      (node (ref "R61") (pin "2") (pinfunction "2_2") (pintype "passive"))
    )
    (net (code "88") (name "Net-(1-PadC)") (class "Default")
      (node (ref "1") (pin "C") (pinfunction "C_C") (pintype "passive"))
      (node (ref "R62") (pin "2") (pinfunction "2_2") (pintype "passive"))
    )
    (net (code "89") (name "Net-(2-PadC)") (class "Default")
      (node (ref "2") (pin "C") (pinfunction "C_C") (pintype "passive"))
      (node (ref "R63") (pin "2") (pinfunction "2_2") (pintype "passive"))
    )
    (net (code "90") (name "Net-(3-PadC)") (class "Default")
      (node (ref "3") (pin "C") (pinfunction "C_C") (pintype "passive"))
      (node (ref "R64") (pin "2") (pinfunction "2_2") (pintype "passive"))
    )
    (net (code "91") (name "Net-(5VREG-OUT)") (class "Default")
      (node (ref "5VREG") (pin "2") (pinfunction "OUT_2") (pintype "power_in"))
      (node (ref "D1") (pin "C") (pinfunction "C_C") (pintype "passive"))
      (node (ref "L1") (pin "1") (pinfunction "1_1") (pintype "passive"))
    )
    (net (code "92") (name "Net-(5VREG-VIN)") (class "Default")
      (node (ref "5VREG") (pin "1") (pinfunction "VIN_1") (pintype "input"))
      (node (ref "C3") (pin "1") (pinfunction "1_1") (pintype "passive"))
      (node (ref "D2") (pin "C") (pinfunction "C_C") (pintype "passive"))
      (node (ref "D3") (pin "C") (pinfunction "C_C") (pintype "passive"))
    )
    (net (code "93") (name "Net-(6VREG-BS)") (class "Default")
      (node (ref "6VREG") (pin "2") (pinfunction "BS_2") (pintype "bidirectional"))
      (node (ref "C22") (pin "1") (pinfunction "1_1") (pintype "passive"))
    )
    (net (code "94") (name "Net-(6VREG-COMP)") (class "Default")
      (node (ref "6VREG") (pin "5") (pinfunction "COMP_5") (pintype "bidirectional"))
      (node (ref "R45") (pin "2") (pinfunction "2_2") (pintype "passive"))
    )
    (net (code "95") (name "Net-(6VREG-FB)") (class "Default")
      (node (ref "6VREG") (pin "6") (pinfunction "FB_6") (pintype "bidirectional"))
      (node (ref "R48") (pin "2") (pinfunction "2_2") (pintype "passive"))
      (node (ref "R49") (pin "1") (pinfunction "1_1") (pintype "passive"))
    )
    (net (code "96") (name "Net-(6VREG-FSW)") (class "Default")
      (node (ref "6VREG") (pin "4") (pinfunction "FSW_4") (pintype "bidirectional"))
      (node (ref "R47") (pin "2") (pinfunction "2_2") (pintype "passive"))
    )
    (net (code "97") (name "Net-(6VREG-LX)") (class "Default")
      (node (ref "6VREG") (pin "1") (pinfunction "LX_1") (pintype "bidirectional"))
      (node (ref "C22") (pin "2") (pinfunction "2_2") (pintype "passive"))
      (node (ref "D9") (pin "C") (pinfunction "C_C") (pintype "passive"))
      (node (ref "L3") (pin "1") (pinfunction "1_1") (pintype "passive"))
    )
    (net (code "98") (name "Net-(6VREG-SS)") (class "Default")
      (node (ref "6VREG") (pin "7") (pinfunction "SS_7") (pintype "bidirectional"))
      (node (ref "C21") (pin "2") (pinfunction "2_2") (pintype "passive"))
    )
    (net (code "99") (name "Net-(ANT1-PadSIG)") (class "Default")
      (node (ref "ANT1") (pin "SIG") (pinfunction "SIG_SIG") (pintype "bidirectional"))
      (node (ref "C48") (pin "1") (pinfunction "1_1") (pintype "passive"))
    )
    (net (code "100") (name "Net-(ANT2-PadSIG)") (class "Default")
      (node (ref "ANT2") (pin "SIG") (pinfunction "SIG_SIG") (pintype "bidirectional"))
      (node (ref "C58") (pin "1") (pinfunction "1_1") (pintype "passive"))
    )
    (net (code "101") (name "Net-(B0-PadC)") (class "Default")
      (node (ref "B0") (pin "C") (pinfunction "C_C") (pintype "passive"))
      (node (ref "R31") (pin "1") (pinfunction "1_1") (pintype "passive"))
    )
    (net (code "102") (name "Net-(B1-PadC)") (class "Default")
      (node (ref "B1") (pin "C") (pinfunction "C_C") (pintype "passive"))
      (node (ref "R29") (pin "1") (pinfunction "1_1") (pintype "passive"))
    )
    (net (code "103") (name "Net-(B2-PadC)") (class "Default")
      (node (ref "B2") (pin "C") (pinfunction "C_C") (pintype "passive"))
      (node (ref "R33") (pin "1") (pinfunction "1_1") (pintype "passive"))
    )
    (net (code "104") (name "Net-(B3-PadC)") (class "Default")
      (node (ref "B3") (pin "C") (pinfunction "C_C") (pintype "passive"))
      (node (ref "R32") (pin "1") (pinfunction "1_1") (pintype "passive"))
    )
    (net (code "105") (name "Net-(BAL-CD)") (class "Default")
      (node (ref "BAL") (pin "4") (pinfunction "CD_4") (pintype "bidirectional"))
      (node (ref "C19") (pin "1") (pinfunction "1_1") (pintype "passive"))
    )
    (net (code "106") (name "Net-(BAL-OUT)") (class "Default")
      (node (ref "BAL") (pin "8") (pinfunction "OUT_8") (pintype "bidirectional"))
      (node (ref "R7") (pin "1") (pinfunction "1_1") (pintype "passive"))
    )
    (net (code "107") (name "Net-(BAL-VC1)") (class "Default")
      (node (ref "BAL") (pin "2") (pinfunction "VC1_2") (pintype "bidirectional"))
      (node (ref "C17") (pin "1") (pinfunction "1_1") (pintype "passive"))
      (node (ref "C18") (pin "2") (pinfunction "2_2") (pintype "passive"))
      (node (ref "R30") (pin "2") (pinfunction "2_2") (pintype "passive"))
    )
    (net (code "108") (name "Net-(BAL-VC1_CB)") (class "Default")
      (node (ref "BAL") (pin "3") (pinfunction "VC1_CB_3") (pintype "bidirectional"))
      (node (ref "R27") (pin "2") (pinfunction "2_2") (pintype "passive"))
    )
    (net (code "109") (name "Net-(BAL-VC2)") (class "Default")
      (node (ref "BAL") (pin "1") (pinfunction "VC2_1") (pintype "bidirectional"))
      (node (ref "C17") (pin "2") (pinfunction "2_2") (pintype "passive"))
      (node (ref "R28") (pin "2") (pinfunction "2_2") (pintype "passive"))
    )
    (net (code "110") (name "Net-(BAL-VDD)") (class "Default")
      (node (ref "BAL") (pin "7") (pinfunction "VDD_7") (pintype "bidirectional"))
      (node (ref "C1") (pin "1") (pinfunction "1_1") (pintype "passive"))
      (node (ref "R34") (pin "2") (pinfunction "2_2") (pintype "passive"))
    )
    (net (code "111") (name "Net-(C23-Pad2)") (class "Default")
      (node (ref "C23") (pin "2") (pinfunction "2_2") (pintype "passive"))
      (node (ref "J2") (pin "P$10") (pinfunction "PWR_P$10") (pintype "bidirectional"))
      (node (ref "J2") (pin "P$11") (pinfunction "PWR_P$11") (pintype "bidirectional"))
      (node (ref "J2") (pin "P$12") (pinfunction "PWR_P$12") (pintype "bidirectional"))
      (node (ref "J2") (pin "P$21") (pinfunction "PWR_P$21") (pintype "bidirectional"))
      (node (ref "J2") (pin "P$22") (pinfunction "PWR_P$22") (pintype "bidirectional"))
      (node (ref "J2") (pin "P$7") (pinfunction "PWR_P$7") (pintype "bidirectional"))
      (node (ref "J2") (pin "P$8") (pinfunction "PWR_P$8") (pintype "bidirectional"))
      (node (ref "J2") (pin "P$9") (pinfunction "PWR_P$9") (pintype "bidirectional"))
      (node (ref "L3") (pin "2") (pinfunction "2_2") (pintype "passive"))
      (node (ref "R49") (pin "2") (pinfunction "2_2") (pintype "passive"))
    )
    (net (code "112") (name "Net-(C24-Pad2)") (class "Default")
      (node (ref "C24") (pin "2") (pinfunction "2_2") (pintype "passive"))
      (node (ref "R45") (pin "1") (pinfunction "1_1") (pintype "passive"))
    )
    (net (code "113") (name "Net-(CHG-PadC)") (class "Default")
      (node (ref "CHG") (pin "C") (pinfunction "C_C") (pintype "passive"))
      (node (ref "R3") (pin "2") (pinfunction "2_2") (pintype "passive"))
    )
    (net (code "114") (name "Net-(CHGIC-BST)") (class "Default")
      (node (ref "C14") (pin "1") (pinfunction "1_1") (pintype "passive"))
      (node (ref "CHGIC") (pin "15") (pinfunction "BST_15") (pintype "bidirectional"))
    )
    (net (code "115") (name "Net-(CHGIC-CHGOK)") (class "Default")
      (node (ref "CHGIC") (pin "11") (pinfunction "CHGOK_11") (pintype "bidirectional"))
      (node (ref "R3") (pin "1") (pinfunction "1_1") (pintype "passive"))
    )
    (net (code "116") (name "Net-(CHGIC-CSP)") (class "Default")
      (node (ref "CHGIC") (pin "10") (pinfunction "CSP_10") (pintype "bidirectional"))
      (node (ref "L2") (pin "2") (pinfunction "2_2") (pintype "passive"))
      (node (ref "R4") (pin "2") (pinfunction "2_2") (pintype "passive"))
    )
    (net (code "117") (name "Net-(CHGIC-NTC)") (class "Default")
      (node (ref "CHGIC") (pin "13") (pinfunction "NTC_13") (pintype "bidirectional"))
      (node (ref "R5") (pin "1") (pinfunction "1_1") (pintype "passive"))
      (node (ref "R6") (pin "2") (pinfunction "2_2") (pintype "passive"))
    )
    (net (code "118") (name "Net-(CHGIC-SW)") (class "Default")
      (node (ref "C14") (pin "2") (pinfunction "2_2") (pintype "passive"))
      (node (ref "CHGIC") (pin "1") (pinfunction "SW_1") (pintype "bidirectional"))
      (node (ref "L2") (pin "1") (pinfunction "1_1") (pintype "passive"))
    )
    (net (code "119") (name "Net-(CHGIC-TMR)") (class "Default")
      (node (ref "C10") (pin "2") (pinfunction "2_2") (pintype "passive"))
      (node (ref "CHGIC") (pin "14") (pinfunction "TMR_14") (pintype "bidirectional"))
    )
    (net (code "120") (name "Net-(G-PadC)") (class "Default")
      (node (ref "G") (pin "C") (pinfunction "C_C") (pintype "passive"))
      (node (ref "R22") (pin "1") (pinfunction "1_1") (pintype "passive"))
    )
    (net (code "121") (name "Net-(IMU-REGOUT)") (class "Default")
      (node (ref "C6") (pin "1") (pinfunction "1_1") (pintype "passive"))
      (node (ref "IMU") (pin "10") (pinfunction "REGOUT_10") (pintype "bidirectional"))
    )
    (net (code "122") (name "Net-(J2-1)") (class "Default")
      (node (ref "J2") (pin "P$1") (pinfunction "1_P$1") (pintype "bidirectional"))
      (node (ref "R36") (pin "2") (pinfunction "2_2") (pintype "passive"))
    )
    (net (code "123") (name "Net-(J2-2)") (class "Default")
      (node (ref "J2") (pin "P$2") (pinfunction "2_P$2") (pintype "bidirectional"))
      (node (ref "R37") (pin "2") (pinfunction "2_2") (pintype "passive"))
    )
    (net (code "124") (name "Net-(J2-3)") (class "Default")
      (node (ref "J2") (pin "P$3") (pinfunction "3_P$3") (pintype "bidirectional"))
      (node (ref "R38") (pin "2") (pinfunction "2_2") (pintype "passive"))
    )
    (net (code "125") (name "Net-(J2-4)") (class "Default")
      (node (ref "J2") (pin "P$4") (pinfunction "4_P$4") (pintype "bidirectional"))
      (node (ref "R39") (pin "2") (pinfunction "2_2") (pintype "passive"))
    )
    (net (code "126") (name "Net-(J2-5)") (class "Default")
      (node (ref "J2") (pin "P$5") (pinfunction "5_P$5") (pintype "bidirectional"))
      (node (ref "R40") (pin "2") (pinfunction "2_2") (pintype "passive"))
    )
    (net (code "127") (name "Net-(J2-6)") (class "Default")
      (node (ref "J2") (pin "P$6") (pinfunction "6_P$6") (pintype "bidirectional"))
      (node (ref "R41") (pin "2") (pinfunction "2_2") (pintype "passive"))
    )
    (net (code "128") (name "Net-(J2-7)") (class "Default")
      (node (ref "J2") (pin "P$19") (pinfunction "7_P$19") (pintype "bidirectional"))
      (node (ref "R42") (pin "2") (pinfunction "2_2") (pintype "passive"))
    )
    (net (code "129") (name "Net-(J2-8)") (class "Default")
      (node (ref "J2") (pin "P$20") (pinfunction "8_P$20") (pintype "bidirectional"))
      (node (ref "R43") (pin "2") (pinfunction "2_2") (pintype "passive"))
    )
    (net (code "130") (name "Net-(M1-1)") (class "Default")
      (node (ref "H1") (pin "5") (pinfunction "A02_5") (pintype "bidirectional"))
      (node (ref "H1") (pin "6") (pinfunction "A02_6") (pintype "bidirectional"))
      (node (ref "M1") (pin "P$1") (pinfunction "1_P$1") (pintype "bidirectional"))
    )
    (net (code "131") (name "Net-(M1-2)") (class "Default")
      (node (ref "H1") (pin "1") (pinfunction "A01_1") (pintype "bidirectional"))
      (node (ref "H1") (pin "2") (pinfunction "A01_2") (pintype "bidirectional"))
      (node (ref "M1") (pin "P$2") (pinfunction "2_P$2") (pintype "bidirectional"))
    )
    (net (code "132") (name "Net-(M2-1)") (class "Default")
      (node (ref "H1") (pin "11") (pinfunction "B01_11") (pintype "bidirectional"))
      (node (ref "H1") (pin "12") (pinfunction "B01_12") (pintype "bidirectional"))
      (node (ref "M2") (pin "P$1") (pinfunction "1_P$1") (pintype "bidirectional"))
    )
    (net (code "133") (name "Net-(M2-2)") (class "Default")
      (node (ref "H1") (pin "7") (pinfunction "B02_7") (pintype "bidirectional"))
      (node (ref "H1") (pin "8") (pinfunction "B02_8") (pintype "bidirectional"))
      (node (ref "M2") (pin "P$2") (pinfunction "2_P$2") (pintype "bidirectional"))
    )
    (net (code "134") (name "Net-(M3-1)") (class "Default")
      (node (ref "H2") (pin "1") (pinfunction "A01_1") (pintype "bidirectional"))
      (node (ref "H2") (pin "2") (pinfunction "A01_2") (pintype "bidirectional"))
      (node (ref "M3") (pin "P$1") (pinfunction "1_P$1") (pintype "bidirectional"))
    )
    (net (code "135") (name "Net-(M3-2)") (class "Default")
      (node (ref "H2") (pin "5") (pinfunction "A02_5") (pintype "bidirectional"))
      (node (ref "H2") (pin "6") (pinfunction "A02_6") (pintype "bidirectional"))
      (node (ref "M3") (pin "P$2") (pinfunction "2_P$2") (pintype "bidirectional"))
    )
    (net (code "136") (name "Net-(M4-1)") (class "Default")
      (node (ref "H2") (pin "7") (pinfunction "B02_7") (pintype "bidirectional"))
      (node (ref "H2") (pin "8") (pinfunction "B02_8") (pintype "bidirectional"))
      (node (ref "M4") (pin "P$1") (pinfunction "1_P$1") (pintype "bidirectional"))
    )
    (net (code "137") (name "Net-(M4-2)") (class "Default")
      (node (ref "H2") (pin "11") (pinfunction "B01_11") (pintype "bidirectional"))
      (node (ref "H2") (pin "12") (pinfunction "B01_12") (pintype "bidirectional"))
      (node (ref "M4") (pin "P$2") (pinfunction "2_P$2") (pintype "bidirectional"))
    )
    (net (code "138") (name "Net-(OSC1-EN)") (class "Default")
      (node (ref "OSC1") (pin "1") (pinfunction "EN_1") (pintype "bidirectional"))
      (node (ref "R90") (pin "1") (pinfunction "1_1") (pintype "passive"))
    )
    (net (code "139") (name "Net-(PROT-VDD)") (class "Default")
      (node (ref "C15") (pin "2") (pinfunction "2_2") (pintype "passive"))
      (node (ref "PROT") (pin "5") (pinfunction "VDD_5") (pintype "bidirectional"))
      (node (ref "R44") (pin "2") (pinfunction "2_2") (pintype "passive"))
    )
    (net (code "140") (name "Net-(R-PadC)") (class "Default")
      (node (ref "R") (pin "C") (pinfunction "C_C") (pintype "passive"))
      (node (ref "R21") (pin "1") (pinfunction "1_1") (pintype "passive"))
    )
    (net (code "141") (name "Net-(R76-Pad2)") (class "Default")
      (node (ref "R76") (pin "2") (pinfunction "2_2") (pintype "passive"))
      (node (ref "SIP") (pin "L15") (pinfunction "L15_L15") (pintype "bidirectional"))
    )
    (net (code "142") (name "Net-(R91-Pad1)") (class "Default")
      (node (ref "R91") (pin "1") (pinfunction "1_1") (pintype "passive"))
      (node (ref "WIFI") (pin "C") (pinfunction "C_C") (pintype "passive"))
    )
    (net (code "143") (name "Net-(SIPA-PMIC_IN_PWR_EN)") (class "Default")
      (node (ref "SIP") (pin "C6") (pinfunction "PMIC_POWER_EN_C6") (pintype "output"))
      (node (ref "SIP") (pin "D19") (pinfunction "PMIC_IN_PWR_EN_D19") (pintype "input"))
      (node (ref "TP5") (pin "TP") (pinfunction "TP_TP") (pintype "input"))
    )
    (net (code "144") (name "Net-(SIPB-JTAG_EMU0)") (class "Default")
      (node (ref "EMU1") (pin "TP") (pinfunction "TP_TP") (pintype "input"))
      (node (ref "SIP") (pin "C14") (pinfunction "JTAG_EMU0_C14") (pintype "bidirectional"))
    )
    (net (code "145") (name "Net-(SIPB-JTAG_EMU1)") (class "Default")
      (node (ref "EMU0") (pin "TP") (pinfunction "TP_TP") (pintype "input"))
      (node (ref "SIP") (pin "B14") (pinfunction "JTAG_EMU1_B14") (pintype "bidirectional"))
    )
    (net (code "146") (name "Net-(SIPB-JTAG_TCK)") (class "Default")
      (node (ref "SIP") (pin "A12") (pinfunction "JTAG_TCK_A12") (pintype "bidirectional"))
      (node (ref "TCK") (pin "TP") (pinfunction "TP_TP") (pintype "input"))
    )
    (net (code "147") (name "Net-(SIPB-JTAG_TDI)") (class "Default")
      (node (ref "SIP") (pin "B11") (pinfunction "JTAG_TDI_B11") (pintype "bidirectional"))
      (node (ref "TDI") (pin "TP") (pinfunction "TP_TP") (pintype "input"))
    )
    (net (code "148") (name "Net-(SIPB-JTAG_TDO)") (class "Default")
      (node (ref "SIP") (pin "A11") (pinfunction "JTAG_TDO_A11") (pintype "bidirectional"))
      (node (ref "TDO") (pin "TP") (pinfunction "TP_TP") (pintype "input"))
    )
    (net (code "149") (name "Net-(SIPB-JTAG_TMS)") (class "Default")
      (node (ref "SIP") (pin "C11") (pinfunction "JTAG_TMS_C11") (pintype "bidirectional"))
      (node (ref "TMS") (pin "TP") (pinfunction "TP_TP") (pintype "input"))
    )
    (net (code "150") (name "Net-(SIPB-JTAG_TRSTN)") (class "Default")
      (node (ref "R59") (pin "2") (pinfunction "2_2") (pintype "passive"))
      (node (ref "SIP") (pin "B10") (pinfunction "JTAG_TRSTN_B10") (pintype "bidirectional"))
      (node (ref "TRSTN") (pin "TP") (pinfunction "TP_TP") (pintype "input"))
    )
    (net (code "151") (name "Net-(SIPB-MMC0_CD_C15)") (class "Default")
      (node (ref "R65") (pin "1") (pinfunction "1_1") (pintype "passive"))
      (node (ref "SIP") (pin "C15") (pinfunction "MMC0_CD_C15_C15") (pintype "bidirectional"))
      (node (ref "X2") (pin "CD") (pinfunction "CD#_CD") (pintype "bidirectional"))
    )
    (net (code "152") (name "Net-(SIPB-MMC0_CLK_G17)") (class "Default")
      (node (ref "R57") (pin "1") (pinfunction "1_1") (pintype "passive"))
      (node (ref "SIP") (pin "G17") (pinfunction "MMC0_CLK_G17_G17") (pintype "bidirectional"))
      (node (ref "X2") (pin "5") (pinfunction "CLK_5") (pintype "bidirectional"))
    )
    (net (code "153") (name "Net-(SIPB-MMC0_CMD_G18)") (class "Default")
      (node (ref "R56") (pin "1") (pinfunction "1_1") (pintype "passive"))
      (node (ref "SIP") (pin "G18") (pinfunction "MMC0_CMD_G18_G18") (pintype "bidirectional"))
      (node (ref "X2") (pin "3") (pinfunction "CMD/DI_3") (pintype "bidirectional"))
    )
    (net (code "154") (name "Net-(SIPB-MMC0_DAT0_G16)") (class "Default")
      (node (ref "R55") (pin "1") (pinfunction "1_1") (pintype "passive"))
      (node (ref "SIP") (pin "G16") (pinfunction "MMC0_DAT0_G16_G16") (pintype "bidirectional"))
      (node (ref "X2") (pin "7") (pinfunction "DAT0/DO_7") (pintype "bidirectional"))
    )
    (net (code "155") (name "Net-(SIPB-MMC0_DAT1_G15)") (class "Default")
      (node (ref "R54") (pin "1") (pinfunction "1_1") (pintype "passive"))
      (node (ref "SIP") (pin "G15") (pinfunction "MMC0_DAT1_G15_G15") (pintype "bidirectional"))
      (node (ref "X2") (pin "8") (pinfunction "DAT1_8") (pintype "bidirectional"))
    )
    (net (code "156") (name "Net-(SIPB-MMC0_DAT2_F18)") (class "Default")
      (node (ref "R35") (pin "1") (pinfunction "1_1") (pintype "passive"))
      (node (ref "SIP") (pin "F18") (pinfunction "MMC0_DAT2_F18_F18") (pintype "bidirectional"))
      (node (ref "X2") (pin "1") (pinfunction "DAT2_1") (pintype "bidirectional"))
    )
    (net (code "157") (name "Net-(SIPB-MMC0_DAT3_F17)") (class "Default")
      (node (ref "R26") (pin "1") (pinfunction "1_1") (pintype "passive"))
      (node (ref "SIP") (pin "F17") (pinfunction "MMC0_DAT3_F17_F17") (pintype "bidirectional"))
      (node (ref "X2") (pin "2") (pinfunction "DAT3/CS_2") (pintype "bidirectional"))
    )
    (net (code "158") (name "Net-(SIPB-MMC1_CLK_U9)") (class "Default")
      (node (ref "R15") (pin "1") (pinfunction "1_1") (pintype "passive"))
      (node (ref "SIP") (pin "U9") (pinfunction "MMC1_CLK_U9_U9") (pintype "bidirectional"))
    )
    (net (code "159") (name "Net-(SIPB-OSC0_GND)") (class "Default")
      (node (ref "C29") (pin "2") (pinfunction "2_2") (pintype "passive"))
      (node (ref "C30") (pin "2") (pinfunction "2_2") (pintype "passive"))
      (node (ref "SIP") (pin "L20") (pinfunction "OSC0_GND_L20") (pintype "bidirectional"))
    )
    (net (code "160") (name "Net-(SIPB-OSC0_IN)") (class "Default")
      (node (ref "C30") (pin "1") (pinfunction "1_1") (pintype "passive"))
      (node (ref "R20") (pin "2") (pinfunction "2_2") (pintype "passive"))
      (node (ref "SIP") (pin "M20") (pinfunction "OSC0_IN_M20") (pintype "bidirectional"))
      (node (ref "Y1") (pin "2") (pinfunction "P$2_2") (pintype "passive"))
    )
    (net (code "161") (name "Net-(SIPB-OSC0_OUT)") (class "Default")
      (node (ref "C29") (pin "1") (pinfunction "1_1") (pintype "passive"))
      (node (ref "R20") (pin "1") (pinfunction "1_1") (pintype "passive"))
      (node (ref "SIP") (pin "K20") (pinfunction "OSC0_OUT_K20") (pintype "bidirectional"))
      (node (ref "Y1") (pin "1") (pinfunction "P$1_1") (pintype "passive"))
    )
    (net (code "162") (name "Net-(SIPB-OSC1_GND)") (class "Default")
      (node (ref "C31") (pin "2") (pinfunction "2_2") (pintype "passive"))
      (node (ref "C32") (pin "1") (pinfunction "1_1") (pintype "passive"))
      (node (ref "SIP") (pin "G20") (pinfunction "OSC1_GND_G20") (pintype "bidirectional"))
    )
    (net (code "163") (name "Net-(SIPB-OSC1_IN)") (class "Default")
      (node (ref "C31") (pin "1") (pinfunction "1_1") (pintype "passive"))
      (node (ref "R18") (pin "2") (pinfunction "2_2") (pintype "passive"))
      (node (ref "SIP") (pin "H20") (pinfunction "OSC1_IN_H20") (pintype "bidirectional"))
      (node (ref "Y2") (pin "P$2") (pinfunction "P$2_P$2") (pintype "passive"))
    )
    (net (code "164") (name "Net-(SIPB-OSC1_OUT)") (class "Default")
      (node (ref "C32") (pin "2") (pinfunction "2_2") (pintype "passive"))
      (node (ref "R18") (pin "1") (pinfunction "1_1") (pintype "passive"))
      (node (ref "SIP") (pin "F20") (pinfunction "OSC1_OUT_F20") (pintype "bidirectional"))
      (node (ref "Y2") (pin "P$1") (pinfunction "P$1_P$1") (pintype "passive"))
    )
    (net (code "165") (name "Net-(SIPC-ADC_VREFP)") (class "Default")
      (node (ref "C42") (pin "1") (pinfunction "1_1") (pintype "passive"))
      (node (ref "C43") (pin "1") (pinfunction "1_1") (pintype "passive"))
      (node (ref "R111") (pin "2") (pinfunction "2_2") (pintype "passive"))
      (node (ref "SIP") (pin "B9") (pinfunction "ADC_VREFP_B9") (pintype "bidirectional"))
    )
    (net (code "166") (name "Net-(SIPC-AIN7)") (class "Default")
      (node (ref "R109") (pin "2") (pinfunction "2_2") (pintype "passive"))
      (node (ref "R110") (pin "1") (pinfunction "1_1") (pintype "passive"))
      (node (ref "SIP") (pin "C9") (pinfunction "AIN7_C9") (pintype "bidirectional"))
    )
    (net (code "167") (name "Net-(SIPC-LCD_DATA11_U4)") (class "Default")
      (node (ref "R135") (pin "2") (pinfunction "2_2") (pintype "passive"))
      (node (ref "SIP") (pin "U4") (pinfunction "LCD_DATA11_U4_U4") (pintype "bidirectional"))
    )
    (net (code "168") (name "Net-(SIPC-USB0_VBUS)") (class "Default")
      (node (ref "R149") (pin "1") (pinfunction "1_1") (pintype "passive"))
      (node (ref "SIP") (pin "P15") (pinfunction "USB0_VBUS_P15") (pintype "bidirectional"))
    )
    (net (code "169") (name "Net-(SIPC-USB1_ID)") (class "Default")
      (node (ref "R150") (pin "1") (pinfunction "1_1") (pintype "passive"))
      (node (ref "SIP") (pin "P17") (pinfunction "USB1_ID_P17") (pintype "bidirectional"))
    )
    (net (code "170") (name "Net-(SIPC-USB1_VBUS)") (class "Default")
      (node (ref "R156") (pin "1") (pinfunction "1_1") (pintype "passive"))
      (node (ref "SIP") (pin "T18") (pinfunction "USB1_VBUS_T18") (pintype "bidirectional"))
    )
    (net (code "171") (name "Net-(SIPE-RTC_KALDO_ENN)") (class "Default")
      (node (ref "R158") (pin "1") (pinfunction "1_1") (pintype "passive"))
      (node (ref "SIP") (pin "B4") (pinfunction "RTC_KALDO_ENN_B4") (pintype "bidirectional"))
    )
    (net (code "172") (name "Net-(U5-WP)") (class "Default")
      (node (ref "R58") (pin "1") (pinfunction "1_1") (pintype "passive"))
      (node (ref "U5") (pin "5") (pinfunction "WP_5") (pintype "input"))
      (node (ref "WP") (pin "P$1") (pinfunction "TP_P$1") (pintype "bidirectional"))
    )
    (net (code "173") (name "Net-(U7-BT_AUD_CLK)") (class "Default")
      (node (ref "R124") (pin "2") (pinfunction "2_2") (pintype "passive"))
      (node (ref "U7") (pin "60") (pinfunction "BT_AUD_CLK_60") (pintype "bidirectional"))
    )
    (net (code "174") (name "Net-(U7-BT_AUD_FSYNC)") (class "Default")
      (node (ref "R123") (pin "2") (pinfunction "2_2") (pintype "passive"))
      (node (ref "U7") (pin "58") (pinfunction "BT_AUD_FSYNC_58") (pintype "bidirectional"))
    )
    (net (code "175") (name "Net-(U7-BT_AUD_IN)") (class "Default")
      (node (ref "R97") (pin "2") (pinfunction "2_2") (pintype "passive"))
      (node (ref "U7") (pin "56") (pinfunction "BT_AUD_IN_56") (pintype "bidirectional"))
    )
    (net (code "176") (name "Net-(U7-BT_AUD_OUT)") (class "Default")
      (node (ref "R100") (pin "2") (pinfunction "2_2") (pintype "passive"))
      (node (ref "U7") (pin "57") (pinfunction "BT_AUD_OUT_57") (pintype "bidirectional"))
    )
    (net (code "177") (name "Net-(U7-BT_HCI_CTS)") (class "Default")
      (node (ref "R86") (pin "2") (pinfunction "2_2") (pintype "passive"))
      (node (ref "U7") (pin "51") (pinfunction "BT_HCI_CTS_51") (pintype "bidirectional"))
    )
    (net (code "178") (name "Net-(U7-BT_HCI_RTS)") (class "Default")
      (node (ref "R85") (pin "2") (pinfunction "2_2") (pintype "passive"))
      (node (ref "U7") (pin "50") (pinfunction "BT_HCI_RTS_50") (pintype "bidirectional"))
    )
    (net (code "179") (name "Net-(U7-BT_HCI_RX)") (class "Default")
      (node (ref "R96") (pin "2") (pinfunction "2_2") (pintype "passive"))
      (node (ref "U7") (pin "53") (pinfunction "BT_HCI_RX_53") (pintype "bidirectional"))
    )
    (net (code "180") (name "Net-(U7-BT_HCI_TX)") (class "Default")
      (node (ref "R92") (pin "2") (pinfunction "2_2") (pintype "passive"))
      (node (ref "U7") (pin "52") (pinfunction "BT_HCI_TX_52") (pintype "bidirectional"))
    )
    (net (code "181") (name "Net-(U7-RF_ANT1)") (class "Default")
      (node (ref "C48") (pin "2") (pinfunction "2_2") (pintype "passive"))
      (node (ref "U7") (pin "32") (pinfunction "RF_ANT1_32") (pintype "bidirectional"))
    )
    (net (code "182") (name "Net-(U7-RF_ANT2)") (class "Default")
      (node (ref "C58") (pin "2") (pinfunction "2_2") (pintype "passive"))
      (node (ref "U7") (pin "18") (pinfunction "RF_ANT2_18") (pintype "bidirectional"))
    )
    (net (code "183") (name "Net-(U7-WLAN_IRQ)") (class "Default")
      (node (ref "R84") (pin "2") (pinfunction "2_2") (pintype "passive"))
      (node (ref "R9") (pin "2") (pinfunction "2_2") (pintype "passive"))
      (node (ref "U7") (pin "14") (pinfunction "WLAN_IRQ_14") (pintype "bidirectional"))
    )
    (net (code "184") (name "Net-(U7-WL_SDIO_CLK)") (class "Default")
      (node (ref "R78") (pin "2") (pinfunction "2_2") (pintype "passive"))
      (node (ref "U7") (pin "8") (pinfunction "WL_SDIO_CLK_8") (pintype "bidirectional"))
    )
    (net (code "185") (name "Net-(U7-WL_SDIO_CMD)") (class "Default")
      (node (ref "R79") (pin "2") (pinfunction "2_2") (pintype "passive"))
      (node (ref "U7") (pin "6") (pinfunction "WL_SDIO_CMD_6") (pintype "bidirectional"))
    )
    (net (code "186") (name "Net-(U7-WL_SDIO_D0)") (class "Default")
      (node (ref "R80") (pin "2") (pinfunction "2_2") (pintype "passive"))
      (node (ref "U7") (pin "10") (pinfunction "WL_SDIO_D0_10") (pintype "bidirectional"))
    )
    (net (code "187") (name "Net-(U7-WL_SDIO_D1)") (class "Default")
      (node (ref "R81") (pin "2") (pinfunction "2_2") (pintype "passive"))
      (node (ref "U7") (pin "11") (pinfunction "WL_SDIO_D1_11") (pintype "bidirectional"))
    )
    (net (code "188") (name "Net-(U7-WL_SDIO_D2)") (class "Default")
      (node (ref "R82") (pin "2") (pinfunction "2_2") (pintype "passive"))
      (node (ref "U7") (pin "12") (pinfunction "WL_SDIO_D2_12") (pintype "bidirectional"))
    )
    (net (code "189") (name "Net-(U7-WL_SDIO_D3)") (class "Default")
      (node (ref "R83") (pin "2") (pinfunction "2_2") (pintype "passive"))
      (node (ref "U7") (pin "13") (pinfunction "WL_SDIO_D3_13") (pintype "bidirectional"))
    )
    (net (code "190") (name "Net-(U10-OE)") (class "Default")
      (node (ref "R106") (pin "2") (pinfunction "2_2") (pintype "passive"))
      (node (ref "R93") (pin "2") (pinfunction "2_2") (pintype "passive"))
      (node (ref "U10") (pin "10") (pinfunction "OE_10") (pintype "bidirectional"))
      (node (ref "U2") (pin "1") (pinfunction "OE_1") (pintype "input"))
      (node (ref "U9") (pin "10") (pinfunction "OE_10") (pintype "bidirectional"))
    )
    (net (code "191") (name "Net-(U13-VDDI)") (class "Default")
      (node (ref "C36") (pin "1") (pinfunction "1_1") (pintype "passive"))
      (node (ref "U13") (pin "C2") (pinfunction "VDDI_C2") (pintype "bidirectional"))
    )
    (net (code "192") (name "Net-(X3-GND)") (class "Default")
      (node (ref "L4") (pin "2") (pinfunction "2_2") (pintype "passive"))
      (node (ref "X3") (pin "4") (pinfunction "GND_4") (pintype "bidirectional"))
    )
    (net (code "193") (name "Net-(X3-VBUS)") (class "Default")
      (node (ref "L5") (pin "2") (pinfunction "2_2") (pintype "passive"))
      (node (ref "X3") (pin "1") (pinfunction "VBUS_1") (pintype "bidirectional"))
    )
    (net (code "194") (name "PAUSE_BTN") (class "Default")
      (node (ref "PAU") (pin "2") (pinfunction "2_2") (pintype "passive"))
      (node (ref "SIP") (pin "T6") (pinfunction "TIMER5_T6_T6") (pintype "bidirectional"))
    )
    (net (code "195") (name "PMIC_INT") (class "Default")
      (node (ref "SIP") (pin "B18") (pinfunction "EXTINTN_B18") (pintype "bidirectional"))
      (node (ref "SIP") (pin "B19") (pinfunction "PMIC_OUT_NINT_B19") (pintype "output"))
    )
    (net (code "196") (name "PMIC_NWAKEUP") (class "Default")
      (node (ref "SIP") (pin "A19") (pinfunction "PMIC_OUT_NWAKEUP_A19") (pintype "output"))
      (node (ref "SIP") (pin "C5") (pinfunction "EXT_WAKEUP_C5") (pintype "bidirectional"))
    )
    (net (code "197") (name "PMIC_PGOOD") (class "Default")
      (node (ref "SIP") (pin "A20") (pinfunction "PMIC_OUT_PGOOD_A20") (pintype "output"))
      (node (ref "SIP") (pin "B15") (pinfunction "PWRONRSTN_B15") (pintype "bidirectional"))
      (node (ref "U6") (pin "2") (pinfunction "A_2") (pintype "input"))
    )
    (net (code "198") (name "POWER_BTN") (class "Default")
      (node (ref "POW") (pin "2") (pinfunction "2_2") (pintype "passive"))
      (node (ref "SIP") (pin "D20") (pinfunction "PMIC_IN_PB_IN_D20") (pintype "bidirectional"))
    )
    (net (code "199") (name "PRU_E_A") (class "Default")
      (node (ref "E4") (pin "3") (pinfunction "3_3") (pintype "bidirectional"))
      (node (ref "SIP") (pin "V13") (pinfunction "GPIO1_14_V13_V13") (pintype "bidirectional"))
    )
    (net (code "200") (name "PRU_E_B") (class "Default")
      (node (ref "E4") (pin "4") (pinfunction "4_4") (pintype "bidirectional"))
      (node (ref "SIP") (pin "U13") (pinfunction "GPIO1_15_U13_U13") (pintype "bidirectional"))
    )
    (net (code "201") (name "PWM_1A") (class "Default")
      (node (ref "H1") (pin "23") (pinfunction "PWMA_23") (pintype "bidirectional"))
      (node (ref "SIP") (pin "U14") (pinfunction "EHRPWM1A_U14_U14") (pintype "bidirectional"))
    )
    (net (code "202") (name "PWM_1B") (class "Default")
      (node (ref "H1") (pin "15") (pinfunction "PWMB_15") (pintype "bidirectional"))
      (node (ref "SIP") (pin "T14") (pinfunction "EHRPWM1B_T14_T14") (pintype "bidirectional"))
    )
    (net (code "203") (name "PWM_2A") (class "Default")
      (node (ref "H2") (pin "23") (pinfunction "PWMA_23") (pintype "bidirectional"))
      (node (ref "SIP") (pin "U10") (pinfunction "EHRPWM2A_U10_U10") (pintype "bidirectional"))
    )
    (net (code "204") (name "PWM_2B") (class "Default")
      (node (ref "H2") (pin "15") (pinfunction "PWMB_15") (pintype "bidirectional"))
      (node (ref "SIP") (pin "T10") (pinfunction "EHRPWM2B_T10_T10") (pintype "bidirectional"))
    )
    (net (code "205") (name "PWR_LED") (class "Default")
      (node (ref "ON") (pin "C") (pinfunction "C_C") (pintype "passive"))
      (node (ref "R24") (pin "1") (pinfunction "1_1") (pintype "passive"))
    )
    (net (code "206") (name "RESET") (class "Default")
      (node (ref "C33") (pin "1") (pinfunction "1_1") (pintype "passive"))
      (node (ref "R60") (pin "1") (pinfunction "1_1") (pintype "passive"))
      (node (ref "RST") (pin "2") (pinfunction "2_2") (pintype "passive"))
      (node (ref "SIP") (pin "A10") (pinfunction "WARMRSTN_A10") (pintype "bidirectional"))
      (node (ref "U6") (pin "4") (pinfunction "Y_4") (pintype "output"))
    )
    (net (code "207") (name "SD_BOOT") (class "Default")
      (node (ref "R77") (pin "2") (pinfunction "2_2") (pintype "passive"))
      (node (ref "SD") (pin "2") (pinfunction "2_2") (pintype "passive"))
    )
    (net (code "208") (name "SERVO_EN") (class "Default")
      (node (ref "6VREG") (pin "8") (pinfunction "EN_8") (pintype "bidirectional"))
      (node (ref "R46") (pin "2") (pinfunction "2_2") (pintype "passive"))
      (node (ref "SIP") (pin "U3") (pinfunction "LCD_DATA10_U3_U3") (pintype "bidirectional"))
    )
    (net (code "209") (name "SPI1_MISO") (class "Default")
      (node (ref "S1.1") (pin "4") (pinfunction "4_4") (pintype "bidirectional"))
      (node (ref "S1.2") (pin "4") (pinfunction "4_4") (pintype "bidirectional"))
      (node (ref "SIP") (pin "B13") (pinfunction "SPI1_D0_B13_B13") (pintype "bidirectional"))
    )
    (net (code "210") (name "SPI1_MOSI") (class "Default")
      (node (ref "S1.1") (pin "3") (pinfunction "3_3") (pintype "bidirectional"))
      (node (ref "S1.2") (pin "3") (pinfunction "3_3") (pintype "bidirectional"))
      (node (ref "SIP") (pin "D12") (pinfunction "SPI1_D1_D12_D12") (pintype "bidirectional"))
    )
    (net (code "211") (name "SPI1_SCK") (class "Default")
      (node (ref "S1.1") (pin "5") (pinfunction "5_5") (pintype "bidirectional"))
      (node (ref "S1.2") (pin "5") (pinfunction "5_5") (pintype "bidirectional"))
      (node (ref "SIP") (pin "A13") (pinfunction "SPI1_CLK_A13_A13") (pintype "bidirectional"))
    )
    (net (code "212") (name "SPI1_SS1") (class "Default")
      (node (ref "S1.1") (pin "6") (pinfunction "6_6") (pintype "bidirectional"))
      (node (ref "SIP") (pin "H18") (pinfunction "H18_H18") (pintype "bidirectional"))
    )
    (net (code "213") (name "SPI1_SS2") (class "Default")
      (node (ref "S1.2") (pin "6") (pinfunction "6_6") (pintype "bidirectional"))
      (node (ref "SIP") (pin "C18") (pinfunction "GPIO0_7_C18_C18") (pintype "bidirectional"))
    )
    (net (code "214") (name "SVO1") (class "Default")
      (node (ref "R36") (pin "1") (pinfunction "1_1") (pintype "passive"))
      (node (ref "R50") (pin "1") (pinfunction "1_1") (pintype "passive"))
      (node (ref "SIP") (pin "U5") (pinfunction "LCD_VSYNC_U5_U5") (pintype "bidirectional"))
    )
    (net (code "215") (name "SVO2") (class "Default")
      (node (ref "R37") (pin "1") (pinfunction "1_1") (pintype "passive"))
      (node (ref "R51") (pin "1") (pinfunction "1_1") (pintype "passive"))
      (node (ref "SIP") (pin "V5") (pinfunction "LCD_PCLK_V5_V5") (pintype "bidirectional"))
    )
    (net (code "216") (name "SVO3") (class "Default")
      (node (ref "R38") (pin "1") (pinfunction "1_1") (pintype "passive"))
      (node (ref "R52") (pin "1") (pinfunction "1_1") (pintype "passive"))
      (node (ref "SIP") (pin "R5") (pinfunction "LCD_HSYNC_R5_R5") (pintype "bidirectional"))
    )
    (net (code "217") (name "SVO4") (class "Default")
      (node (ref "R39") (pin "1") (pinfunction "1_1") (pintype "passive"))
      (node (ref "R53") (pin "1") (pinfunction "1_1") (pintype "passive"))
      (node (ref "SIP") (pin "R6") (pinfunction "LCD_DE_R6_R6") (pintype "bidirectional"))
    )
    (net (code "218") (name "SVO5") (class "Default")
      (node (ref "R125") (pin "2") (pinfunction "2_2") (pintype "passive"))
      (node (ref "R40") (pin "1") (pinfunction "1_1") (pintype "passive"))
      (node (ref "SIP") (pin "T3") (pinfunction "LCD_DATA6_T3_T3") (pintype "bidirectional"))
    )
    (net (code "219") (name "SVO6") (class "Default")
      (node (ref "R127") (pin "2") (pinfunction "2_2") (pintype "passive"))
      (node (ref "R41") (pin "1") (pinfunction "1_1") (pintype "passive"))
      (node (ref "SIP") (pin "T4") (pinfunction "LCD_DATA7_T4_T4") (pintype "bidirectional"))
    )
    (net (code "220") (name "SVO7") (class "Default")
      (node (ref "R120") (pin "1") (pinfunction "1_1") (pintype "passive"))
      (node (ref "R42") (pin "1") (pinfunction "1_1") (pintype "passive"))
      (node (ref "SIP") (pin "T1") (pinfunction "LCD_DATA4_T1_T1") (pintype "bidirectional"))
    )
    (net (code "221") (name "SVO8") (class "Default")
      (node (ref "R122") (pin "1") (pinfunction "1_1") (pintype "passive"))
      (node (ref "R43") (pin "1") (pinfunction "1_1") (pintype "passive"))
      (node (ref "SIP") (pin "T2") (pinfunction "LCD_DATA5_T2_T2") (pintype "bidirectional"))
    )
    (net (code "222") (name "SYS_5V") (class "Default")
      (node (ref "C62") (pin "1") (pinfunction "1_1") (pintype "passive"))
      (node (ref "R121") (pin "2") (pinfunction "2_2") (pintype "passive"))
      (node (ref "SIP") (pin "W4") (pinfunction "VOUT_SYS_5V_0_W4") (pintype "power_in"))
      (node (ref "SIP") (pin "Y4") (pinfunction "VOUT_SYS_5V_1_Y4") (pintype "power_in"))
      (node (ref "TP1") (pin "TP") (pinfunction "TP_TP") (pintype "input"))
      (node (ref "U1") (pin "3") (pinfunction "VCC_3") (pintype "power_in"))
      (node (ref "U8") (pin "3") (pinfunction "IN2_3") (pintype "input"))
    )
    (net (code "223") (name "UART0_RX") (class "Default")
      (node (ref "SIP") (pin "E15") (pinfunction "UART0_RXD_E15_E15") (pintype "bidirectional"))
      (node (ref "UT0") (pin "3") (pinfunction "3_3") (pintype "bidirectional"))
    )
    (net (code "224") (name "UART0_TX") (class "Default")
      (node (ref "SIP") (pin "E16") (pinfunction "UART0_TXD_E16_E16") (pintype "bidirectional"))
      (node (ref "UT0") (pin "4") (pinfunction "4_4") (pintype "bidirectional"))
    )
    (net (code "225") (name "UART1_RX") (class "Default")
      (node (ref "SIP") (pin "D16") (pinfunction "UART1_RXD_D16_D16") (pintype "bidirectional"))
      (node (ref "UT1") (pin "3") (pinfunction "3_3") (pintype "bidirectional"))
    )
    (net (code "226") (name "UART1_TX") (class "Default")
      (node (ref "SIP") (pin "D15") (pinfunction "UART1_TXD_D15_D15") (pintype "bidirectional"))
      (node (ref "UT1") (pin "4") (pinfunction "4_4") (pintype "bidirectional"))
    )
    (net (code "227") (name "UART2_RX") (class "Default")
      (node (ref "GPS") (pin "3") (pinfunction "3_3") (pintype "bidirectional"))
      (node (ref "SIP") (pin "A17") (pinfunction "UART2_RXD_A17_A17") (pintype "bidirectional"))
    )
    (net (code "228") (name "UART2_TX") (class "Default")
      (node (ref "GPS") (pin "4") (pinfunction "4_4") (pintype "bidirectional"))
      (node (ref "SIP") (pin "B17") (pinfunction "UART2_TXD_B17_B17") (pintype "bidirectional"))
    )
    (net (code "229") (name "UART3_CTSN") (class "Default")
      (node (ref "R89") (pin "1") (pinfunction "1_1") (pintype "passive"))
      (node (ref "SIP") (pin "M17") (pinfunction "M17_M17") (pintype "bidirectional"))
      (node (ref "U10") (pin "12") (pinfunction "B8_12") (pintype "bidirectional"))
    )
    (net (code "230") (name "UART3_RTSN") (class "Default")
      (node (ref "R108") (pin "1") (pinfunction "1_1") (pintype "passive"))
      (node (ref "SIP") (pin "M18") (pinfunction "M18_M18") (pintype "bidirectional"))
      (node (ref "U10") (pin "13") (pinfunction "B7_13") (pintype "bidirectional"))
    )
    (net (code "231") (name "UART3_RX") (class "Default")
      (node (ref "SIP") (pin "L17") (pinfunction "L17_L17") (pintype "bidirectional"))
      (node (ref "U10") (pin "14") (pinfunction "B6_14") (pintype "bidirectional"))
    )
    (net (code "232") (name "UART3_TX") (class "Default")
      (node (ref "SIP") (pin "L16") (pinfunction "L16_L16") (pintype "bidirectional"))
      (node (ref "U10") (pin "15") (pinfunction "B5_15") (pintype "bidirectional"))
    )
    (net (code "233") (name "UART4_RX") (class "Default")
      (node (ref "DSM2") (pin "P$3") (pinfunction "3_P$3") (pintype "bidirectional"))
      (node (ref "SIP") (pin "T17") (pinfunction "UART4_RXD_T17_T17") (pintype "bidirectional"))
    )
    (net (code "234") (name "UART5_RX") (class "Default")
      (node (ref "R131") (pin "2") (pinfunction "2_2") (pintype "passive"))
      (node (ref "SIP") (pin "U2") (pinfunction "LCD_DATA9_U2_U2") (pintype "bidirectional"))
      (node (ref "UT5") (pin "3") (pinfunction "3_3") (pintype "bidirectional"))
    )
    (net (code "235") (name "UART5_TX") (class "Default")
      (node (ref "R129") (pin "2") (pinfunction "2_2") (pintype "passive"))
      (node (ref "SIP") (pin "U1") (pinfunction "LCD_DATA8_U1_U1") (pintype "bidirectional"))
      (node (ref "UT5") (pin "4") (pinfunction "4_4") (pintype "bidirectional"))
    )
    (net (code "236") (name "USB0_D_N") (class "Default")
      (node (ref "SIP") (pin "N18") (pinfunction "USB0_DM_N18") (pintype "bidirectional"))
      (node (ref "U3") (pin "2") (pinfunction "D-_2") (pintype "bidirectional"))
      (node (ref "X4") (pin "D-") (pinfunction "D-_D-") (pintype "input"))
    )
    (net (code "237") (name "USB0_D_P") (class "Default")
      (node (ref "SIP") (pin "N17") (pinfunction "USB0_DP_N17") (pintype "bidirectional"))
      (node (ref "U3") (pin "1") (pinfunction "D+_1") (pintype "bidirectional"))
      (node (ref "X4") (pin "D+") (pinfunction "D+_D+") (pintype "input"))
    )
    (net (code "238") (name "USB0_ID") (class "Default")
      (node (ref "SIP") (pin "P16") (pinfunction "USB0_ID_P16") (pintype "bidirectional"))
      (node (ref "U3") (pin "3") (pinfunction "ID_3") (pintype "bidirectional"))
      (node (ref "X4") (pin "ID") (pinfunction "ID_ID") (pintype "input"))
    )
    (net (code "239") (name "USB0_VBUS") (class "Default")
      (node (ref "C54") (pin "1") (pinfunction "1_1") (pintype "passive"))
      (node (ref "R112") (pin "2") (pinfunction "2_2") (pintype "passive"))
      (node (ref "R149") (pin "2") (pinfunction "2_2") (pintype "passive"))
      (node (ref "U3") (pin "6") (pinfunction "VBUS_6") (pintype "bidirectional"))
      (node (ref "X4") (pin "VBUS") (pinfunction "VBUS_VBUS") (pintype "input"))
    )
    (net (code "240") (name "USB1_D_N") (class "Default")
      (node (ref "SIP") (pin "R18") (pinfunction "USB1_DM_R18") (pintype "bidirectional"))
      (node (ref "U4") (pin "2") (pinfunction "D-_2") (pintype "bidirectional"))
      (node (ref "X3") (pin "2") (pinfunction "D-_2") (pintype "bidirectional"))
    )
    (net (code "241") (name "USB1_D_P") (class "Default")
      (node (ref "SIP") (pin "R17") (pinfunction "USB1_DP_R17") (pintype "bidirectional"))
      (node (ref "U4") (pin "1") (pinfunction "D+_1") (pintype "bidirectional"))
      (node (ref "X3") (pin "3") (pinfunction "D+_3") (pintype "bidirectional"))
    )
    (net (code "242") (name "USB1_VBUS") (class "Default")
      (node (ref "C45") (pin "1") (pinfunction "1_1") (pintype "passive"))
      (node (ref "C46") (pin "1") (pinfunction "1_1") (pintype "passive"))
      (node (ref "C55") (pin "1") (pinfunction "1_1") (pintype "passive"))
      (node (ref "C61") (pin "2") (pinfunction "2_2") (pintype "passive"))
      (node (ref "L5") (pin "1") (pinfunction "1_1") (pintype "passive"))
      (node (ref "R119") (pin "1") (pinfunction "1_1") (pintype "passive"))
      (node (ref "R121") (pin "1") (pinfunction "1_1") (pintype "passive"))
      (node (ref "R156") (pin "2") (pinfunction "2_2") (pintype "passive"))
      (node (ref "U4") (pin "6") (pinfunction "VBUS_6") (pintype "bidirectional"))
      (node (ref "U8") (pin "4") (pinfunction "OUT_4") (pintype "output"))
    )
    (net (code "243") (name "USB_DC") (class "Default")
      (node (ref "R112") (pin "1") (pinfunction "1_1") (pintype "passive"))
      (node (ref "SIP") (pin "Y8") (pinfunction "VIN_USB_0_Y8") (pintype "power_in"))
      (node (ref "SIP") (pin "Y9") (pinfunction "VIN_USB_1_Y9") (pintype "power_in"))
    )
    (net (code "244") (name "USR_LED0") (class "Default")
      (node (ref "0") (pin "A") (pinfunction "A_A") (pintype "passive"))
      (node (ref "SIP") (pin "V15") (pinfunction "USR0_V15_V15") (pintype "bidirectional"))
    )
    (net (code "245") (name "USR_LED1") (class "Default")
      (node (ref "1") (pin "A") (pinfunction "A_A") (pintype "passive"))
      (node (ref "SIP") (pin "U15") (pinfunction "USR1_U15_U15") (pintype "bidirectional"))
    )
    (net (code "246") (name "USR_LED2") (class "Default")
      (node (ref "2") (pin "A") (pinfunction "A_A") (pintype "passive"))
      (node (ref "SIP") (pin "T15") (pinfunction "USR2_T15_T15") (pintype "bidirectional"))
    )
    (net (code "247") (name "USR_LED3") (class "Default")
      (node (ref "3") (pin "A") (pinfunction "A_A") (pintype "passive"))
      (node (ref "SIP") (pin "V16") (pinfunction "USR3_V16_V16") (pintype "bidirectional"))
    )
    (net (code "248") (name "VCC") (class "Default")
      (node (ref "12V") (pin "IN") (pinfunction "IN_IN") (pintype "bidirectional"))
      (node (ref "C12") (pin "1") (pinfunction "1_1") (pintype "passive"))
      (node (ref "C7") (pin "1") (pinfunction "1_1") (pintype "passive"))
      (node (ref "CHG") (pin "A") (pinfunction "A_A") (pintype "passive"))
      (node (ref "CHGIC") (pin "2") (pinfunction "VIN_2") (pintype "bidirectional"))
      (node (ref "D3") (pin "A") (pinfunction "A_A") (pintype "passive"))
      (node (ref "R1") (pin "1") (pinfunction "1_1") (pintype "passive"))
    )
    (net (code "249") (name "VCC_CHG") (class "Default")
      (node (ref "C4") (pin "2") (pinfunction "2_2") (pintype "passive"))
      (node (ref "CHGIC") (pin "3") (pinfunction "VCC_3") (pintype "bidirectional"))
      (node (ref "R5") (pin "2") (pinfunction "2_2") (pintype "passive"))
    )
    (net (code "250") (name "VDD_1V8") (class "Default")
      (node (ref "C47") (pin "1") (pinfunction "1_1") (pintype "passive"))
      (node (ref "C50") (pin "1") (pinfunction "1_1") (pintype "passive"))
      (node (ref "C52") (pin "1") (pinfunction "1_1") (pintype "passive"))
      (node (ref "C57") (pin "2") (pinfunction "2_2") (pintype "passive"))
      (node (ref "C60") (pin "2") (pinfunction "2_2") (pintype "passive"))
      (node (ref "OSC1") (pin "4") (pinfunction "VCC_4") (pintype "bidirectional"))
      (node (ref "R101") (pin "1") (pinfunction "1_1") (pintype "passive"))
      (node (ref "R102") (pin "1") (pinfunction "1_1") (pintype "passive"))
      (node (ref "R103") (pin "1") (pinfunction "1_1") (pintype "passive"))
      (node (ref "R105") (pin "1") (pinfunction "1_1") (pintype "passive"))
      (node (ref "R9") (pin "1") (pinfunction "1_1") (pintype "passive"))
      (node (ref "R90") (pin "2") (pinfunction "2_2") (pintype "passive"))
      (node (ref "R98") (pin "1") (pinfunction "1_1") (pintype "passive"))
      (node (ref "R99") (pin "1") (pinfunction "1_1") (pintype "passive"))
      (node (ref "SIP") (pin "D10") (pinfunction "VDD_1V84_D10") (pintype "bidirectional"))
      (node (ref "SIP") (pin "E9") (pinfunction "VDD_1V83_E9") (pintype "bidirectional"))
      (node (ref "SIP") (pin "N16") (pinfunction "VOUT_LDO3_1P8V_0_N16") (pintype "power_in"))
      (node (ref "SIP") (pin "R16") (pinfunction "VOUT_LDO3_1P8V_1_R16") (pintype "power_in"))
      (node (ref "U10") (pin "2") (pinfunction "VCCA_2") (pintype "bidirectional"))
      (node (ref "U2") (pin "5") (pinfunction "VCC_5") (pintype "power_in"))
      (node (ref "U7") (pin "38") (pinfunction "VIO_38") (pintype "bidirectional"))
      (node (ref "U9") (pin "2") (pinfunction "VCCA_2") (pintype "bidirectional"))
    )
    (net (code "251") (name "VDD_3V3AUX") (class "Default")
      (node (ref "ON") (pin "A") (pinfunction "A_A") (pintype "passive"))
      (node (ref "SIP") (pin "Y11") (pinfunction "VOUT_LDO2_3P3V_Y11") (pintype "power_in"))
    )
    (net (code "252") (name "VDD_ADC") (class "Default")
      (node (ref "ADC") (pin "2") (pinfunction "2_2") (pintype "bidirectional"))
      (node (ref "C44") (pin "1") (pinfunction "1_1") (pintype "passive"))
      (node (ref "R111") (pin "1") (pinfunction "1_1") (pintype "passive"))
      (node (ref "SIP") (pin "A4") (pinfunction "VOUT_ADC_1P8V_0_A4") (pintype "bidirectional"))
      (node (ref "SIP") (pin "A5") (pinfunction "VOUT_ADC_1P8V_1_A5") (pintype "bidirectional"))
      (node (ref "SIP") (pin "D8") (pinfunction "VDDA_ADC_D8") (pintype "bidirectional"))
    )
    (net (code "253") (name "VDD_RTC") (class "Default")
      (node (ref "SIP") (pin "E14") (pinfunction "VDD_RTC3_E14") (pintype "bidirectional"))
      (node (ref "U6") (pin "5") (pinfunction "VCC_5") (pintype "power_in"))
    )
    (net (code "254") (name "VIN_BAT_0") (class "Default")
      (node (ref "SIP") (pin "Y2") (pinfunction "VIN_BAT_0_Y2") (pintype "power_in"))
    )
    (net (code "255") (name "VIN_BAT_1") (class "Default")
      (node (ref "SIP") (pin "Y3") (pinfunction "VIN_BAT_1_Y3") (pintype "power_in"))
    )
    (net (code "256") (name "V_BATT") (class "Default")
      (node (ref "6VREG") (pin "9") (pinfunction "VIN_9") (pintype "bidirectional"))
      (node (ref "C11") (pin "+") (pinfunction "+_+") (pintype "passive"))
      (node (ref "C20") (pin "2") (pinfunction "2_2") (pintype "passive"))
      (node (ref "C25") (pin "1") (pinfunction "1_1") (pintype "passive"))
      (node (ref "C26") (pin "1") (pinfunction "1_1") (pintype "passive"))
      (node (ref "CHGIC") (pin "9") (pinfunction "BATT_9") (pintype "bidirectional"))
      (node (ref "D2") (pin "A") (pinfunction "A_A") (pintype "passive"))
      (node (ref "H1") (pin "13") (pinfunction "VM2_13") (pintype "bidirectional"))
      (node (ref "H1") (pin "14") (pinfunction "VM3_14") (pintype "bidirectional"))
      (node (ref "H1") (pin "24") (pinfunction "VM1_24") (pintype "bidirectional"))
      (node (ref "H2") (pin "13") (pinfunction "VM2_13") (pintype "bidirectional"))
      (node (ref "H2") (pin "14") (pinfunction "VM3_14") (pintype "bidirectional"))
      (node (ref "H2") (pin "24") (pinfunction "VM1_24") (pintype "bidirectional"))
      (node (ref "LIPO") (pin "P$1") (pinfunction "1_P$1") (pintype "passive"))
      (node (ref "R19") (pin "1") (pinfunction "1_1") (pintype "passive"))
      (node (ref "R28") (pin "1") (pinfunction "1_1") (pintype "passive"))
      (node (ref "R34") (pin "1") (pinfunction "1_1") (pintype "passive"))
      (node (ref "R4") (pin "1") (pinfunction "1_1") (pintype "passive"))
    )
    (net (code "257") (name "V_DIV_BAT") (class "Default")
      (node (ref "R19") (pin "2") (pinfunction "2_2") (pintype "passive"))
      (node (ref "R25") (pin "1") (pinfunction "1_1") (pintype "passive"))
      (node (ref "SIP") (pin "A8") (pinfunction "AIN6_A8") (pintype "bidirectional"))
    )
    (net (code "258") (name "V_DIV_DC") (class "Default")
      (node (ref "R1") (pin "2") (pinfunction "2_2") (pintype "passive"))
      (node (ref "R14") (pin "1") (pinfunction "1_1") (pintype "passive"))
      (node (ref "SIP") (pin "B8") (pinfunction "AIN5_B8") (pintype "bidirectional"))
    )
    (net (code "259") (name "WIFI_LED") (class "Default")
      (node (ref "SIP") (pin "A15") (pinfunction "GPIO0_19_A15_A15") (pintype "bidirectional"))
      (node (ref "WIFI") (pin "A") (pinfunction "A_A") (pintype "passive"))
    )
    (net (code "260") (name "WLAN_IRQ") (class "Default")
      (node (ref "SIP") (pin "K16") (pinfunction "K16_K16") (pintype "bidirectional"))
      (node (ref "U2") (pin "4") (pinfunction "Y_4") (pintype "output"))
    )
    (net (code "261") (name "WL_BT_OE") (class "Default")
      (node (ref "R93") (pin "1") (pinfunction "1_1") (pintype "passive"))
      (node (ref "SIP") (pin "L18") (pinfunction "L18_L18") (pintype "bidirectional"))
    )
    (net (code "262") (name "WL_EN") (class "Default")
      (node (ref "SIP") (pin "K18") (pinfunction "K18_K18") (pintype "bidirectional"))
      (node (ref "U9") (pin "20") (pinfunction "B1_20") (pintype "bidirectional"))
    )
    (net (code "263") (name "WL_EN_1V8") (class "Default")
      (node (ref "R87") (pin "1") (pinfunction "1_1") (pintype "passive"))
      (node (ref "U7") (pin "40") (pinfunction "WLAN_EN_40") (pintype "bidirectional"))
      (node (ref "U9") (pin "1") (pinfunction "A1_1") (pintype "bidirectional"))
    )
    (net (code "264") (name "WL_IRQ") (class "Default")
      (node (ref "R84") (pin "1") (pinfunction "1_1") (pintype "passive"))
      (node (ref "U2") (pin "2") (pinfunction "A_2") (pintype "input"))
    )
    (net (code "265") (name "WL_SDIO_CLK") (class "Default")
      (node (ref "R103") (pin "2") (pinfunction "2_2") (pintype "passive"))
      (node (ref "R78") (pin "1") (pinfunction "1_1") (pintype "passive"))
      (node (ref "U9") (pin "8") (pinfunction "A7_8") (pintype "bidirectional"))
    )
    (net (code "266") (name "WL_SDIO_CMD") (class "Default")
      (node (ref "R105") (pin "2") (pinfunction "2_2") (pintype "passive"))
      (node (ref "R79") (pin "1") (pinfunction "1_1") (pintype "passive"))
      (node (ref "U9") (pin "9") (pinfunction "A8_9") (pintype "bidirectional"))
    )
    (net (code "267") (name "WL_SDIO_D0") (class "Default")
      (node (ref "R80") (pin "1") (pinfunction "1_1") (pintype "passive"))
      (node (ref "R98") (pin "2") (pinfunction "2_2") (pintype "passive"))
      (node (ref "U9") (pin "7") (pinfunction "A6_7") (pintype "bidirectional"))
    )
    (net (code "268") (name "WL_SDIO_D1") (class "Default")
      (node (ref "R81") (pin "1") (pinfunction "1_1") (pintype "passive"))
      (node (ref "R99") (pin "2") (pinfunction "2_2") (pintype "passive"))
      (node (ref "U9") (pin "6") (pinfunction "A5_6") (pintype "bidirectional"))
    )
    (net (code "269") (name "WL_SDIO_D2") (class "Default")
      (node (ref "R101") (pin "2") (pinfunction "2_2") (pintype "passive"))
      (node (ref "R82") (pin "1") (pinfunction "1_1") (pintype "passive"))
      (node (ref "U9") (pin "5") (pinfunction "A4_5") (pintype "bidirectional"))
    )
    (net (code "270") (name "WL_SDIO_D3") (class "Default")
      (node (ref "R102") (pin "2") (pinfunction "2_2") (pintype "passive"))
      (node (ref "R83") (pin "1") (pinfunction "1_1") (pintype "passive"))
      (node (ref "U9") (pin "4") (pinfunction "A3_4") (pintype "bidirectional"))
    )
    (net (code "271") (name "unconnected-(12V-PadOUT_CON)") (class "Default")
      (node (ref "12V") (pin "OUT_CON") (pinfunction "OUT_CON_OUT_CON") (pintype "bidirectional"))
    )
    (net (code "272") (name "unconnected-(CHGIC-ACOK-Pad12)") (class "Default")
      (node (ref "CHGIC") (pin "12") (pinfunction "ACOK_12") (pintype "bidirectional"))
    )
    (net (code "273") (name "unconnected-(CHGIC-CELL-Pad4)") (class "Default")
      (node (ref "CHGIC") (pin "4") (pinfunction "CELL_4") (pintype "bidirectional"))
    )
    (net (code "274") (name "unconnected-(CHGIC-SEL-Pad5)") (class "Default")
      (node (ref "CHGIC") (pin "5") (pinfunction "SEL_5") (pintype "bidirectional"))
    )
    (net (code "275") (name "unconnected-(FUD1-PadP$1)") (class "Default")
      (node (ref "FUD1") (pin "P$1") (pinfunction "P$1_P$1") (pintype "no_connect"))
    )
    (net (code "276") (name "unconnected-(FUD2-PadP$1)") (class "Default")
      (node (ref "FUD2") (pin "P$1") (pinfunction "P$1_P$1") (pintype "no_connect"))
    )
    (net (code "277") (name "unconnected-(FUD3-PadP$1)") (class "Default")
      (node (ref "FUD3") (pin "P$1") (pinfunction "P$1_P$1") (pintype "no_connect"))
    )
    (net (code "278") (name "unconnected-(FUD4-PadP$1)") (class "Default")
      (node (ref "FUD4") (pin "P$1") (pinfunction "P$1_P$1") (pintype "no_connect"))
    )
    (net (code "279") (name "unconnected-(FUD5-PadP$1)") (class "Default")
      (node (ref "FUD5") (pin "P$1") (pinfunction "P$1_P$1") (pintype "no_connect"))
    )
    (net (code "280") (name "unconnected-(FUD6-PadP$1)") (class "Default")
      (node (ref "FUD6") (pin "P$1") (pinfunction "P$1_P$1") (pintype "no_connect"))
    )
    (net (code "281") (name "unconnected-(GPS-Pad1)") (class "Default")
      (node (ref "GPS") (pin "1") (pinfunction "1_1") (pintype "bidirectional"))
    )
    (net (code "282") (name "unconnected-(IMU-AUX_CL-Pad7)") (class "Default")
      (node (ref "IMU") (pin "7") (pinfunction "AUX_CL_7") (pintype "bidirectional"))
    )
    (net (code "283") (name "unconnected-(IMU-AUX_DA-Pad21)") (class "Default")
      (node (ref "IMU") (pin "21") (pinfunction "AUX_DA_21") (pintype "bidirectional"))
    )
    (net (code "284") (name "unconnected-(IMU-FSYNC-Pad11)") (class "Default")
      (node (ref "IMU") (pin "11") (pinfunction "FSYNC_11") (pintype "bidirectional"))
    )
    (net (code "285") (name "unconnected-(IMU-NC-Pad2)") (class "Default")
      (node (ref "IMU") (pin "2") (pinfunction "NC_2") (pintype "bidirectional"))
    )
    (net (code "286") (name "unconnected-(IMU-NC-Pad3)") (class "Default")
      (node (ref "IMU") (pin "3") (pinfunction "NC_3") (pintype "bidirectional"))
    )
    (net (code "287") (name "unconnected-(IMU-NC-Pad4)") (class "Default")
      (node (ref "IMU") (pin "4") (pinfunction "NC_4") (pintype "bidirectional"))
    )
    (net (code "288") (name "unconnected-(IMU-NC-Pad5)") (class "Default")
      (node (ref "IMU") (pin "5") (pinfunction "NC_5") (pintype "bidirectional"))
    )
    (net (code "289") (name "unconnected-(IMU-NC-Pad6)") (class "Default")
      (node (ref "IMU") (pin "6") (pinfunction "NC_6") (pintype "bidirectional"))
    )
    (net (code "290") (name "unconnected-(IMU-NC-Pad14)") (class "Default")
      (node (ref "IMU") (pin "14") (pinfunction "NC_14") (pintype "bidirectional"))
    )
    (net (code "291") (name "unconnected-(IMU-NC-Pad15)") (class "Default")
      (node (ref "IMU") (pin "15") (pinfunction "NC_15") (pintype "bidirectional"))
    )
    (net (code "292") (name "unconnected-(IMU-NC-Pad16)") (class "Default")
      (node (ref "IMU") (pin "16") (pinfunction "NC_16") (pintype "bidirectional"))
    )
    (net (code "293") (name "unconnected-(IMU-NC-Pad17)") (class "Default")
      (node (ref "IMU") (pin "17") (pinfunction "NC_17") (pintype "bidirectional"))
    )
    (net (code "294") (name "unconnected-(IMU-RESV-Pad19)") (class "Default")
      (node (ref "IMU") (pin "19") (pinfunction "RESV_19") (pintype "bidirectional"))
    )
    (net (code "295") (name "unconnected-(PROT-CO-Pad3)") (class "Default")
      (node (ref "PROT") (pin "3") (pinfunction "CO_3") (pintype "bidirectional"))
    )
    (net (code "296") (name "unconnected-(PROT-DP-Pad4)") (class "Default")
      (node (ref "PROT") (pin "4") (pinfunction "DP_4") (pintype "bidirectional"))
    )
    (net (code "297") (name "unconnected-(SIPA-BAT_TEMP-PadW1)") (class "Default")
      (node (ref "SIP") (pin "W1") (pinfunction "BAT_TEMP_W1") (pintype "bidirectional"))
    )
    (net (code "298") (name "unconnected-(SIPA-BAT_VOLT-PadY1)") (class "Default")
      (node (ref "SIP") (pin "Y1") (pinfunction "BAT_VOLT_Y1") (pintype "bidirectional"))
    )
    (net (code "299") (name "unconnected-(SIPA-L1_IN-PadY14)") (class "Default")
      (node (ref "SIP") (pin "Y14") (pinfunction "L1_IN_Y14") (pintype "bidirectional"))
    )
    (net (code "300") (name "unconnected-(SIPA-L1_OUT-PadY13)") (class "Default")
      (node (ref "SIP") (pin "Y13") (pinfunction "L1_OUT_Y13") (pintype "bidirectional"))
    )
    (net (code "301") (name "unconnected-(SIPA-L2_IN-PadY17)") (class "Default")
      (node (ref "SIP") (pin "Y17") (pinfunction "L2_IN_Y17") (pintype "bidirectional"))
    )
    (net (code "302") (name "unconnected-(SIPA-L2_OUT-PadY16)") (class "Default")
      (node (ref "SIP") (pin "Y16") (pinfunction "L2_OUT_Y16") (pintype "bidirectional"))
    )
    (net (code "303") (name "unconnected-(SIPA-L3_IN-PadY20)") (class "Default")
      (node (ref "SIP") (pin "Y20") (pinfunction "L3_IN_Y20") (pintype "bidirectional"))
    )
    (net (code "304") (name "unconnected-(SIPA-L3_OUT-PadY19)") (class "Default")
      (node (ref "SIP") (pin "Y19") (pinfunction "L3_OUT_Y19") (pintype "bidirectional"))
    )
    (net (code "305") (name "unconnected-(SIPC-AIN4-PadC8)") (class "Default")
      (node (ref "SIP") (pin "C8") (pinfunction "AIN4_C8") (pintype "bidirectional"))
    )
    (net (code "306") (name "unconnected-(SIPC-USB0_CE-PadM15)") (class "Default")
      (node (ref "SIP") (pin "M15") (pinfunction "USB0_CE_M15") (pintype "bidirectional"))
    )
    (net (code "307") (name "unconnected-(SIPC-USB0_DRVVBUS-PadF16)") (class "Default")
      (node (ref "SIP") (pin "F16") (pinfunction "USB0_DRVVBUS_F16") (pintype "bidirectional"))
    )
    (net (code "308") (name "unconnected-(SIPC-USB1_CE-PadP18)") (class "Default")
      (node (ref "SIP") (pin "P18") (pinfunction "USB1_CE_P18") (pintype "bidirectional"))
    )
    (net (code "309") (name "unconnected-(SIPC-USB1_DRVVBUS-PadF15)") (class "Default")
      (node (ref "SIP") (pin "F15") (pinfunction "USB1_DRVVBUS_F15") (pintype "bidirectional"))
    )
    (net (code "310") (name "unconnected-(SIPD-NC1-PadV11)") (class "Default")
      (node (ref "SIP") (pin "V11") (pinfunction "NC1_V11") (pintype "bidirectional"))
    )
    (net (code "311") (name "unconnected-(SIPD-NC2-PadU11)") (class "Default")
      (node (ref "SIP") (pin "U11") (pinfunction "NC2_U11") (pintype "bidirectional"))
    )
    (net (code "312") (name "unconnected-(SIPD-NC3-PadV10)") (class "Default")
      (node (ref "SIP") (pin "V10") (pinfunction "NC3_V10") (pintype "bidirectional"))
    )
    (net (code "313") (name "unconnected-(SIPD-NC4-PadB1)") (class "Default")
      (node (ref "SIP") (pin "B1") (pinfunction "NC4_B1") (pintype "bidirectional"))
    )
    (net (code "314") (name "unconnected-(SIPD-NC5-PadB2)") (class "Default")
      (node (ref "SIP") (pin "B2") (pinfunction "NC5_B2") (pintype "bidirectional"))
    )
    (net (code "315") (name "unconnected-(SIPD-NC6-PadB3)") (class "Default")
      (node (ref "SIP") (pin "B3") (pinfunction "NC6_B3") (pintype "bidirectional"))
    )
    (net (code "316") (name "unconnected-(SIPD-NC12-PadC1)") (class "Default")
      (node (ref "SIP") (pin "C1") (pinfunction "NC12_C1") (pintype "bidirectional"))
    )
    (net (code "317") (name "unconnected-(SIPD-NC20-PadC2)") (class "Default")
      (node (ref "SIP") (pin "C2") (pinfunction "NC20_C2") (pintype "bidirectional"))
    )
    (net (code "318") (name "unconnected-(SIPD-NC21-PadC3)") (class "Default")
      (node (ref "SIP") (pin "C3") (pinfunction "NC21_C3") (pintype "bidirectional"))
    )
    (net (code "319") (name "unconnected-(SIPD-NC22-PadC4)") (class "Default")
      (node (ref "SIP") (pin "C4") (pinfunction "NC22_C4") (pintype "bidirectional"))
    )
    (net (code "320") (name "unconnected-(SIPD-NC23-PadP2)") (class "Default")
      (node (ref "SIP") (pin "P2") (pinfunction "NC23_P2") (pintype "bidirectional"))
    )
    (net (code "321") (name "unconnected-(SIPD-NC24-PadD1)") (class "Default")
      (node (ref "SIP") (pin "D1") (pinfunction "NC24_D1") (pintype "bidirectional"))
    )
    (net (code "322") (name "unconnected-(SIPD-NC31-PadD2)") (class "Default")
      (node (ref "SIP") (pin "D2") (pinfunction "NC31_D2") (pintype "bidirectional"))
    )
    (net (code "323") (name "unconnected-(SIPD-NC32-PadD3)") (class "Default")
      (node (ref "SIP") (pin "D3") (pinfunction "NC32_D3") (pintype "bidirectional"))
    )
    (net (code "324") (name "unconnected-(SIPD-NC33-PadD4)") (class "Default")
      (node (ref "SIP") (pin "D4") (pinfunction "NC33_D4") (pintype "bidirectional"))
    )
    (net (code "325") (name "unconnected-(SIPD-NC34-PadD5)") (class "Default")
      (node (ref "SIP") (pin "D5") (pinfunction "NC34_D5") (pintype "bidirectional"))
    )
    (net (code "326") (name "unconnected-(SIPD-NC45-PadP3)") (class "Default")
      (node (ref "SIP") (pin "P3") (pinfunction "NC45_P3") (pintype "bidirectional"))
    )
    (net (code "327") (name "unconnected-(SIPD-NC46-PadE1)") (class "Default")
      (node (ref "SIP") (pin "E1") (pinfunction "NC46_E1") (pintype "bidirectional"))
    )
    (net (code "328") (name "unconnected-(SIPD-NC47-PadE2)") (class "Default")
      (node (ref "SIP") (pin "E2") (pinfunction "NC47_E2") (pintype "bidirectional"))
    )
    (net (code "329") (name "unconnected-(SIPD-NC48-PadE3)") (class "Default")
      (node (ref "SIP") (pin "E3") (pinfunction "NC48_E3") (pintype "bidirectional"))
    )
    (net (code "330") (name "unconnected-(SIPD-NC58-PadE4)") (class "Default")
      (node (ref "SIP") (pin "E4") (pinfunction "NC58_E4") (pintype "bidirectional"))
    )
    (net (code "331") (name "unconnected-(SIPD-NC59-PadF1)") (class "Default")
      (node (ref "SIP") (pin "F1") (pinfunction "NC59_F1") (pintype "bidirectional"))
    )
    (net (code "332") (name "unconnected-(SIPD-NC60-PadF2)") (class "Default")
      (node (ref "SIP") (pin "F2") (pinfunction "NC60_F2") (pintype "bidirectional"))
    )
    (net (code "333") (name "unconnected-(SIPD-NC61-PadF3)") (class "Default")
      (node (ref "SIP") (pin "F3") (pinfunction "NC61_F3") (pintype "bidirectional"))
    )
    (net (code "334") (name "unconnected-(SIPD-NC68-PadF4)") (class "Default")
      (node (ref "SIP") (pin "F4") (pinfunction "NC68_F4") (pintype "bidirectional"))
    )
    (net (code "335") (name "unconnected-(SIPD-NC69-PadG1)") (class "Default")
      (node (ref "SIP") (pin "G1") (pinfunction "NC69_G1") (pintype "bidirectional"))
    )
    (net (code "336") (name "unconnected-(SIPD-NC70-PadG2)") (class "Default")
      (node (ref "SIP") (pin "G2") (pinfunction "NC70_G2") (pintype "bidirectional"))
    )
    (net (code "337") (name "unconnected-(SIPD-NC71-PadG3)") (class "Default")
      (node (ref "SIP") (pin "G3") (pinfunction "NC71_G3") (pintype "bidirectional"))
    )
    (net (code "338") (name "unconnected-(SIPD-NC76-PadG4)") (class "Default")
      (node (ref "SIP") (pin "G4") (pinfunction "NC76_G4") (pintype "bidirectional"))
    )
    (net (code "339") (name "unconnected-(SIPD-NC77-PadH1)") (class "Default")
      (node (ref "SIP") (pin "H1") (pinfunction "NC77_H1") (pintype "bidirectional"))
    )
    (net (code "340") (name "unconnected-(SIPD-NC78-PadH2)") (class "Default")
      (node (ref "SIP") (pin "H2") (pinfunction "NC78_H2") (pintype "bidirectional"))
    )
    (net (code "341") (name "unconnected-(SIPD-NC79-PadH3)") (class "Default")
      (node (ref "SIP") (pin "H3") (pinfunction "NC79_H3") (pintype "bidirectional"))
    )
    (net (code "342") (name "unconnected-(SIPD-NC84-PadH4)") (class "Default")
      (node (ref "SIP") (pin "H4") (pinfunction "NC84_H4") (pintype "bidirectional"))
    )
    (net (code "343") (name "unconnected-(SIPD-NC85-PadJ1)") (class "Default")
      (node (ref "SIP") (pin "J1") (pinfunction "NC85_J1") (pintype "bidirectional"))
    )
    (net (code "344") (name "unconnected-(SIPD-NC86-PadJ2)") (class "Default")
      (node (ref "SIP") (pin "J2") (pinfunction "NC86_J2") (pintype "bidirectional"))
    )
    (net (code "345") (name "unconnected-(SIPD-NC87-PadJ3)") (class "Default")
      (node (ref "SIP") (pin "J3") (pinfunction "NC87_J3") (pintype "bidirectional"))
    )
    (net (code "346") (name "unconnected-(SIPD-NC94-PadJ4)") (class "Default")
      (node (ref "SIP") (pin "J4") (pinfunction "NC94_J4") (pintype "bidirectional"))
    )
    (net (code "347") (name "unconnected-(SIPD-NC95-PadK1)") (class "Default")
      (node (ref "SIP") (pin "K1") (pinfunction "NC95_K1") (pintype "bidirectional"))
    )
    (net (code "348") (name "unconnected-(SIPD-NC96-PadK2)") (class "Default")
      (node (ref "SIP") (pin "K2") (pinfunction "NC96_K2") (pintype "bidirectional"))
    )
    (net (code "349") (name "unconnected-(SIPD-NC97-PadK3)") (class "Default")
      (node (ref "SIP") (pin "K3") (pinfunction "NC97_K3") (pintype "bidirectional"))
    )
    (net (code "350") (name "unconnected-(SIPD-NC104-PadK4)") (class "Default")
      (node (ref "SIP") (pin "K4") (pinfunction "NC104_K4") (pintype "bidirectional"))
    )
    (net (code "351") (name "unconnected-(SIPD-NC105-PadL1)") (class "Default")
      (node (ref "SIP") (pin "L1") (pinfunction "NC105_L1") (pintype "bidirectional"))
    )
    (net (code "352") (name "unconnected-(SIPD-NC106-PadL2)") (class "Default")
      (node (ref "SIP") (pin "L2") (pinfunction "NC106_L2") (pintype "bidirectional"))
    )
    (net (code "353") (name "unconnected-(SIPD-NC107-PadL3)") (class "Default")
      (node (ref "SIP") (pin "L3") (pinfunction "NC107_L3") (pintype "bidirectional"))
    )
    (net (code "354") (name "unconnected-(SIPD-NC111-PadL4)") (class "Default")
      (node (ref "SIP") (pin "L4") (pinfunction "NC111_L4") (pintype "bidirectional"))
    )
    (net (code "355") (name "unconnected-(SIPD-NC112-PadM1)") (class "Default")
      (node (ref "SIP") (pin "M1") (pinfunction "NC112_M1") (pintype "bidirectional"))
    )
    (net (code "356") (name "unconnected-(SIPD-NC113-PadM2)") (class "Default")
      (node (ref "SIP") (pin "M2") (pinfunction "NC113_M2") (pintype "bidirectional"))
    )
    (net (code "357") (name "unconnected-(SIPD-NC114-PadM3)") (class "Default")
      (node (ref "SIP") (pin "M3") (pinfunction "NC114_M3") (pintype "bidirectional"))
    )
    (net (code "358") (name "unconnected-(SIPD-NC121-PadM4)") (class "Default")
      (node (ref "SIP") (pin "M4") (pinfunction "NC121_M4") (pintype "bidirectional"))
    )
    (net (code "359") (name "unconnected-(SIPD-NC122-PadP4)") (class "Default")
      (node (ref "SIP") (pin "P4") (pinfunction "NC122_P4") (pintype "bidirectional"))
    )
    (net (code "360") (name "unconnected-(SIPD-NC123-PadN1)") (class "Default")
      (node (ref "SIP") (pin "N1") (pinfunction "NC123_N1") (pintype "bidirectional"))
    )
    (net (code "361") (name "unconnected-(SIPD-NC124-PadN2)") (class "Default")
      (node (ref "SIP") (pin "N2") (pinfunction "NC124_N2") (pintype "bidirectional"))
    )
    (net (code "362") (name "unconnected-(SIPD-NC136-PadN3)") (class "Default")
      (node (ref "SIP") (pin "N3") (pinfunction "NC136_N3") (pintype "bidirectional"))
    )
    (net (code "363") (name "unconnected-(SIPD-NC137-PadN4)") (class "Default")
      (node (ref "SIP") (pin "N4") (pinfunction "NC137_N4") (pintype "bidirectional"))
    )
    (net (code "364") (name "unconnected-(SIPD-NC138-PadP1)") (class "Default")
      (node (ref "SIP") (pin "P1") (pinfunction "NC138_P1") (pintype "bidirectional"))
    )
    (net (code "365") (name "unconnected-(SIPE-CAP_VBB_MPU-PadC10)") (class "Default")
      (node (ref "SIP") (pin "C10") (pinfunction "CAP_VBB_MPU_C10") (pintype "bidirectional"))
    )
    (net (code "366") (name "unconnected-(SIPE-CAP_VDD_RTC-PadD6)") (class "Default")
      (node (ref "SIP") (pin "D6") (pinfunction "CAP_VDD_RTC_D6") (pintype "bidirectional"))
    )
    (net (code "367") (name "unconnected-(SIPE-CAP_VDD_SRAM_COR-PadD9)") (class "Default")
      (node (ref "SIP") (pin "D9") (pinfunction "CAP_VDD_SRAM_COR_D9") (pintype "bidirectional"))
    )
    (net (code "368") (name "unconnected-(SIPE-CAP_VDD_SRAM_MPU-PadD11)") (class "Default")
      (node (ref "SIP") (pin "D11") (pinfunction "CAP_VDD_SRAM_MPU_D11") (pintype "bidirectional"))
    )
    (net (code "369") (name "unconnected-(SIPE-TESTOUT-PadA3)") (class "Default")
      (node (ref "SIP") (pin "A3") (pinfunction "TESTOUT_A3") (pintype "bidirectional"))
    )
    (net (code "370") (name "unconnected-(SIPE-VDDS_DDR1-PadE5)") (class "Default")
      (node (ref "SIP") (pin "E5") (pinfunction "VDDS_DDR1_E5") (pintype "bidirectional"))
    )
    (net (code "371") (name "unconnected-(SIPE-VDDS_DDR2-PadF5)") (class "Default")
      (node (ref "SIP") (pin "F5") (pinfunction "VDDS_DDR2_F5") (pintype "bidirectional"))
    )
    (net (code "372") (name "unconnected-(SIPE-VDDS_DDR3-PadG5)") (class "Default")
      (node (ref "SIP") (pin "G5") (pinfunction "VDDS_DDR3_G5") (pintype "bidirectional"))
    )
    (net (code "373") (name "unconnected-(SIPE-VDDS_DDR4-PadH5)") (class "Default")
      (node (ref "SIP") (pin "H5") (pinfunction "VDDS_DDR4_H5") (pintype "bidirectional"))
    )
    (net (code "374") (name "unconnected-(SIPE-VDDS_DDR5-PadJ5)") (class "Default")
      (node (ref "SIP") (pin "J5") (pinfunction "VDDS_DDR5_J5") (pintype "bidirectional"))
    )
    (net (code "375") (name "unconnected-(SIPE-VDDS_DDR6-PadK5)") (class "Default")
      (node (ref "SIP") (pin "K5") (pinfunction "VDDS_DDR6_K5") (pintype "bidirectional"))
    )
    (net (code "376") (name "unconnected-(SIPE-VDDS_DDR7-PadL5)") (class "Default")
      (node (ref "SIP") (pin "L5") (pinfunction "VDDS_DDR7_L5") (pintype "bidirectional"))
    )
    (net (code "377") (name "unconnected-(SIPE-VDD_3V3A1-PadE10)") (class "Default")
      (node (ref "SIP") (pin "E10") (pinfunction "VDD_3V3A1_E10") (pintype "bidirectional"))
    )
    (net (code "378") (name "unconnected-(SIPE-VDD_3V3A2-PadE11)") (class "Default")
      (node (ref "SIP") (pin "E11") (pinfunction "VDD_3V3A2_E11") (pintype "bidirectional"))
    )
    (net (code "379") (name "unconnected-(SIPE-VDD_3V3A3-PadE12)") (class "Default")
      (node (ref "SIP") (pin "E12") (pinfunction "VDD_3V3A3_E12") (pintype "bidirectional"))
    )
    (net (code "380") (name "unconnected-(SIPE-VDD_3V3A4-PadE13)") (class "Default")
      (node (ref "SIP") (pin "E13") (pinfunction "VDD_3V3A4_E13") (pintype "bidirectional"))
    )
    (net (code "381") (name "unconnected-(SIPE-VDD_3V3A5-PadF14)") (class "Default")
      (node (ref "SIP") (pin "F14") (pinfunction "VDD_3V3A5_F14") (pintype "bidirectional"))
    )
    (net (code "382") (name "unconnected-(SIPE-VDD_3V3A6-PadG14)") (class "Default")
      (node (ref "SIP") (pin "G14") (pinfunction "VDD_3V3A6_G14") (pintype "bidirectional"))
    )
    (net (code "383") (name "unconnected-(SIPE-VDD_3V3A7-PadH14)") (class "Default")
      (node (ref "SIP") (pin "H14") (pinfunction "VDD_3V3A7_H14") (pintype "bidirectional"))
    )
    (net (code "384") (name "unconnected-(SIPE-VDD_3V3A8-PadJ14)") (class "Default")
      (node (ref "SIP") (pin "J14") (pinfunction "VDD_3V3A8_J14") (pintype "bidirectional"))
    )
    (net (code "385") (name "unconnected-(SIPE-VDD_3V3A9-PadK14)") (class "Default")
      (node (ref "SIP") (pin "K14") (pinfunction "VDD_3V3A9_K14") (pintype "bidirectional"))
    )
    (net (code "386") (name "unconnected-(SIPE-VDD_3V3A10-PadL14)") (class "Default")
      (node (ref "SIP") (pin "L14") (pinfunction "VDD_3V3A10_L14") (pintype "bidirectional"))
    )
    (net (code "387") (name "unconnected-(SIPE-VDD_3V3A11-PadN5)") (class "Default")
      (node (ref "SIP") (pin "N5") (pinfunction "VDD_3V3A11_N5") (pintype "bidirectional"))
    )
    (net (code "388") (name "unconnected-(SIPE-VDD_3V3A12-PadN15)") (class "Default")
      (node (ref "SIP") (pin "N15") (pinfunction "VDD_3V3A12_N15") (pintype "bidirectional"))
    )
    (net (code "389") (name "unconnected-(SIPE-VDD_3V3A13-PadP5)") (class "Default")
      (node (ref "SIP") (pin "P5") (pinfunction "VDD_3V3A13_P5") (pintype "bidirectional"))
    )
    (net (code "390") (name "unconnected-(SIPE-VDD_3V3A14-PadP6)") (class "Default")
      (node (ref "SIP") (pin "P6") (pinfunction "VDD_3V3A14_P6") (pintype "bidirectional"))
    )
    (net (code "391") (name "unconnected-(SIPE-VDD_3V3A15-PadP7)") (class "Default")
      (node (ref "SIP") (pin "P7") (pinfunction "VDD_3V3A15_P7") (pintype "bidirectional"))
    )
    (net (code "392") (name "unconnected-(SIPE-VDD_3V3A16-PadP8)") (class "Default")
      (node (ref "SIP") (pin "P8") (pinfunction "VDD_3V3A16_P8") (pintype "bidirectional"))
    )
    (net (code "393") (name "unconnected-(SIPE-VDD_3V3A17-PadP10)") (class "Default")
      (node (ref "SIP") (pin "P10") (pinfunction "VDD_3V3A17_P10") (pintype "bidirectional"))
    )
    (net (code "394") (name "unconnected-(SIPE-VDD_3V3A18-PadP11)") (class "Default")
      (node (ref "SIP") (pin "P11") (pinfunction "VDD_3V3A18_P11") (pintype "bidirectional"))
    )
    (net (code "395") (name "unconnected-(SIPE-VDD_3V3A19-PadP12)") (class "Default")
      (node (ref "SIP") (pin "P12") (pinfunction "VDD_3V3A19_P12") (pintype "bidirectional"))
    )
    (net (code "396") (name "unconnected-(SIPE-VDD_3V3A20-PadP13)") (class "Default")
      (node (ref "SIP") (pin "P13") (pinfunction "VDD_3V3A20_P13") (pintype "bidirectional"))
    )
    (net (code "397") (name "unconnected-(SIPE-VDD_3V3A21-PadR15)") (class "Default")
      (node (ref "SIP") (pin "R15") (pinfunction "VDD_3V3A21_R15") (pintype "bidirectional"))
    )
    (net (code "398") (name "unconnected-(SIPE-VDD_CORE1-PadF6)") (class "Default")
      (node (ref "SIP") (pin "F6") (pinfunction "VDD_CORE1_F6") (pintype "bidirectional"))
    )
    (net (code "399") (name "unconnected-(SIPE-VDD_CORE2-PadF7)") (class "Default")
      (node (ref "SIP") (pin "F7") (pinfunction "VDD_CORE2_F7") (pintype "bidirectional"))
    )
    (net (code "400") (name "unconnected-(SIPE-VDD_CORE3-PadG6)") (class "Default")
      (node (ref "SIP") (pin "G6") (pinfunction "VDD_CORE3_G6") (pintype "bidirectional"))
    )
    (net (code "401") (name "unconnected-(SIPE-VDD_CORE4-PadG7)") (class "Default")
      (node (ref "SIP") (pin "G7") (pinfunction "VDD_CORE4_G7") (pintype "bidirectional"))
    )
    (net (code "402") (name "unconnected-(SIPE-VDD_CORE5-PadG10)") (class "Default")
      (node (ref "SIP") (pin "G10") (pinfunction "VDD_CORE5_G10") (pintype "bidirectional"))
    )
    (net (code "403") (name "unconnected-(SIPE-VDD_CORE6-PadH11)") (class "Default")
      (node (ref "SIP") (pin "H11") (pinfunction "VDD_CORE6_H11") (pintype "bidirectional"))
    )
    (net (code "404") (name "unconnected-(SIPE-VDD_CORE7-PadJ12)") (class "Default")
      (node (ref "SIP") (pin "J12") (pinfunction "VDD_CORE7_J12") (pintype "bidirectional"))
    )
    (net (code "405") (name "unconnected-(SIPE-VDD_CORE8-PadK6)") (class "Default")
      (node (ref "SIP") (pin "K6") (pinfunction "VDD_CORE8_K6") (pintype "bidirectional"))
    )
    (net (code "406") (name "unconnected-(SIPE-VDD_CORE9-PadK8)") (class "Default")
      (node (ref "SIP") (pin "K8") (pinfunction "VDD_CORE9_K8") (pintype "bidirectional"))
    )
    (net (code "407") (name "unconnected-(SIPE-VDD_CORE10-PadK12)") (class "Default")
      (node (ref "SIP") (pin "K12") (pinfunction "VDD_CORE10_K12") (pintype "bidirectional"))
    )
    (net (code "408") (name "unconnected-(SIPE-VDD_CORE11-PadL6)") (class "Default")
      (node (ref "SIP") (pin "L6") (pinfunction "VDD_CORE11_L6") (pintype "bidirectional"))
    )
    (net (code "409") (name "unconnected-(SIPE-VDD_CORE12-PadL7)") (class "Default")
      (node (ref "SIP") (pin "L7") (pinfunction "VDD_CORE12_L7") (pintype "bidirectional"))
    )
    (net (code "410") (name "unconnected-(SIPE-VDD_CORE13-PadL8)") (class "Default")
      (node (ref "SIP") (pin "L8") (pinfunction "VDD_CORE13_L8") (pintype "bidirectional"))
    )
    (net (code "411") (name "unconnected-(SIPE-VDD_CORE14-PadL9)") (class "Default")
      (node (ref "SIP") (pin "L9") (pinfunction "VDD_CORE14_L9") (pintype "bidirectional"))
    )
    (net (code "412") (name "unconnected-(SIPE-VDD_CORE15-PadM11)") (class "Default")
      (node (ref "SIP") (pin "M11") (pinfunction "VDD_CORE15_M11") (pintype "bidirectional"))
    )
    (net (code "413") (name "unconnected-(SIPE-VDD_CORE16-PadM13)") (class "Default")
      (node (ref "SIP") (pin "M13") (pinfunction "VDD_CORE16_M13") (pintype "bidirectional"))
    )
    (net (code "414") (name "unconnected-(SIPE-VDD_CORE17-PadN8)") (class "Default")
      (node (ref "SIP") (pin "N8") (pinfunction "VDD_CORE17_N8") (pintype "bidirectional"))
    )
    (net (code "415") (name "unconnected-(SIPE-VDD_CORE18-PadN9)") (class "Default")
      (node (ref "SIP") (pin "N9") (pinfunction "VDD_CORE18_N9") (pintype "bidirectional"))
    )
    (net (code "416") (name "unconnected-(SIPE-VDD_CORE19-PadN12)") (class "Default")
      (node (ref "SIP") (pin "N12") (pinfunction "VDD_CORE19_N12") (pintype "bidirectional"))
    )
    (net (code "417") (name "unconnected-(SIPE-VDD_CORE20-PadN13)") (class "Default")
      (node (ref "SIP") (pin "N13") (pinfunction "VDD_CORE20_N13") (pintype "bidirectional"))
    )
    (net (code "418") (name "unconnected-(SIPE-VDD_MPU0-PadF10)") (class "Default")
      (node (ref "SIP") (pin "F10") (pinfunction "VDD_MPU0_F10") (pintype "bidirectional"))
    )
    (net (code "419") (name "unconnected-(SIPE-VDD_MPU1-PadF11)") (class "Default")
      (node (ref "SIP") (pin "F11") (pinfunction "VDD_MPU1_F11") (pintype "bidirectional"))
    )
    (net (code "420") (name "unconnected-(SIPE-VDD_MPU2-PadF12)") (class "Default")
      (node (ref "SIP") (pin "F12") (pinfunction "VDD_MPU2_F12") (pintype "bidirectional"))
    )
    (net (code "421") (name "unconnected-(SIPE-VDD_MPU3-PadF13)") (class "Default")
      (node (ref "SIP") (pin "F13") (pinfunction "VDD_MPU3_F13") (pintype "bidirectional"))
    )
    (net (code "422") (name "unconnected-(SIPE-VDD_MPU4-PadG13)") (class "Default")
      (node (ref "SIP") (pin "G13") (pinfunction "VDD_MPU4_G13") (pintype "bidirectional"))
    )
    (net (code "423") (name "unconnected-(SIPE-VDD_MPU5-PadH13)") (class "Default")
      (node (ref "SIP") (pin "H13") (pinfunction "VDD_MPU5_H13") (pintype "bidirectional"))
    )
    (net (code "424") (name "unconnected-(SIPE-VDD_MPU6-PadJ13)") (class "Default")
      (node (ref "SIP") (pin "J13") (pinfunction "VDD_MPU6_J13") (pintype "bidirectional"))
    )
    (net (code "425") (name "unconnected-(SIPE-VDD_MPU_MON-PadA2)") (class "Default")
      (node (ref "SIP") (pin "A2") (pinfunction "VDD_MPU_MON_A2") (pintype "bidirectional"))
    )
    (net (code "426") (name "unconnected-(SIPE-VDD_PLL1-PadE7)") (class "Default")
      (node (ref "SIP") (pin "E7") (pinfunction "VDD_PLL1_E7") (pintype "bidirectional"))
    )
    (net (code "427") (name "unconnected-(SIPE-VDD_PLL2-PadH15)") (class "Default")
      (node (ref "SIP") (pin "H15") (pinfunction "VDD_PLL2_H15") (pintype "bidirectional"))
    )
    (net (code "428") (name "unconnected-(SIPE-VDD_PLL3-PadR10)") (class "Default")
      (node (ref "SIP") (pin "R10") (pinfunction "VDD_PLL3_R10") (pintype "bidirectional"))
    )
    (net (code "429") (name "unconnected-(SIPE-VDD_PLL4-PadR11)") (class "Default")
      (node (ref "SIP") (pin "R11") (pinfunction "VDD_PLL4_R11") (pintype "bidirectional"))
    )
    (net (code "430") (name "unconnected-(SIPE-VDD_RTC1-PadD7)") (class "Default")
      (node (ref "SIP") (pin "D7") (pinfunction "VDD_RTC1_D7") (pintype "bidirectional"))
    )
    (net (code "431") (name "unconnected-(SIPE-VDD_RTC2-PadE6)") (class "Default")
      (node (ref "SIP") (pin "E6") (pinfunction "VDD_RTC2_E6") (pintype "bidirectional"))
    )
    (net (code "432") (name "unconnected-(SIPE-VDD_RTC4-PadF9)") (class "Default")
      (node (ref "SIP") (pin "F9") (pinfunction "VDD_RTC4_F9") (pintype "bidirectional"))
    )
    (net (code "433") (name "unconnected-(SIPE-VDD_RTC5-PadK13)") (class "Default")
      (node (ref "SIP") (pin "K13") (pinfunction "VDD_RTC5_K13") (pintype "bidirectional"))
    )
    (net (code "434") (name "unconnected-(SIPE-VDD_RTC6-PadN6)") (class "Default")
      (node (ref "SIP") (pin "N6") (pinfunction "VDD_RTC6_N6") (pintype "bidirectional"))
    )
    (net (code "435") (name "unconnected-(SIPE-VDD_RTC7-PadP9)") (class "Default")
      (node (ref "SIP") (pin "P9") (pinfunction "VDD_RTC7_P9") (pintype "bidirectional"))
    )
    (net (code "436") (name "unconnected-(SIPE-VDD_RTC8-PadP14)") (class "Default")
      (node (ref "SIP") (pin "P14") (pinfunction "VDD_RTC8_P14") (pintype "bidirectional"))
    )
    (net (code "437") (name "unconnected-(SIPE-VPP-PadM5)") (class "Default")
      (node (ref "SIP") (pin "M5") (pinfunction "VPP_M5") (pintype "bidirectional"))
    )
    (net (code "438") (name "unconnected-(U3-NC-Pad5)") (class "Default")
      (node (ref "U3") (pin "5") (pinfunction "NC_5") (pintype "bidirectional"))
    )
    (net (code "439") (name "unconnected-(U4-ID-Pad3)") (class "Default")
      (node (ref "U4") (pin "3") (pinfunction "ID_3") (pintype "bidirectional"))
    )
    (net (code "440") (name "unconnected-(U4-NC-Pad5)") (class "Default")
      (node (ref "U4") (pin "5") (pinfunction "NC_5") (pintype "bidirectional"))
    )
    (net (code "441") (name "unconnected-(U6-NC-Pad1)") (class "Default")
      (node (ref "U6") (pin "1") (pinfunction "NC_1") (pintype "passive"))
    )
    (net (code "442") (name "unconnected-(U7-BT_UART_DBG-Pad43)") (class "Default")
      (node (ref "U7") (pin "43") (pinfunction "BT_UART_DBG_43") (pintype "bidirectional"))
    )
    (net (code "443") (name "unconnected-(U7-GPIO1-Pad27)") (class "Default")
      (node (ref "U7") (pin "27") (pinfunction "GPIO1_27") (pintype "bidirectional"))
    )
    (net (code "444") (name "unconnected-(U7-GPIO2-Pad26)") (class "Default")
      (node (ref "U7") (pin "26") (pinfunction "GPIO2_26") (pintype "bidirectional"))
    )
    (net (code "445") (name "unconnected-(U7-GPIO4-Pad25)") (class "Default")
      (node (ref "U7") (pin "25") (pinfunction "GPIO4_25") (pintype "bidirectional"))
    )
    (net (code "446") (name "unconnected-(U7-GPIO9-Pad3)") (class "Default")
      (node (ref "U7") (pin "3") (pinfunction "GPIO9_3") (pintype "bidirectional"))
    )
    (net (code "447") (name "unconnected-(U7-GPIO10-Pad4)") (class "Default")
      (node (ref "U7") (pin "4") (pinfunction "GPIO10_4") (pintype "bidirectional"))
    )
    (net (code "448") (name "unconnected-(U7-GPIO11-Pad2)") (class "Default")
      (node (ref "U7") (pin "2") (pinfunction "GPIO11_2") (pintype "bidirectional"))
    )
    (net (code "449") (name "unconnected-(U7-GPIO12-Pad5)") (class "Default")
      (node (ref "U7") (pin "5") (pinfunction "GPIO12_5") (pintype "bidirectional"))
    )
    (net (code "450") (name "unconnected-(U7-RESERVED1-Pad21)") (class "Default")
      (node (ref "U7") (pin "21") (pinfunction "RESERVED1_21") (pintype "bidirectional"))
    )
    (net (code "451") (name "unconnected-(U7-RESERVED2-Pad22)") (class "Default")
      (node (ref "U7") (pin "22") (pinfunction "RESERVED2_22") (pintype "bidirectional"))
    )
    (net (code "452") (name "unconnected-(U7-RESERVED3-Pad62)") (class "Default")
      (node (ref "U7") (pin "62") (pinfunction "RESERVED3_62") (pintype "bidirectional"))
    )
    (net (code "453") (name "unconnected-(U7-WL_UART_DBG-Pad42)") (class "Default")
      (node (ref "U7") (pin "42") (pinfunction "WL_UART_DBG_42") (pintype "bidirectional"))
    )
  )
)
